# DL0WH_BiTuner_Ctrl_1V0.net
KiCad netlist of a schematic drawn in EAGLE
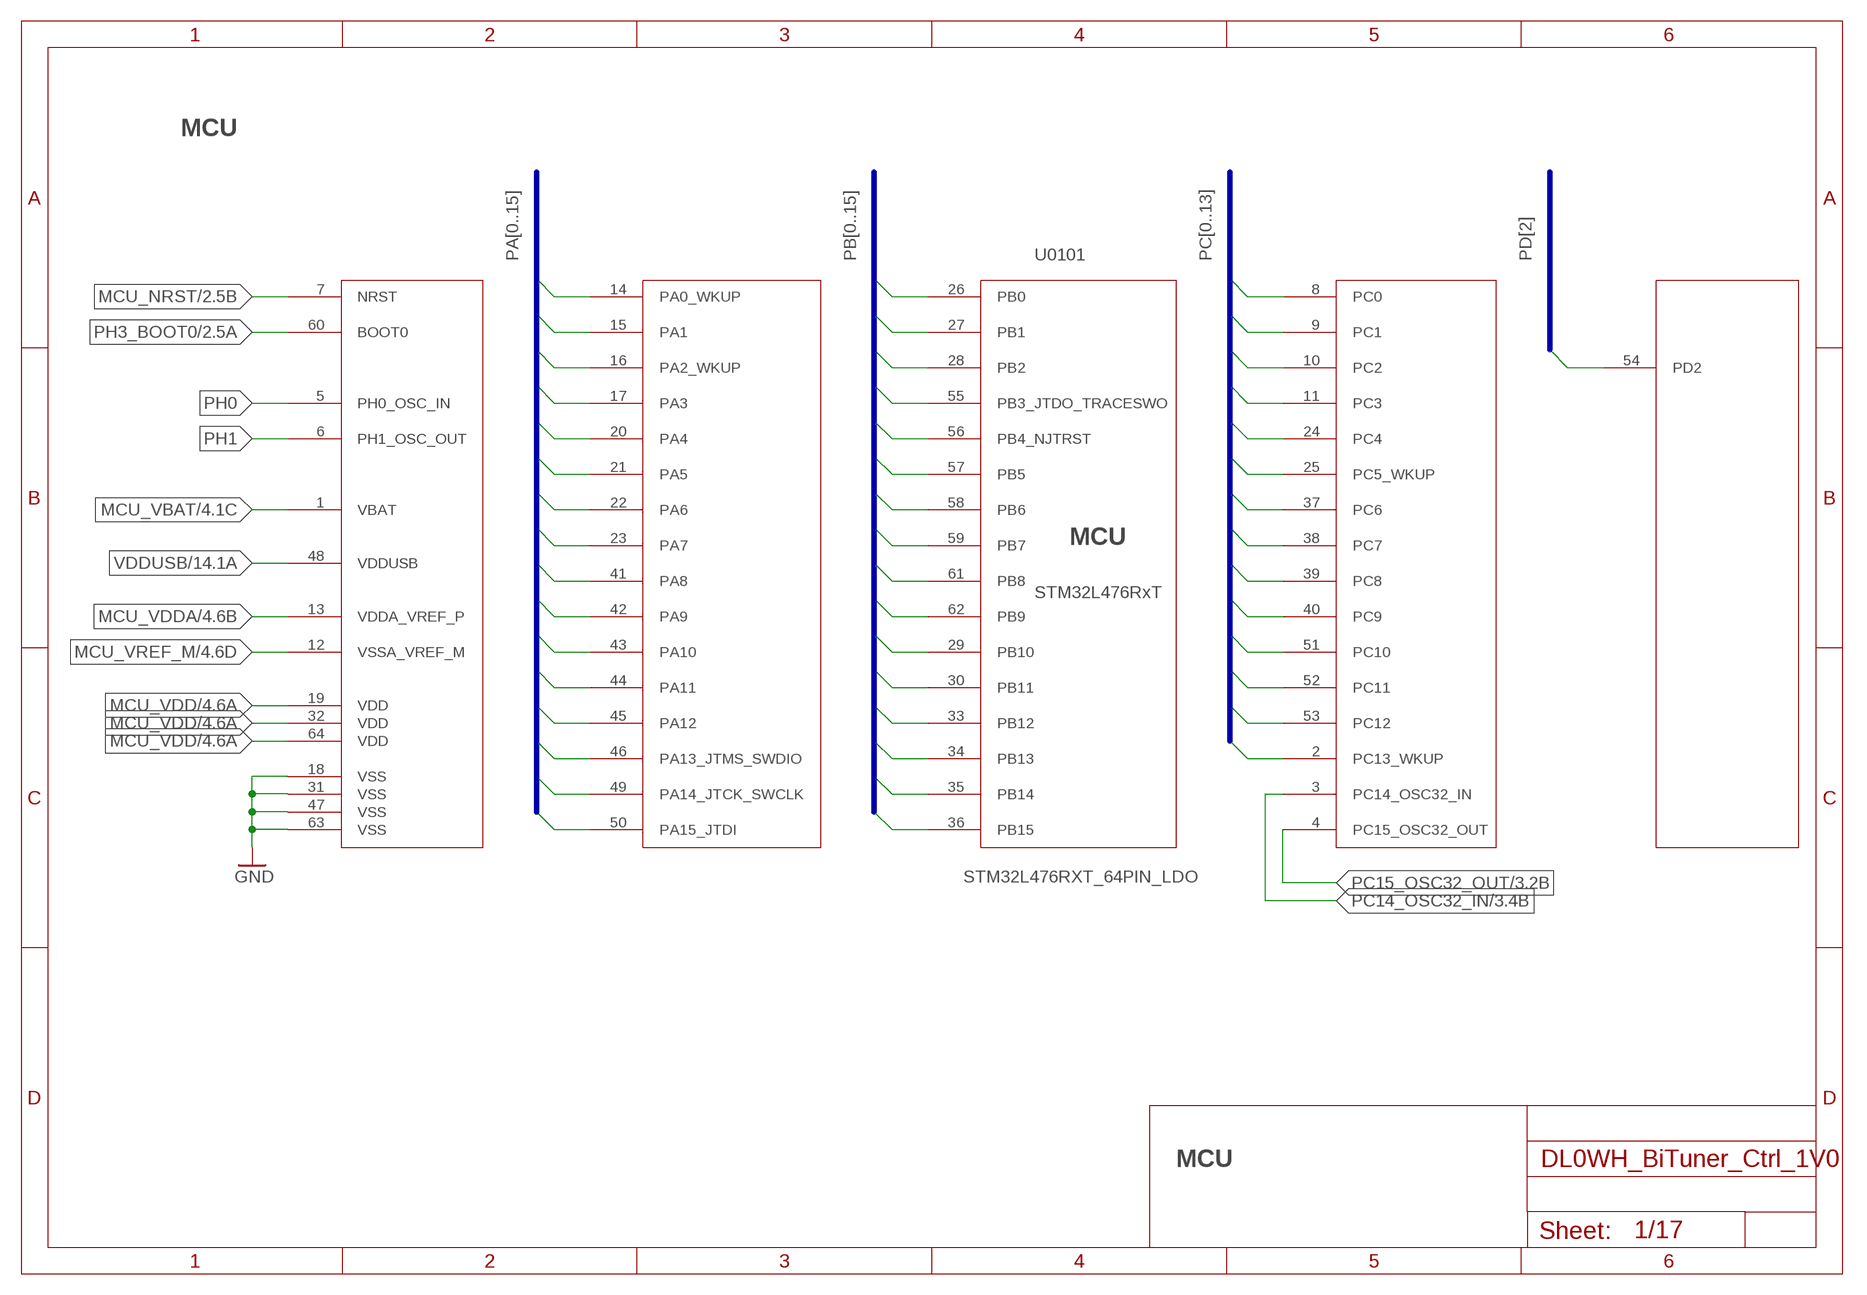
[diagram p0: schematic, sheet 1]
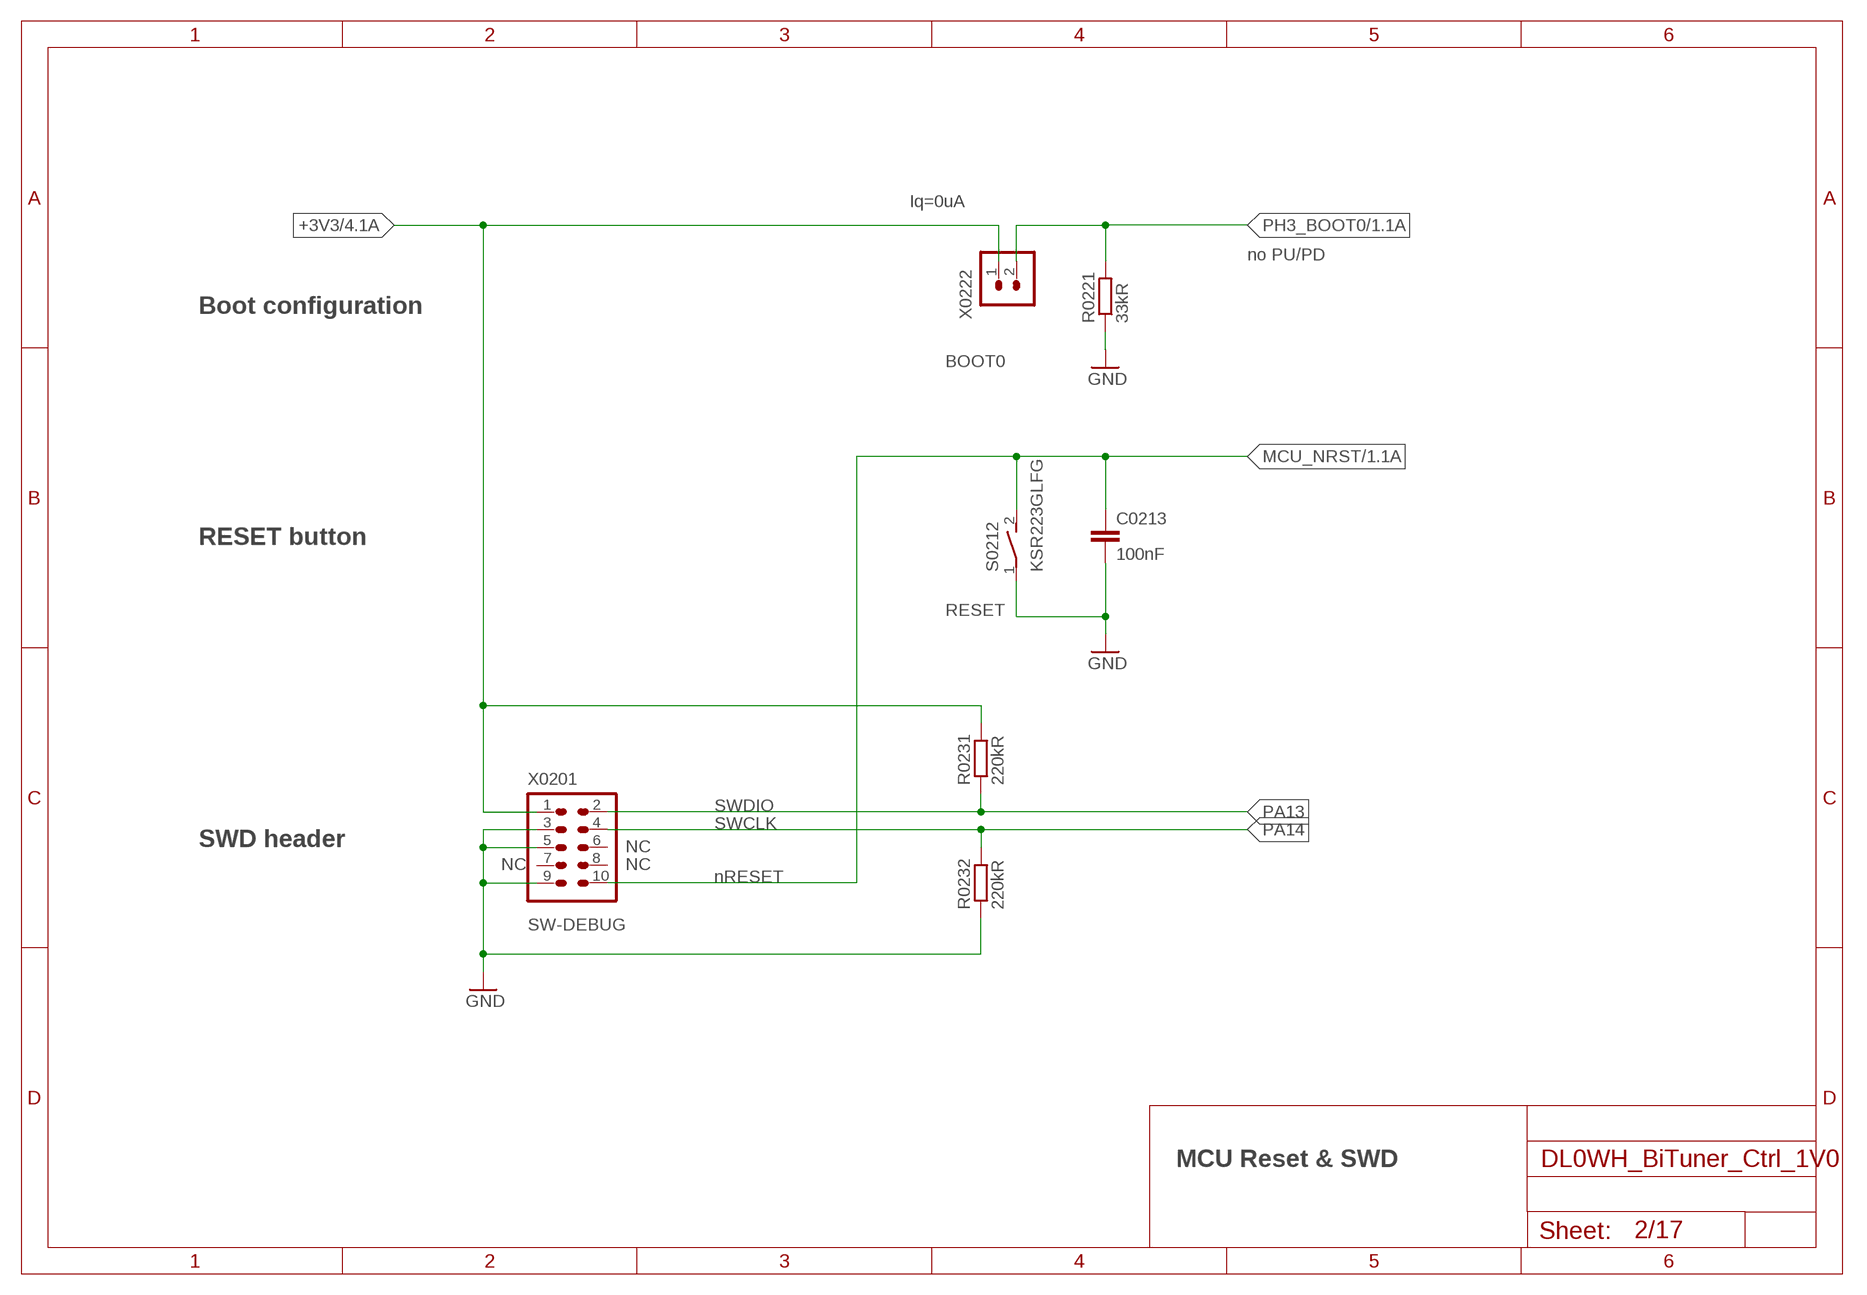
[diagram p1: schematic, sheet 2]
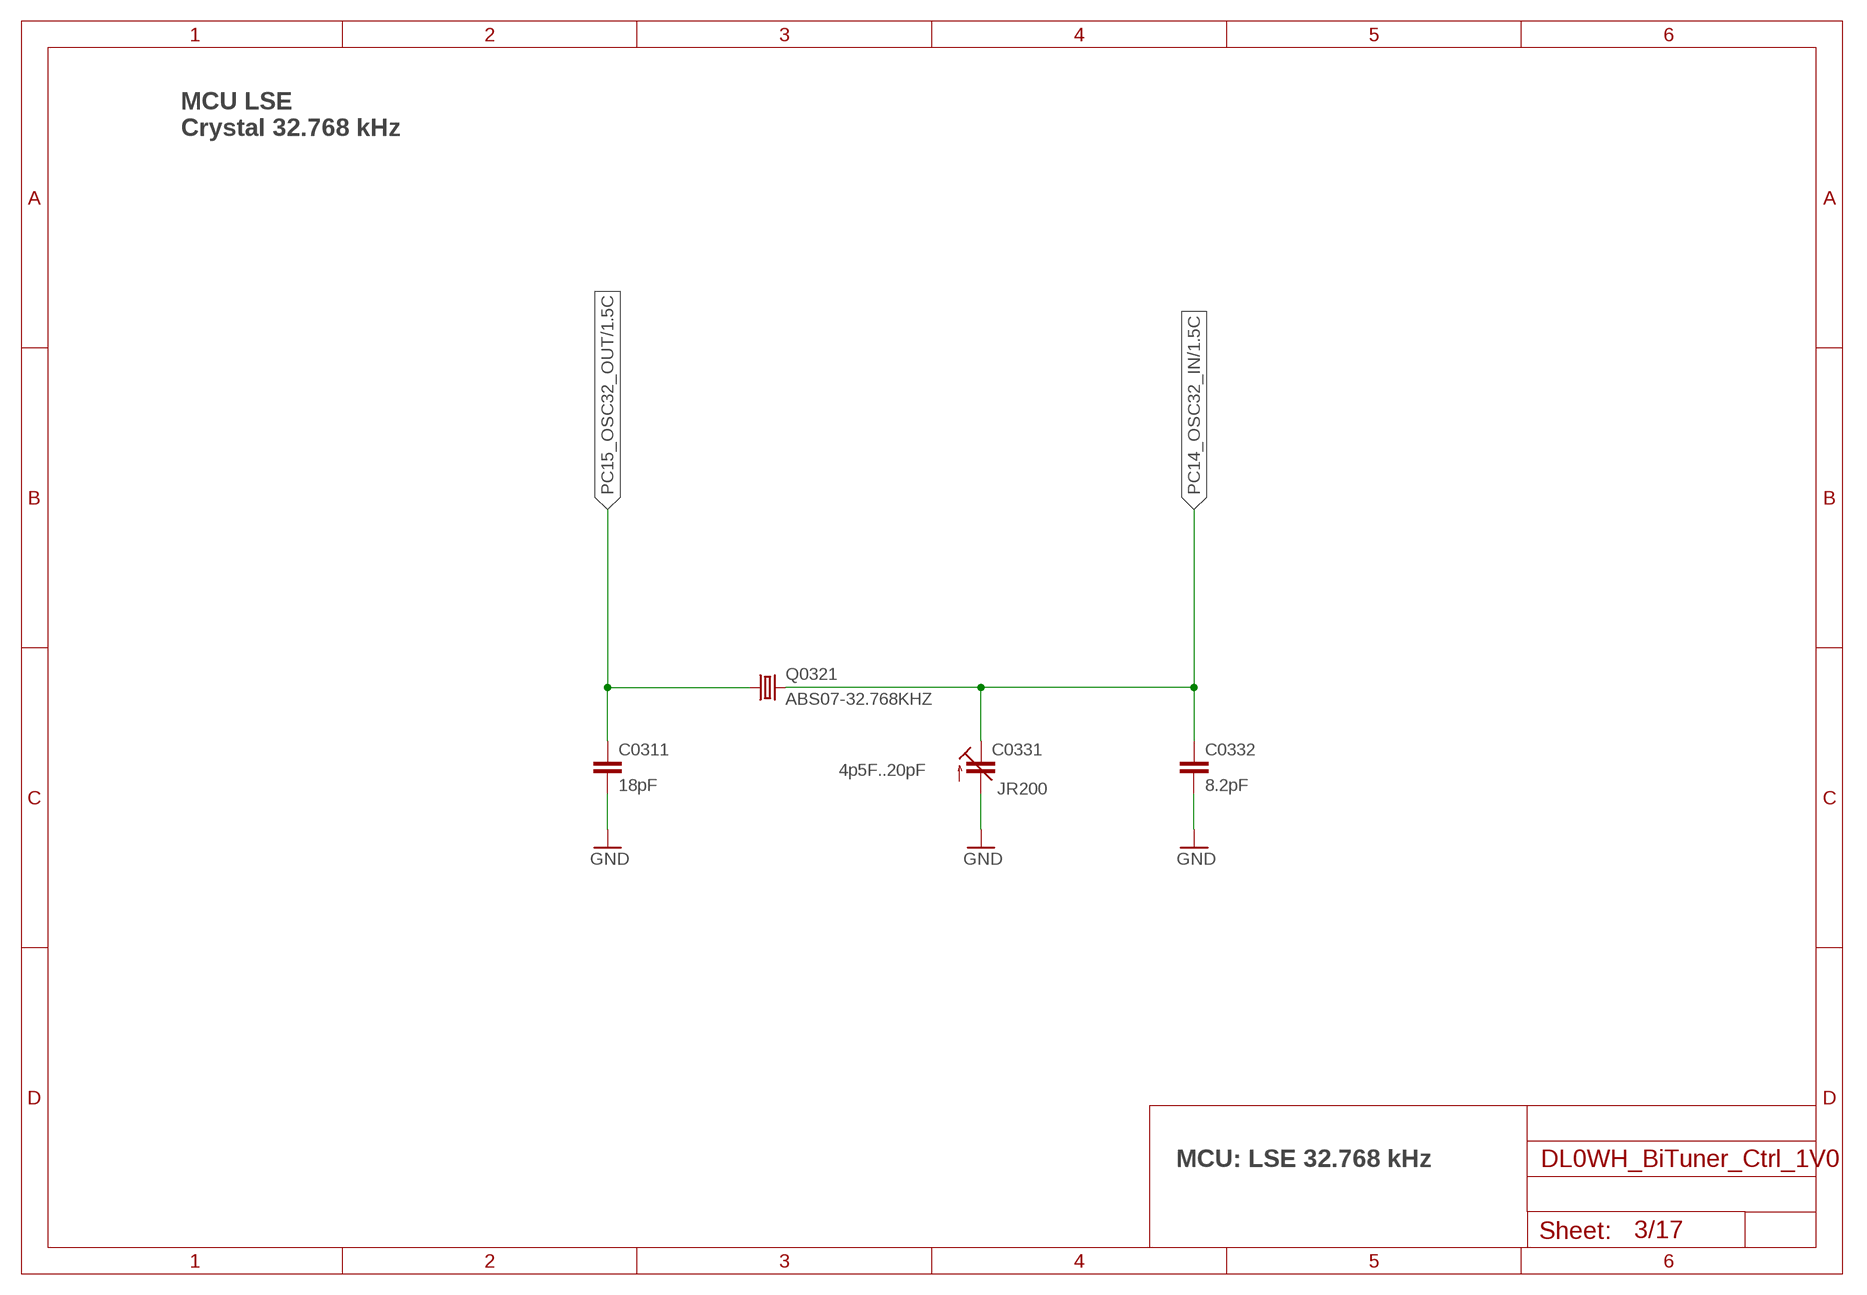
[diagram p2: schematic, sheet 3]
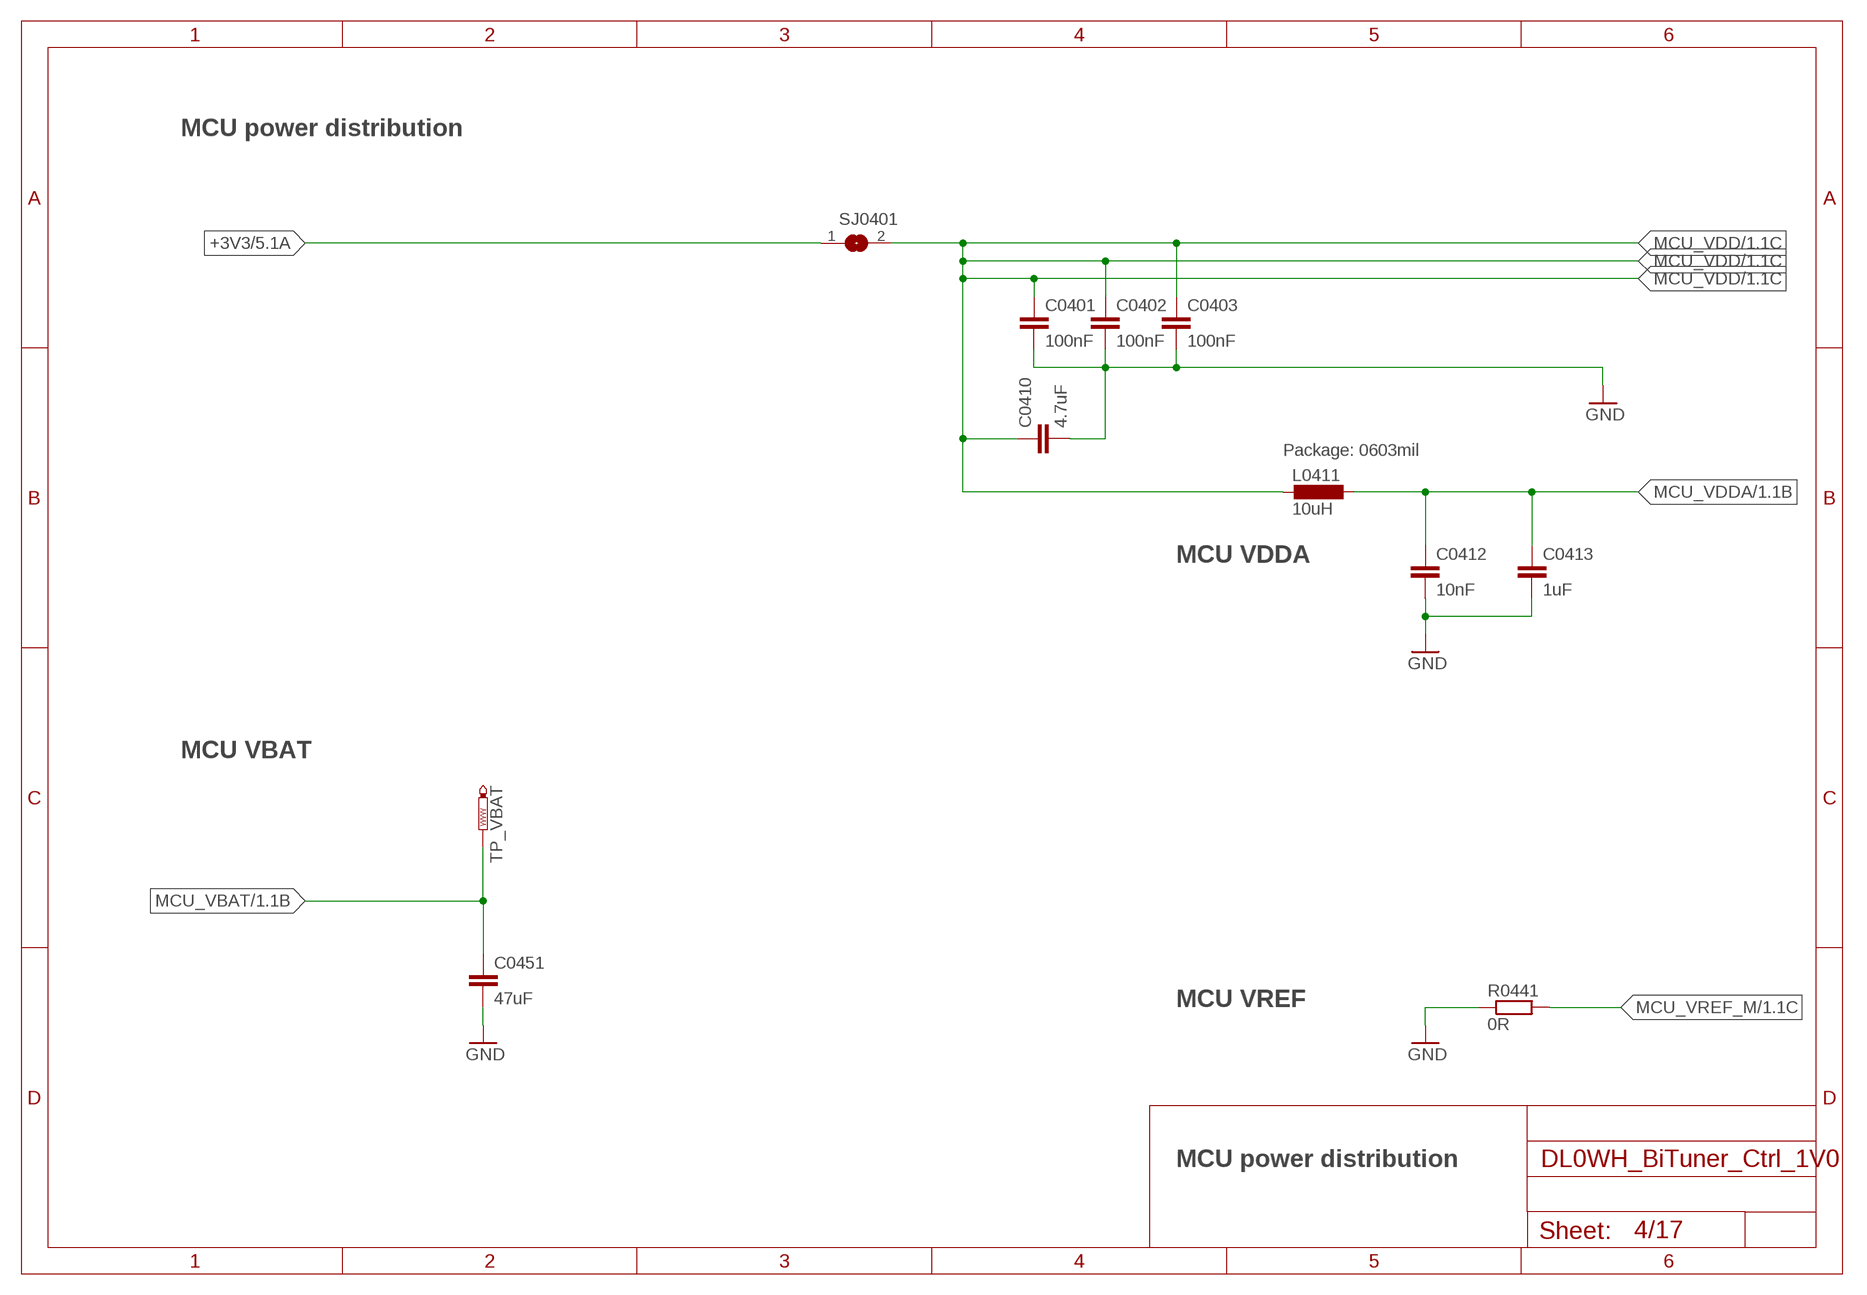
[diagram p3: schematic, sheet 4]
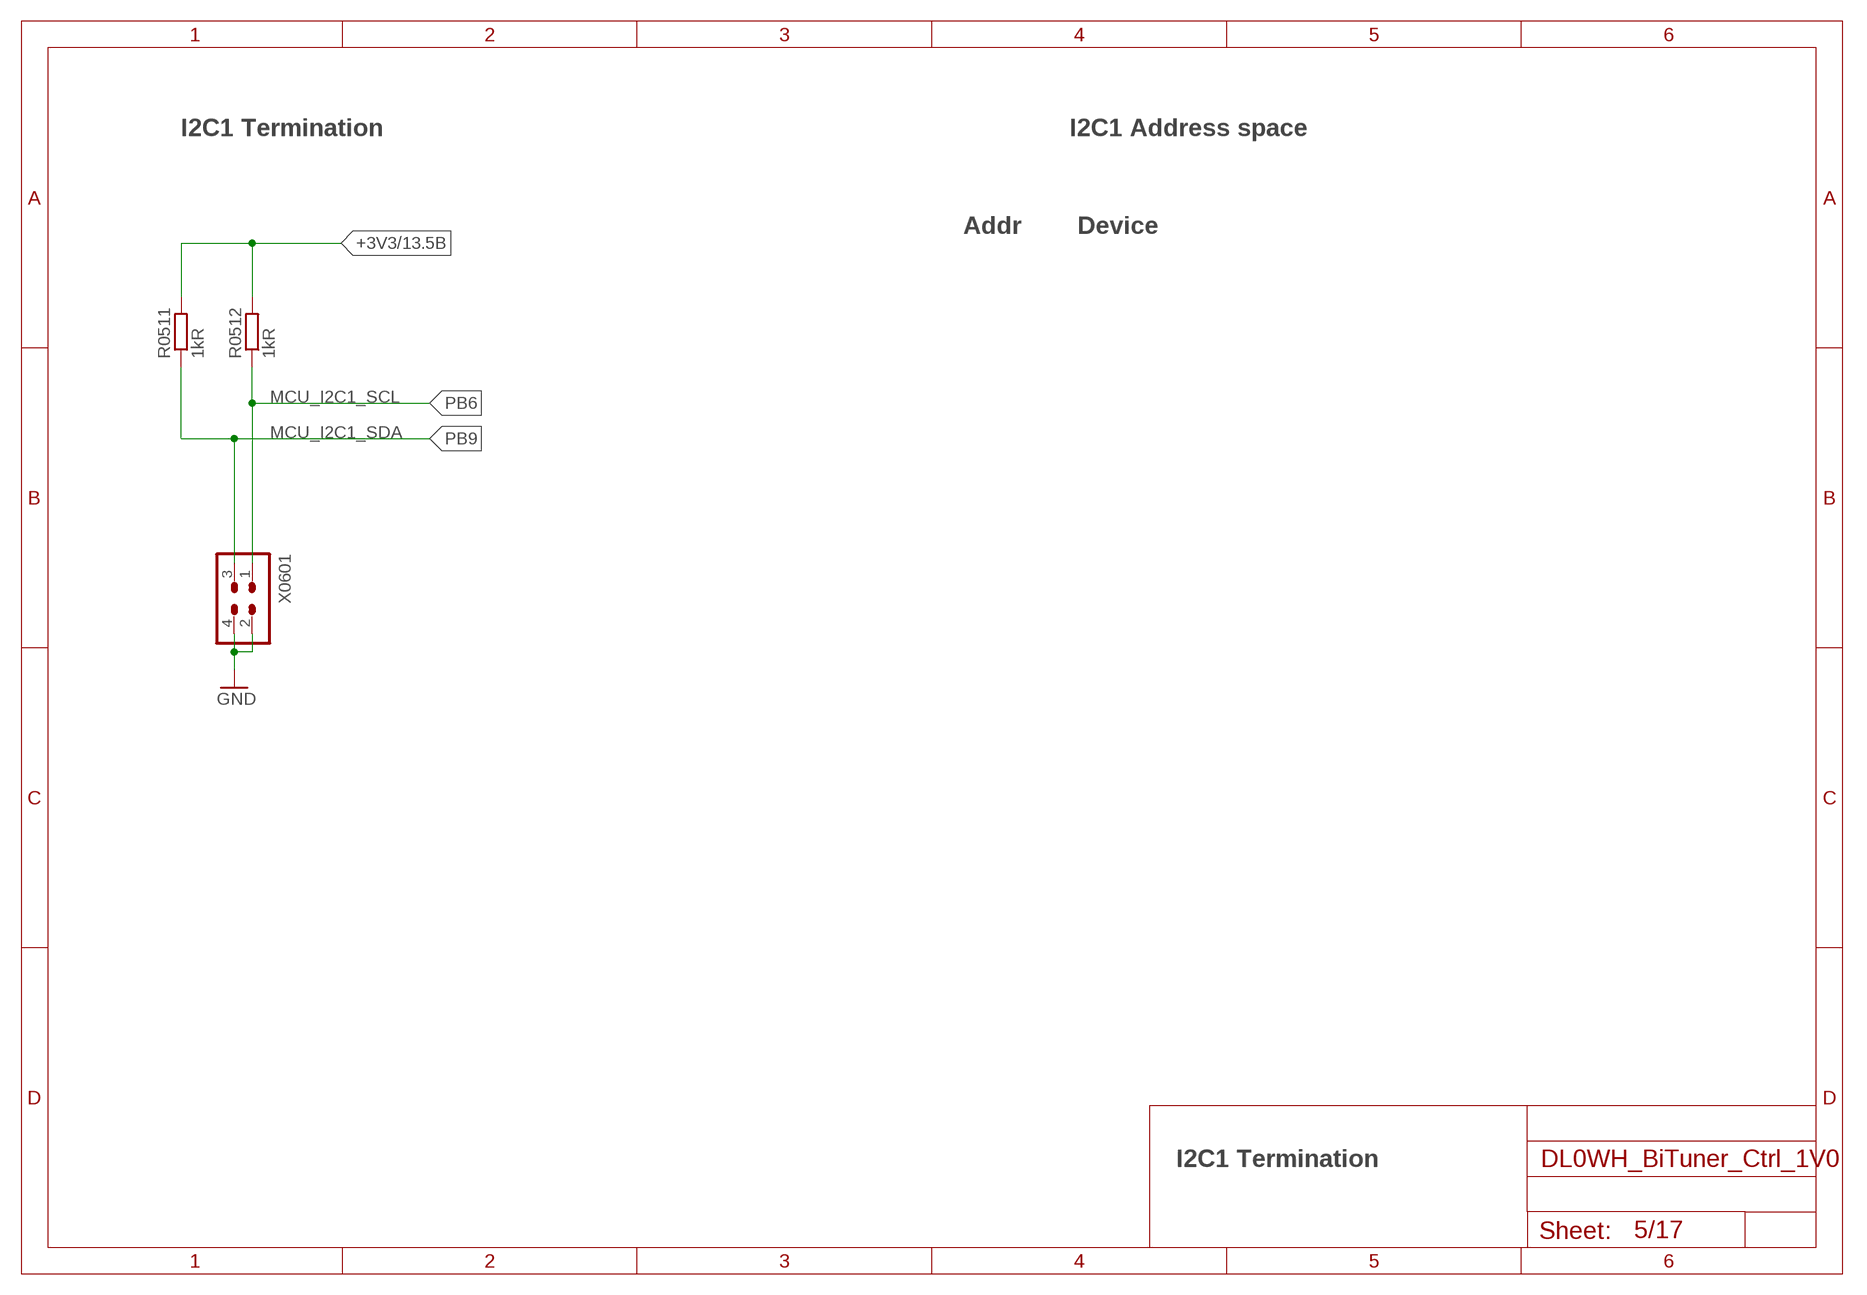
[diagram p4: schematic, sheet 5]
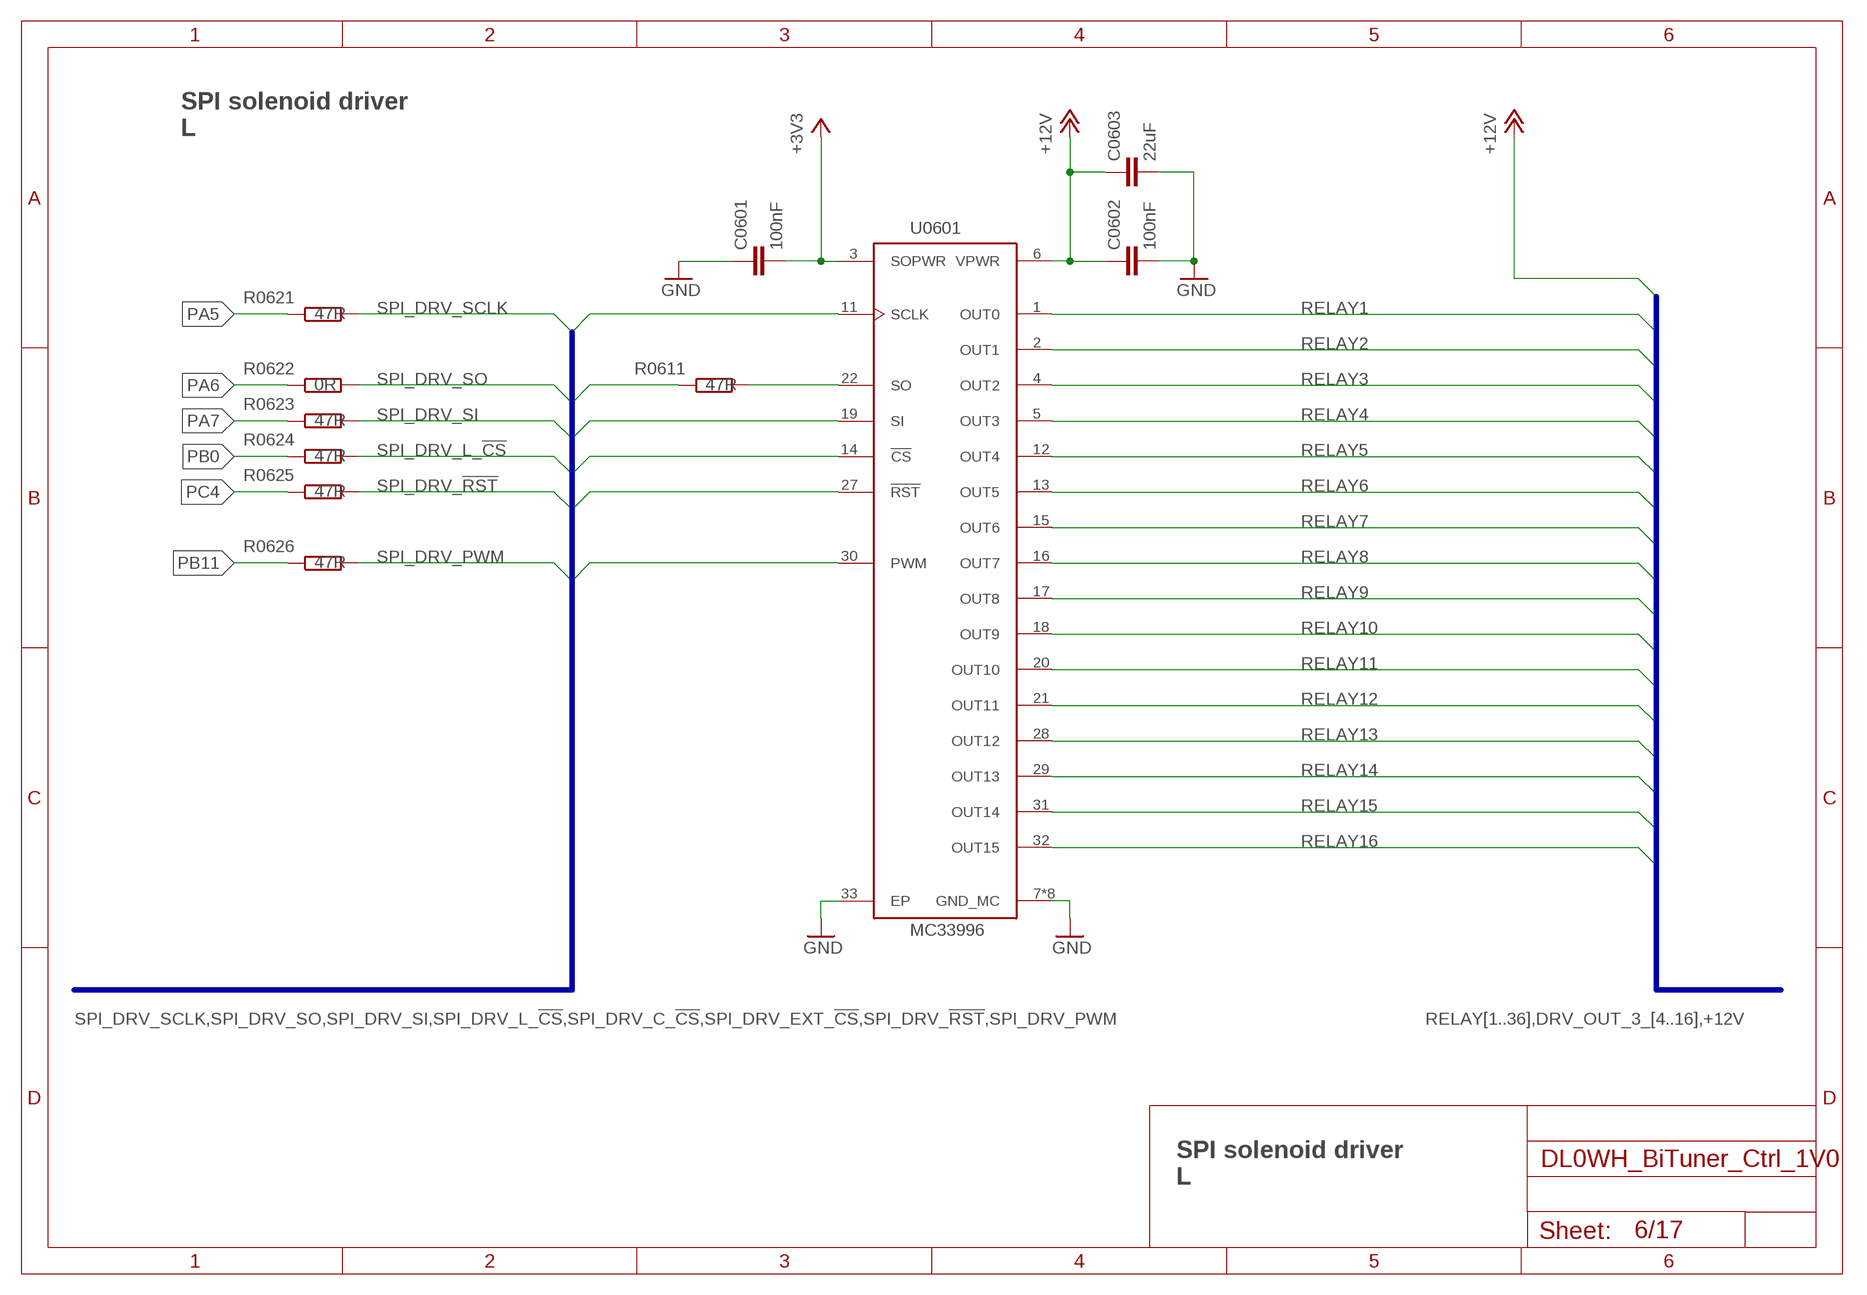
[diagram p5: schematic, sheet 6]
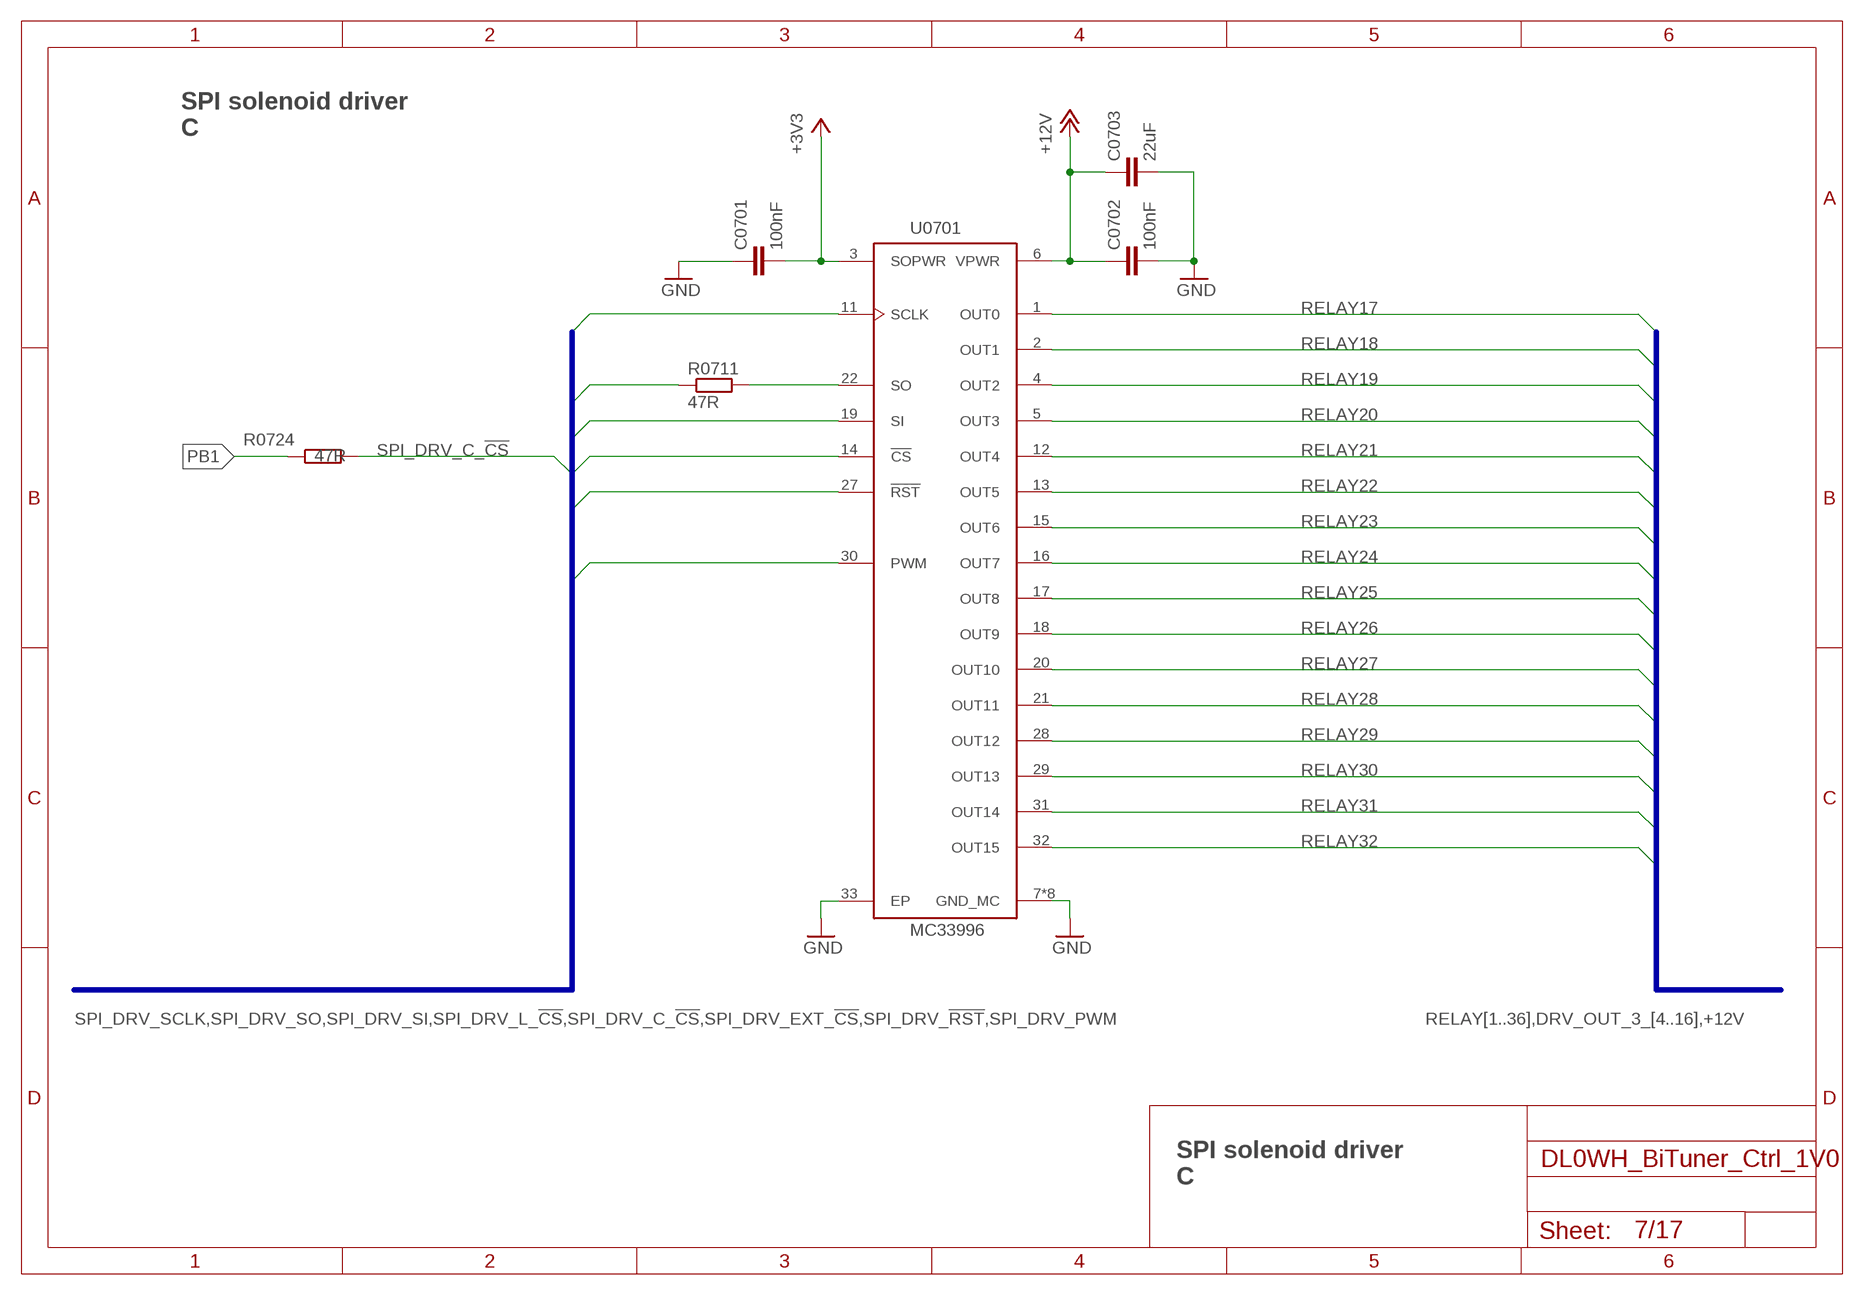
[diagram p6: schematic, sheet 7]
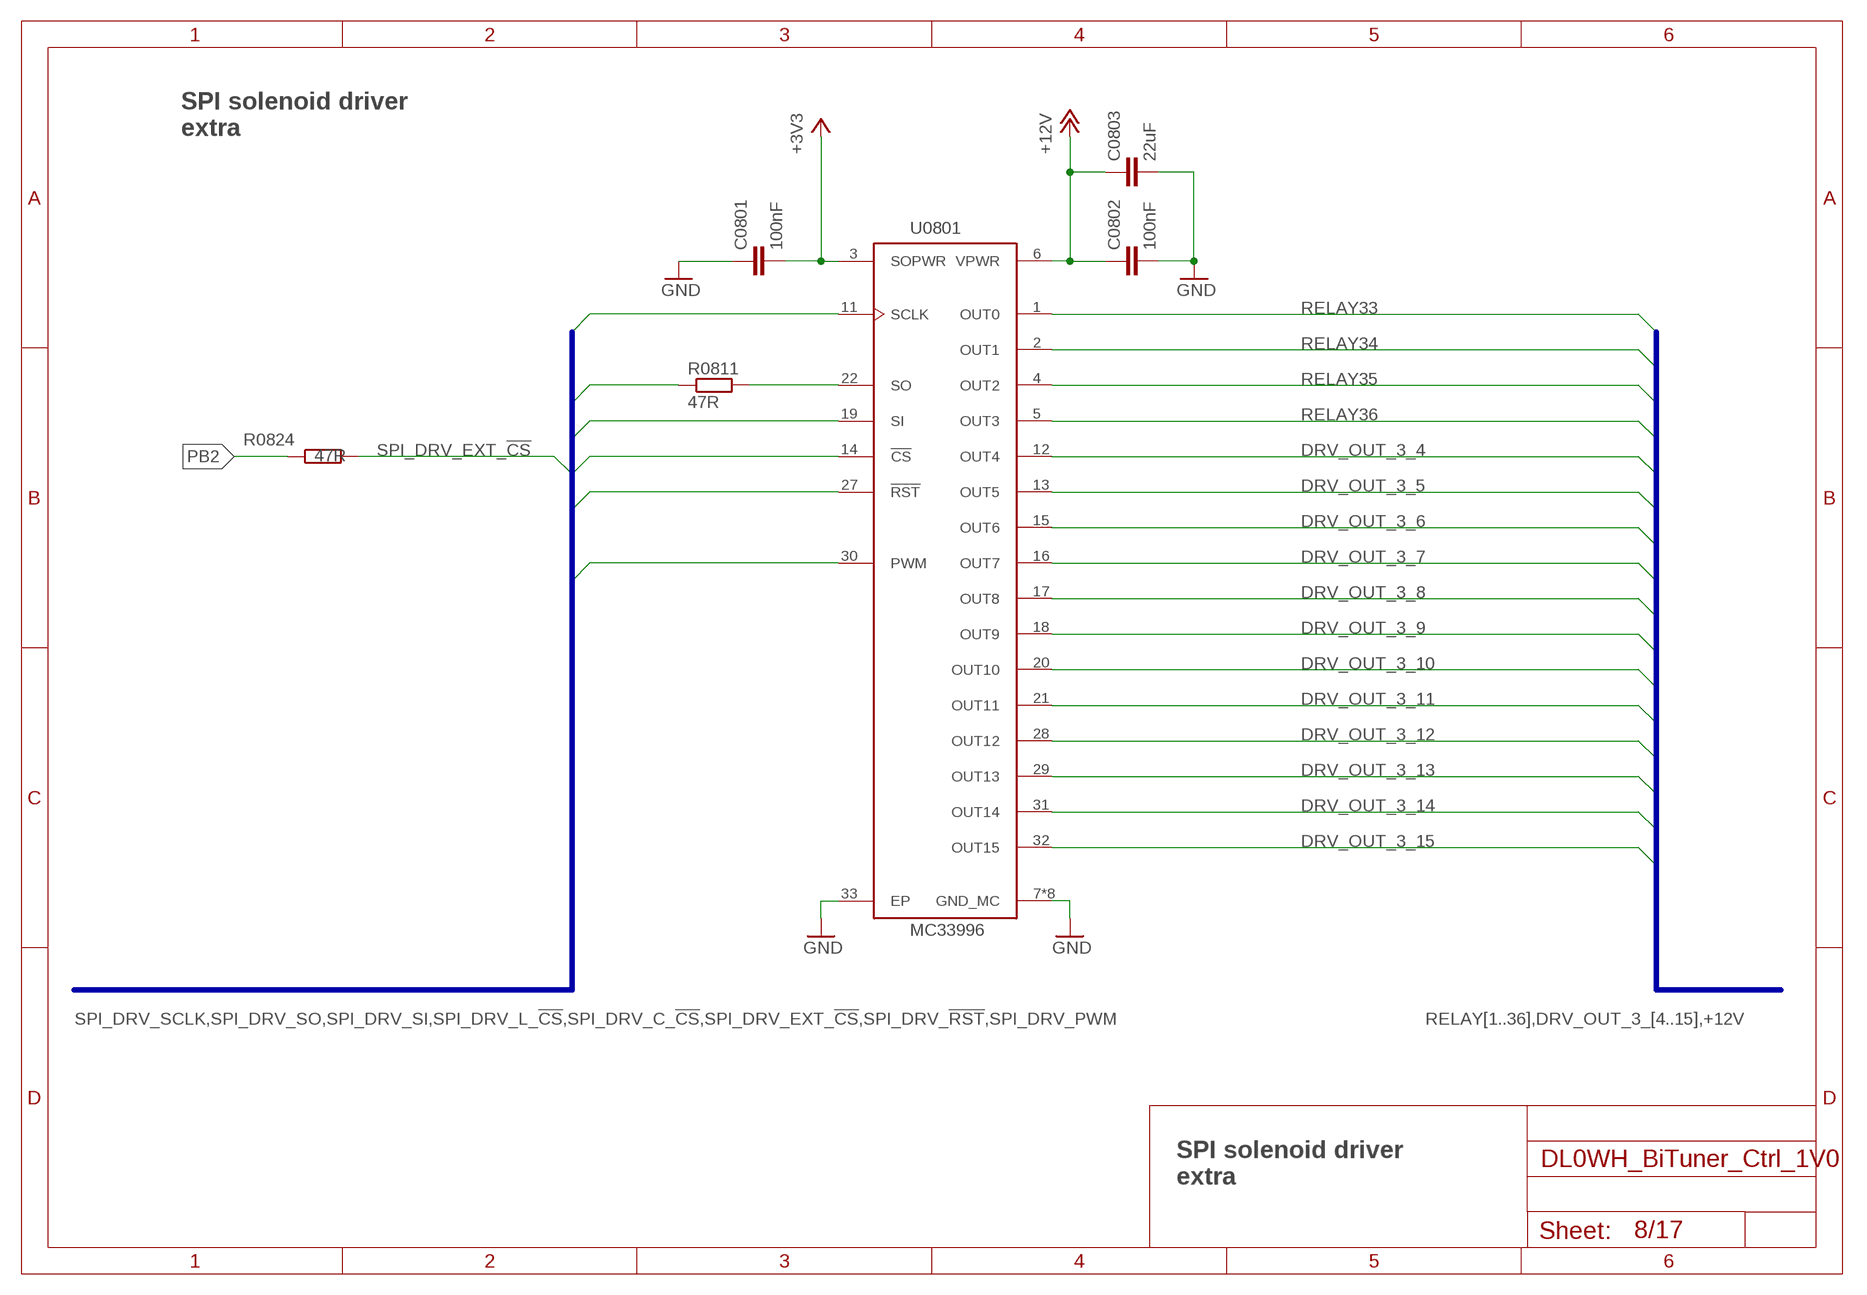
[diagram p7: schematic, sheet 8]
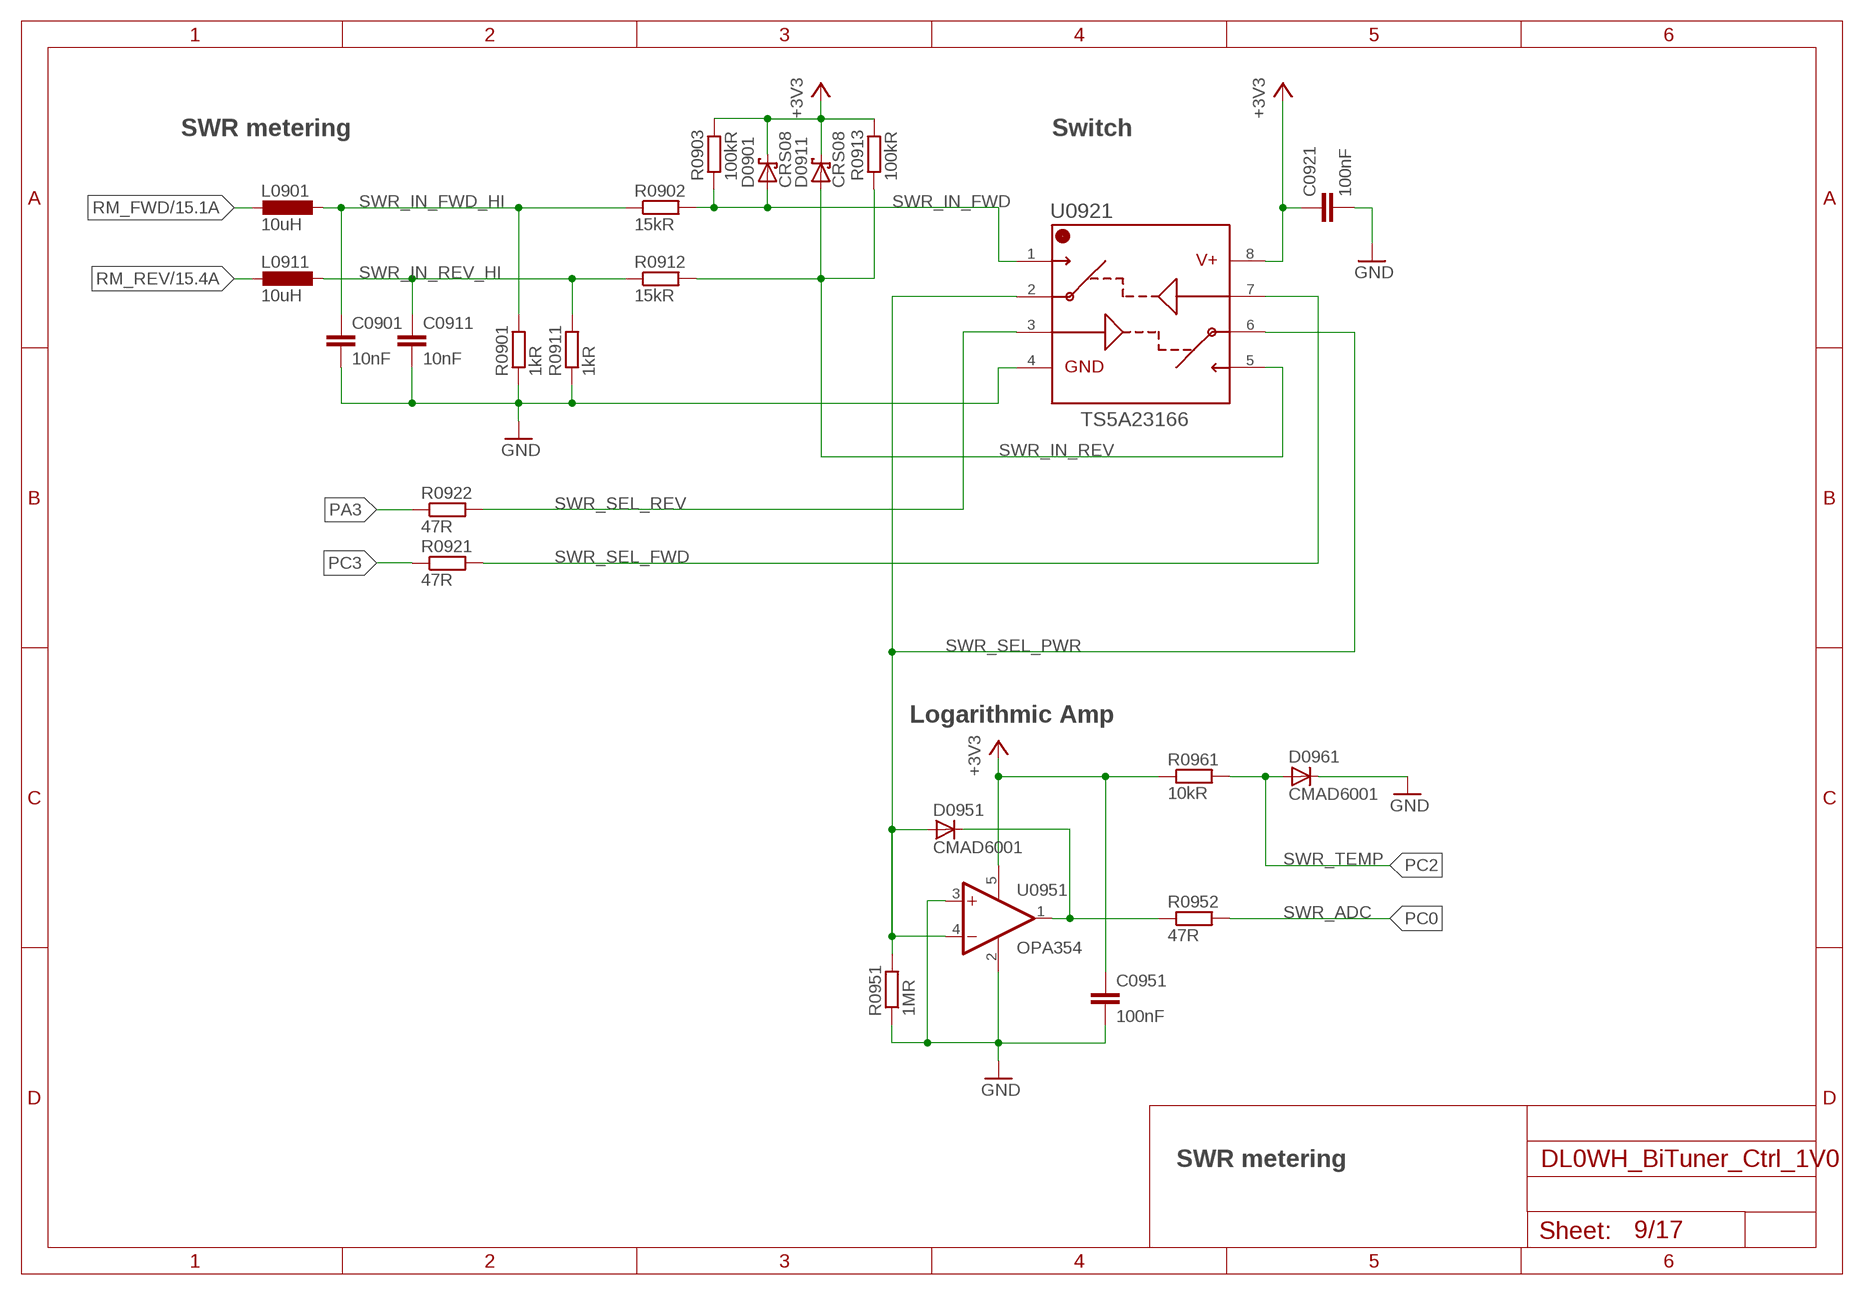
[diagram p8: schematic, sheet 9]
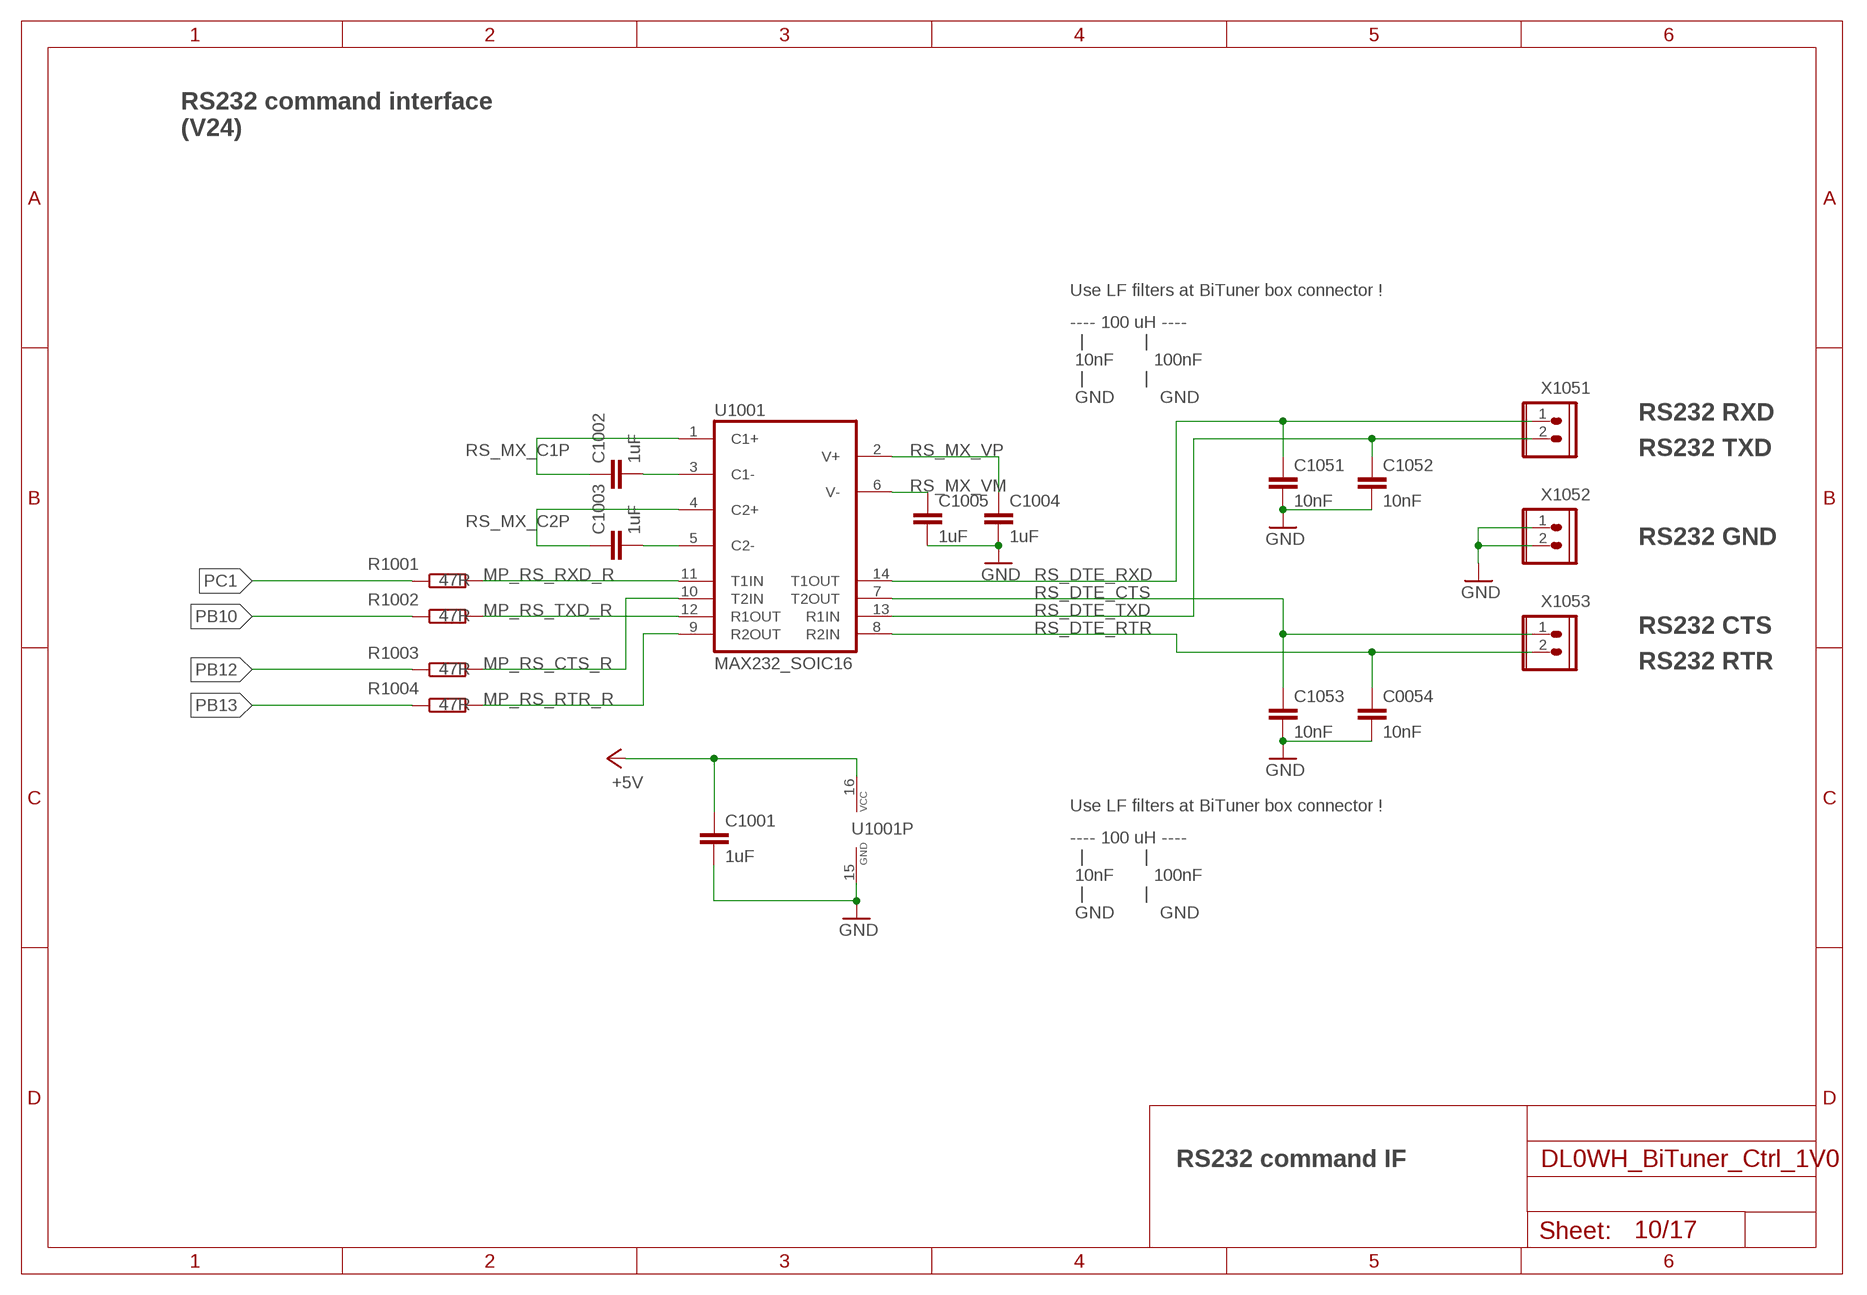
[diagram p9: schematic, sheet 10]
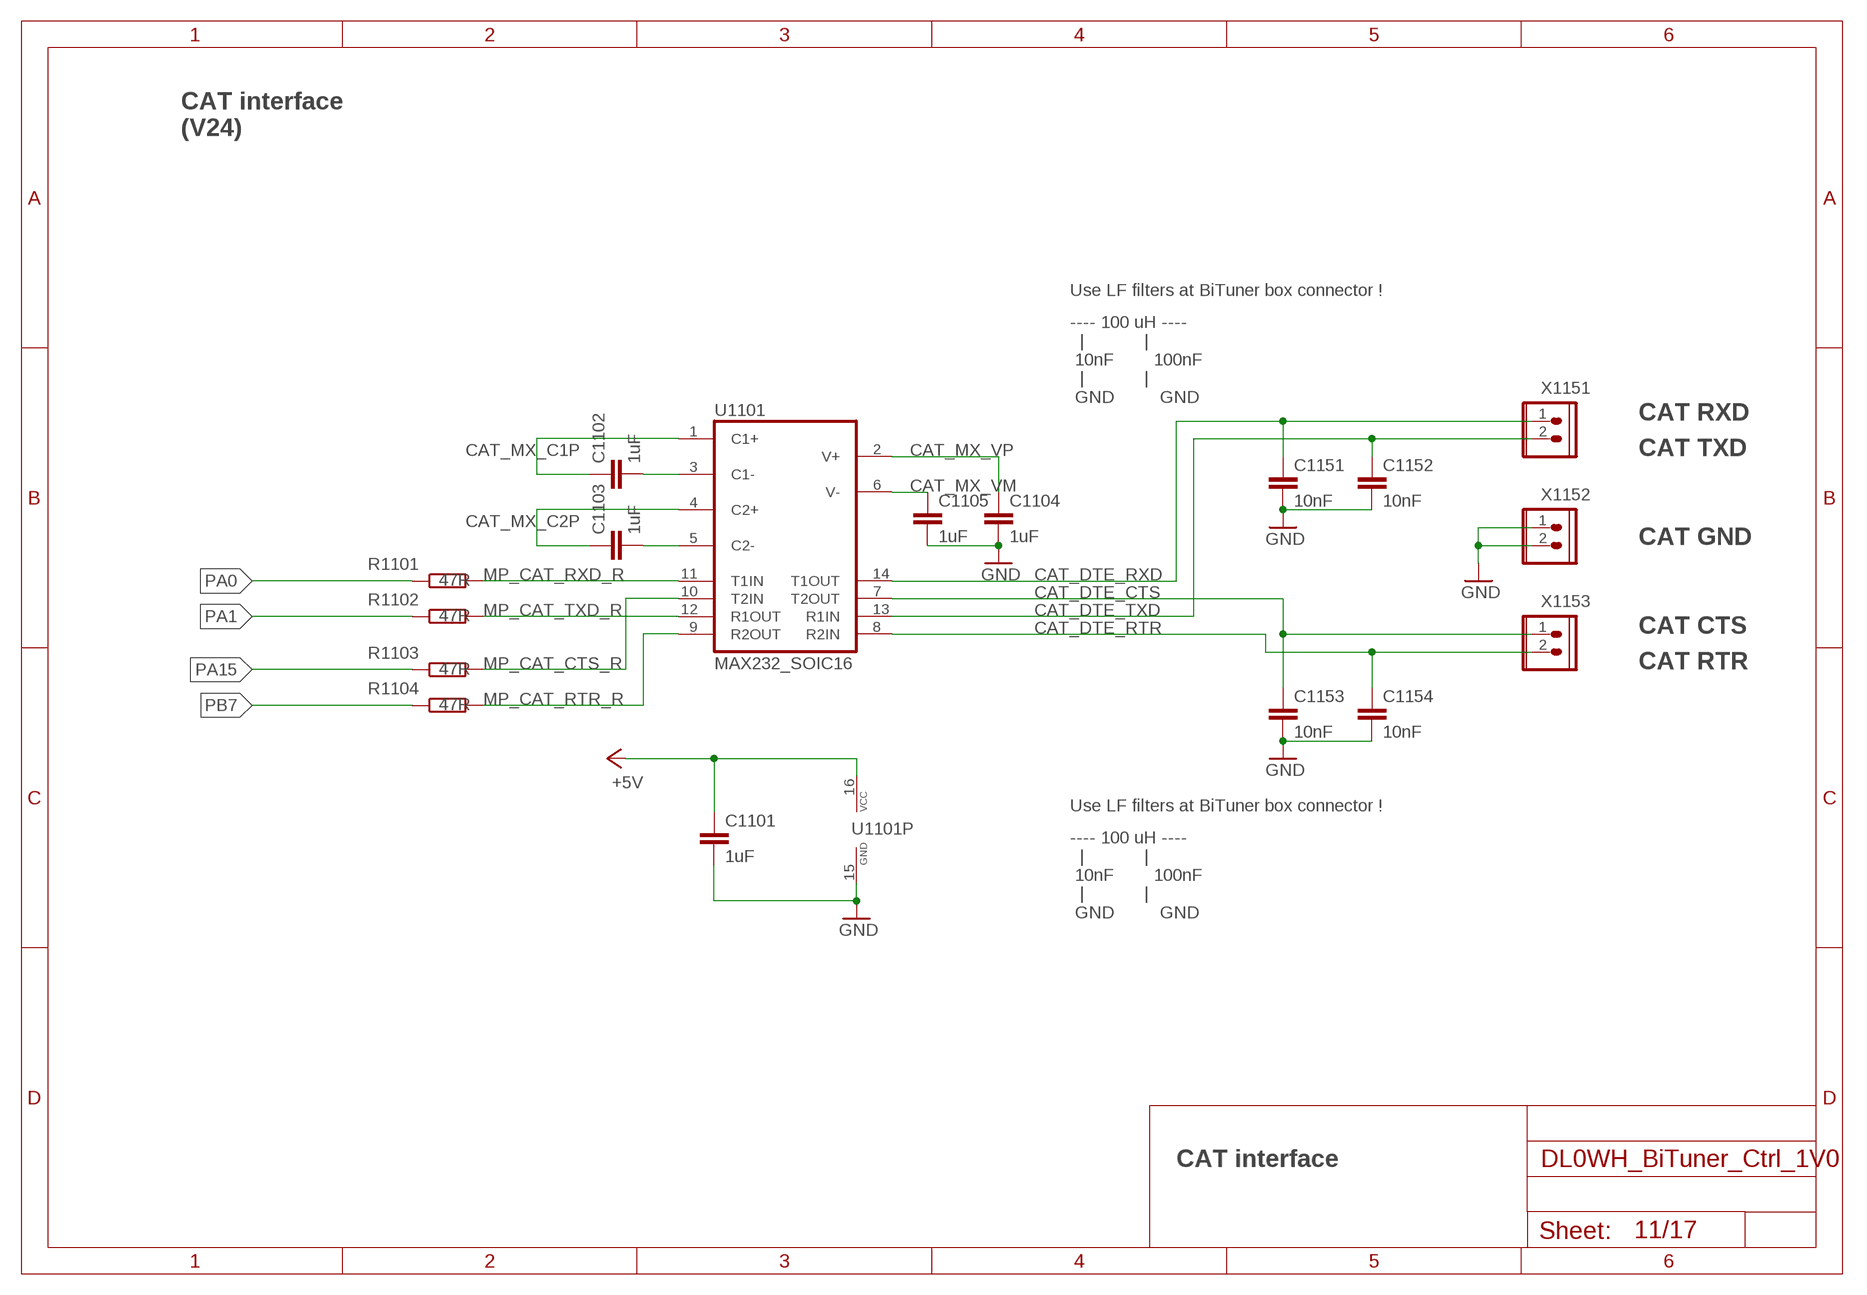
[diagram p10: schematic, sheet 11]
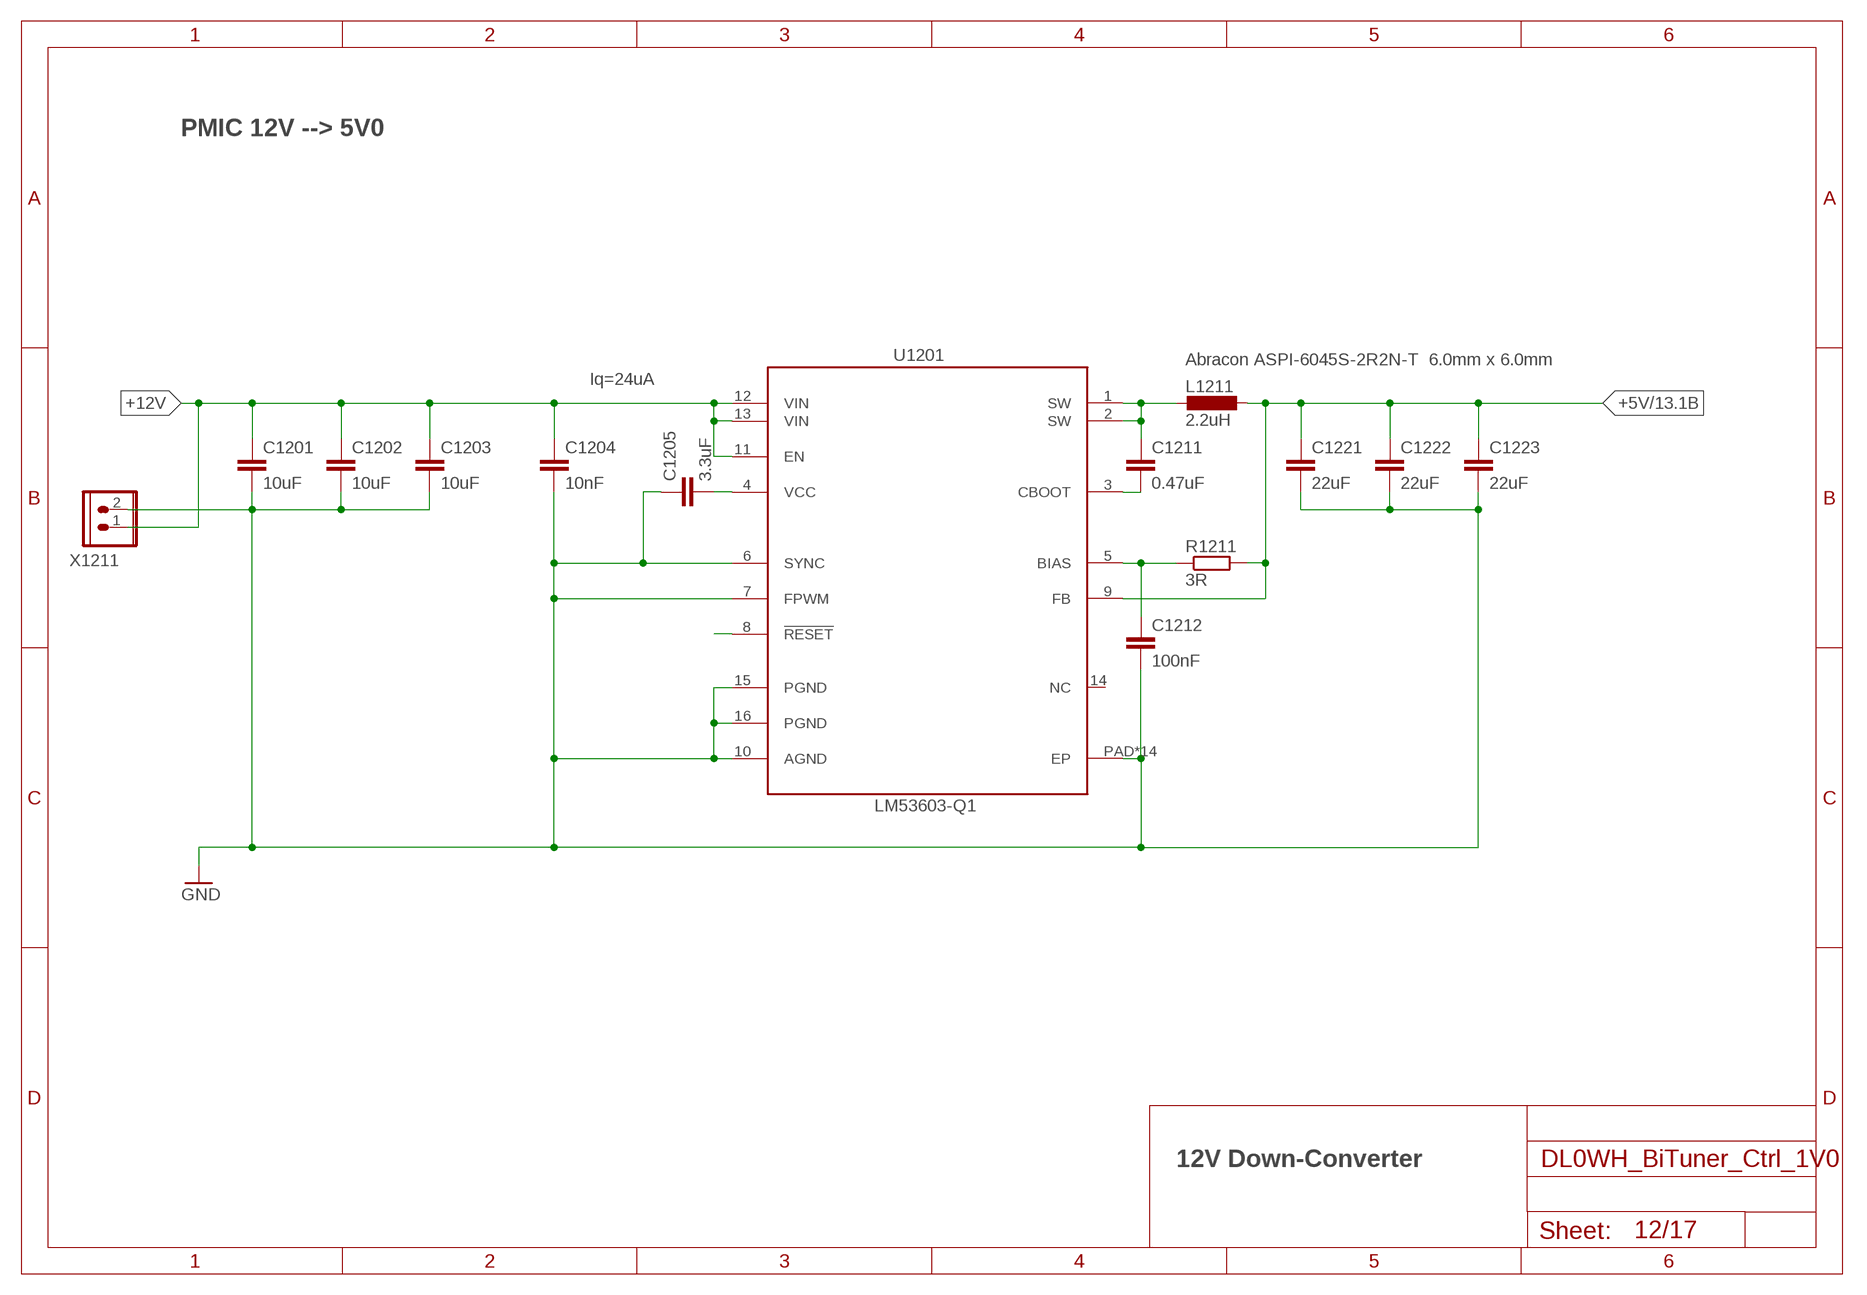
[diagram p11: schematic, sheet 12]
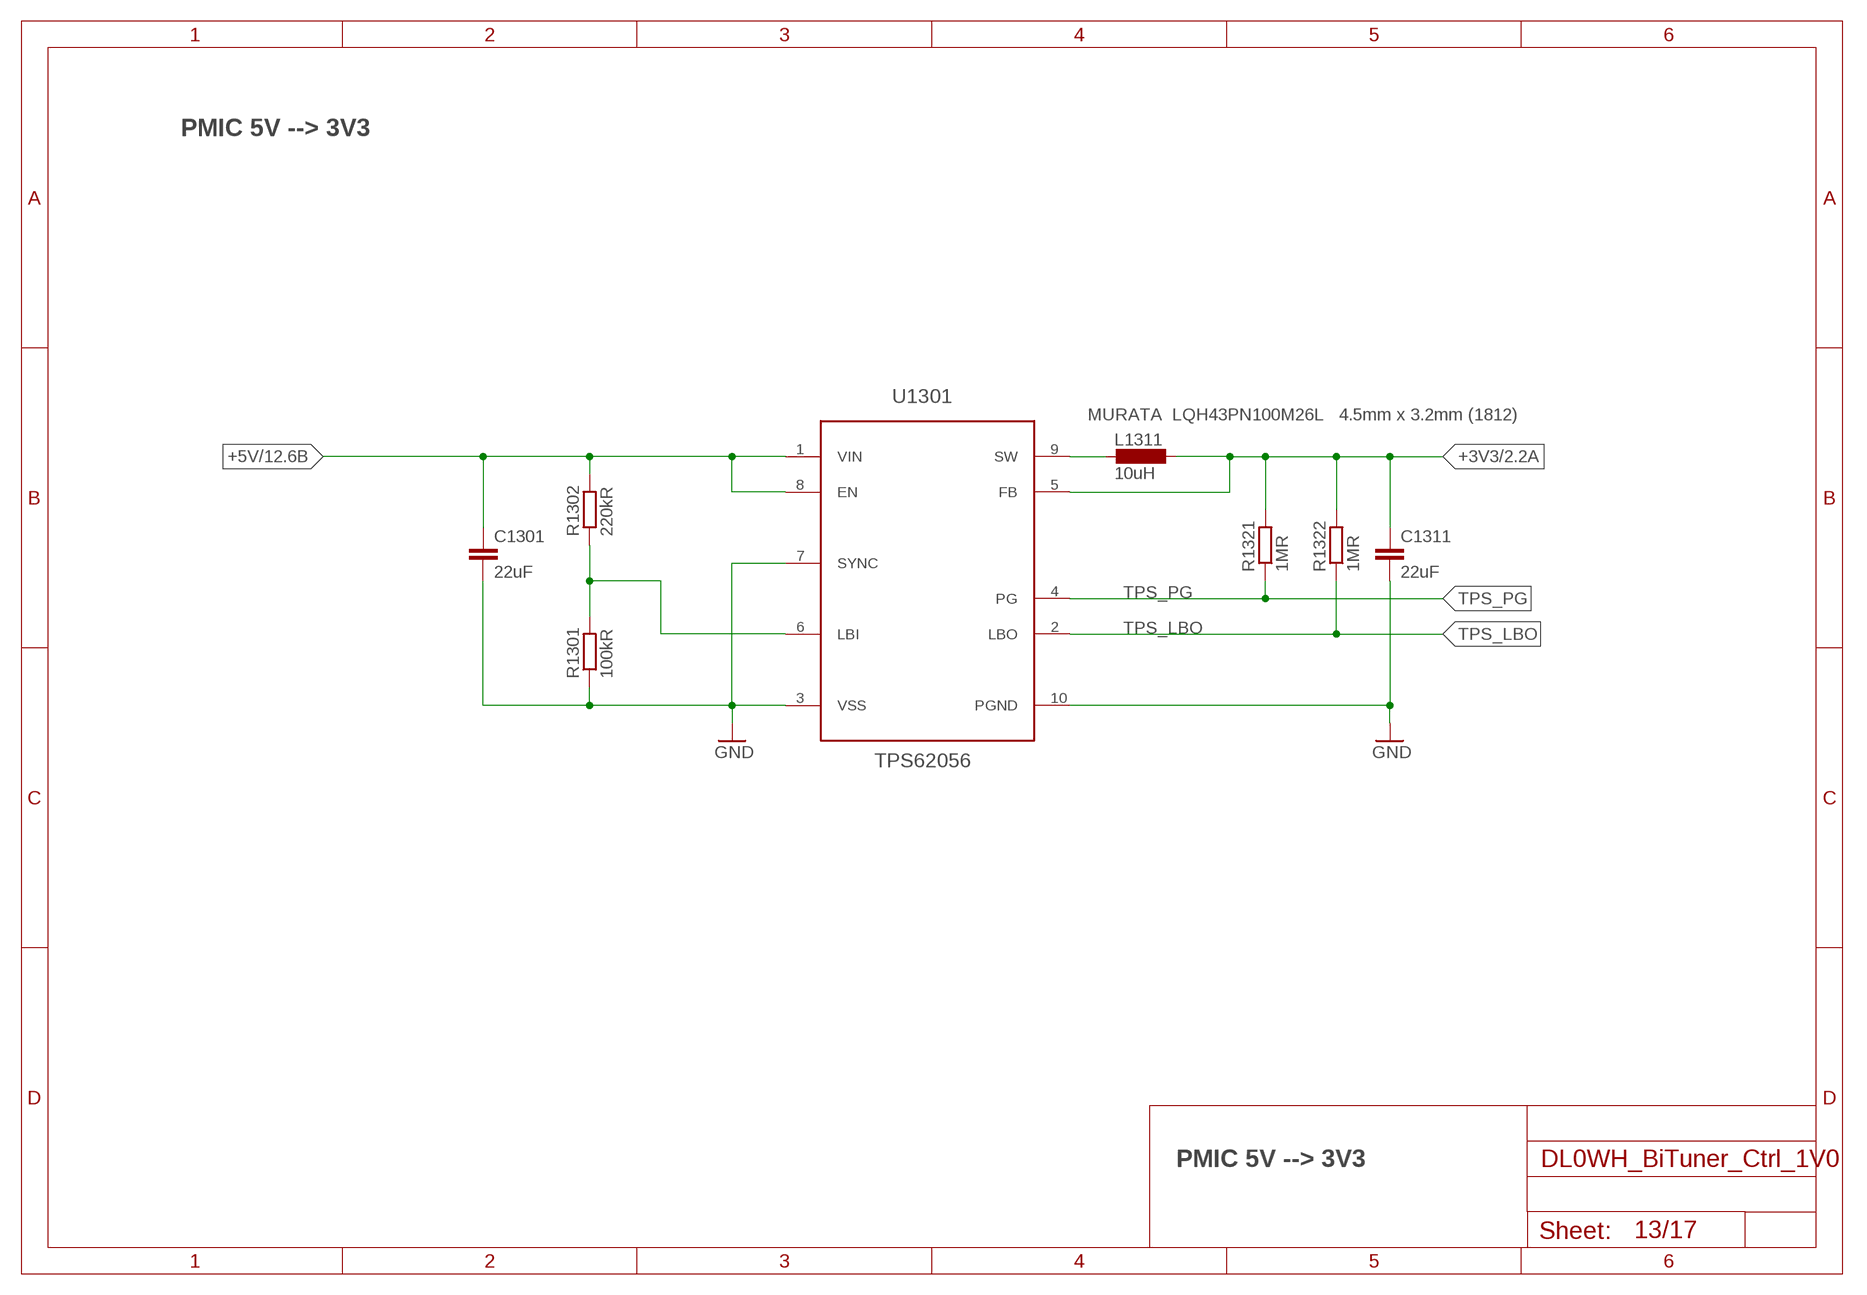
[diagram p12: schematic, sheet 13]
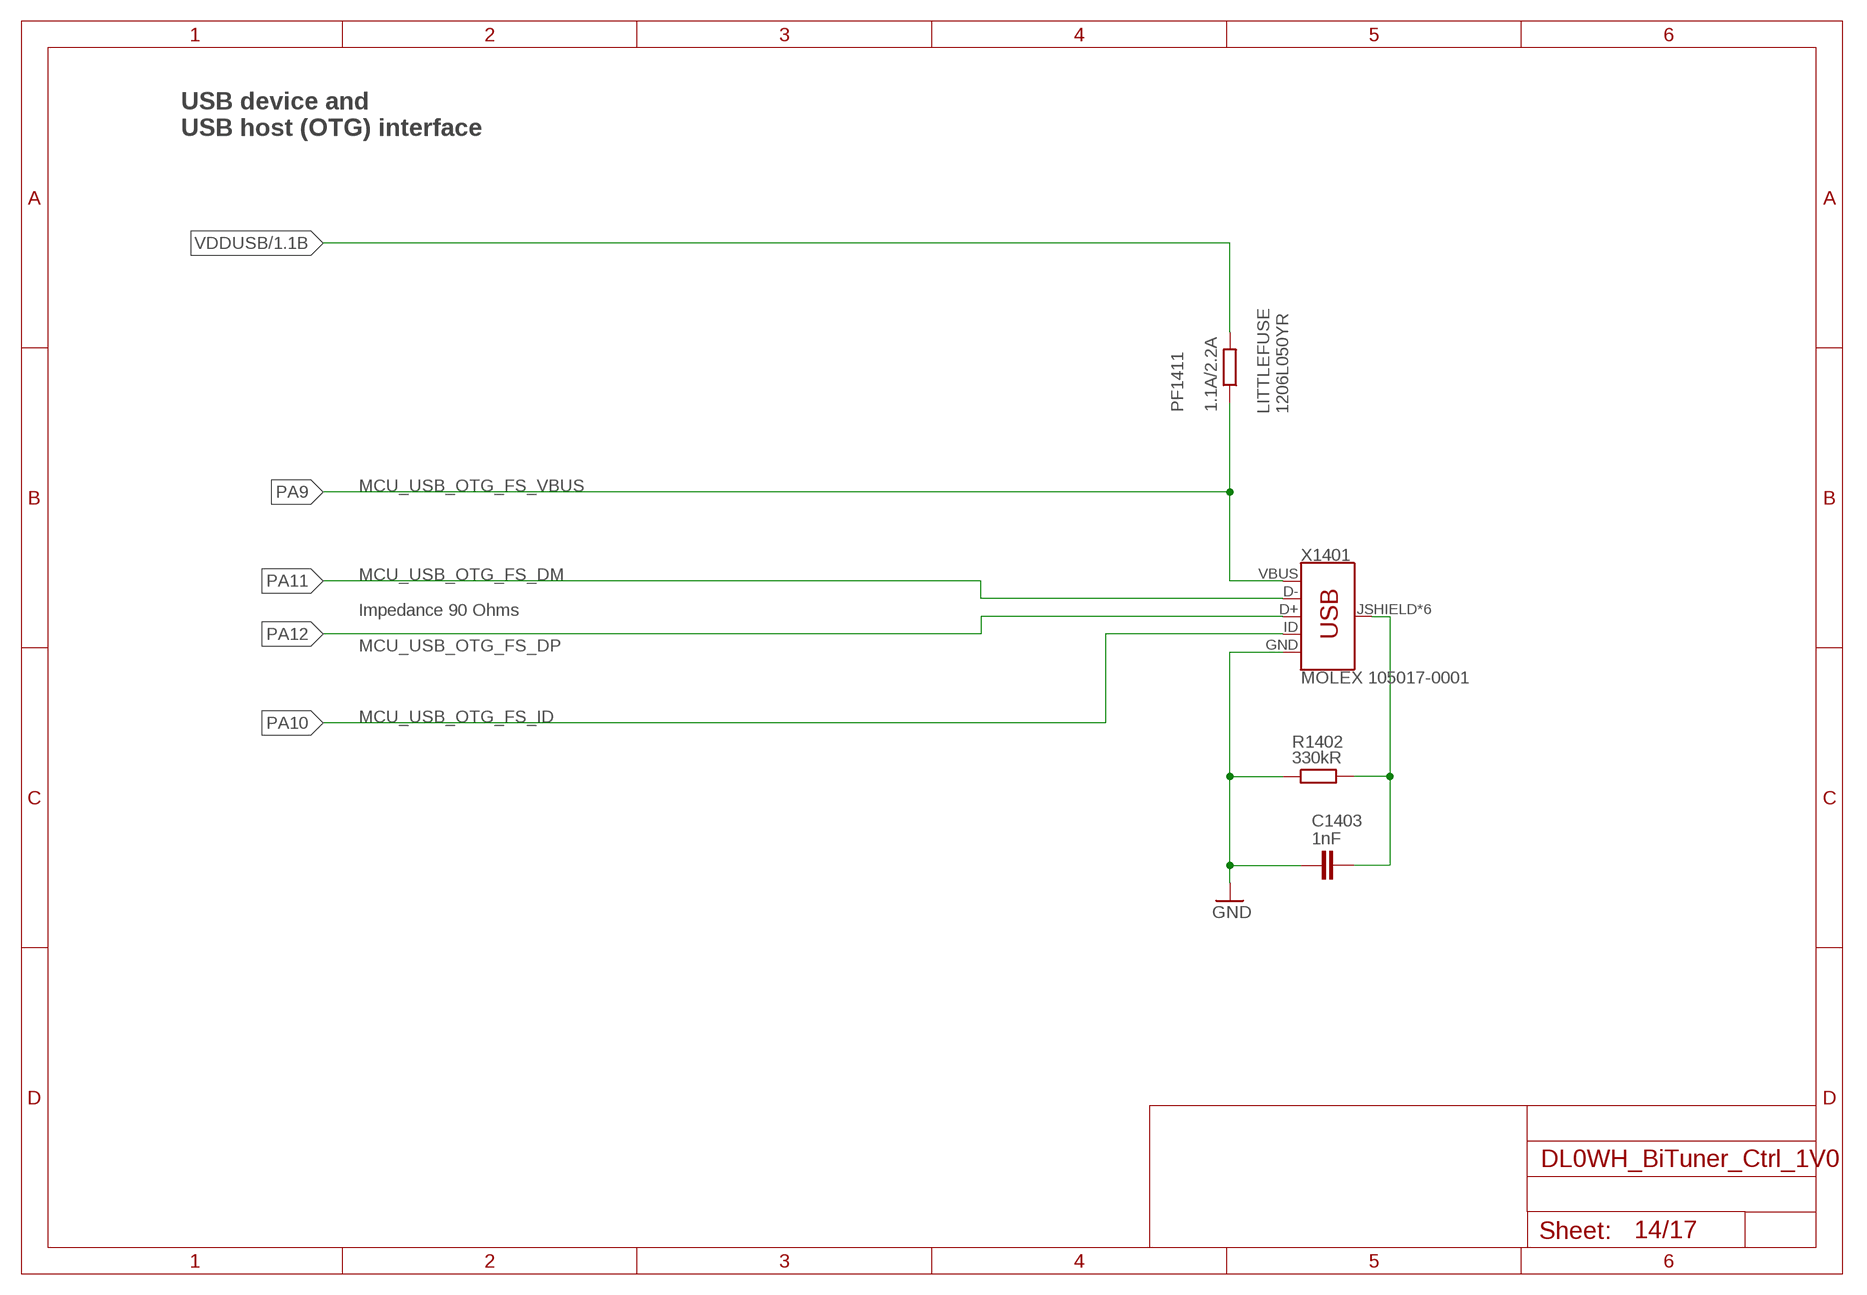
[diagram p13: schematic, sheet 14]
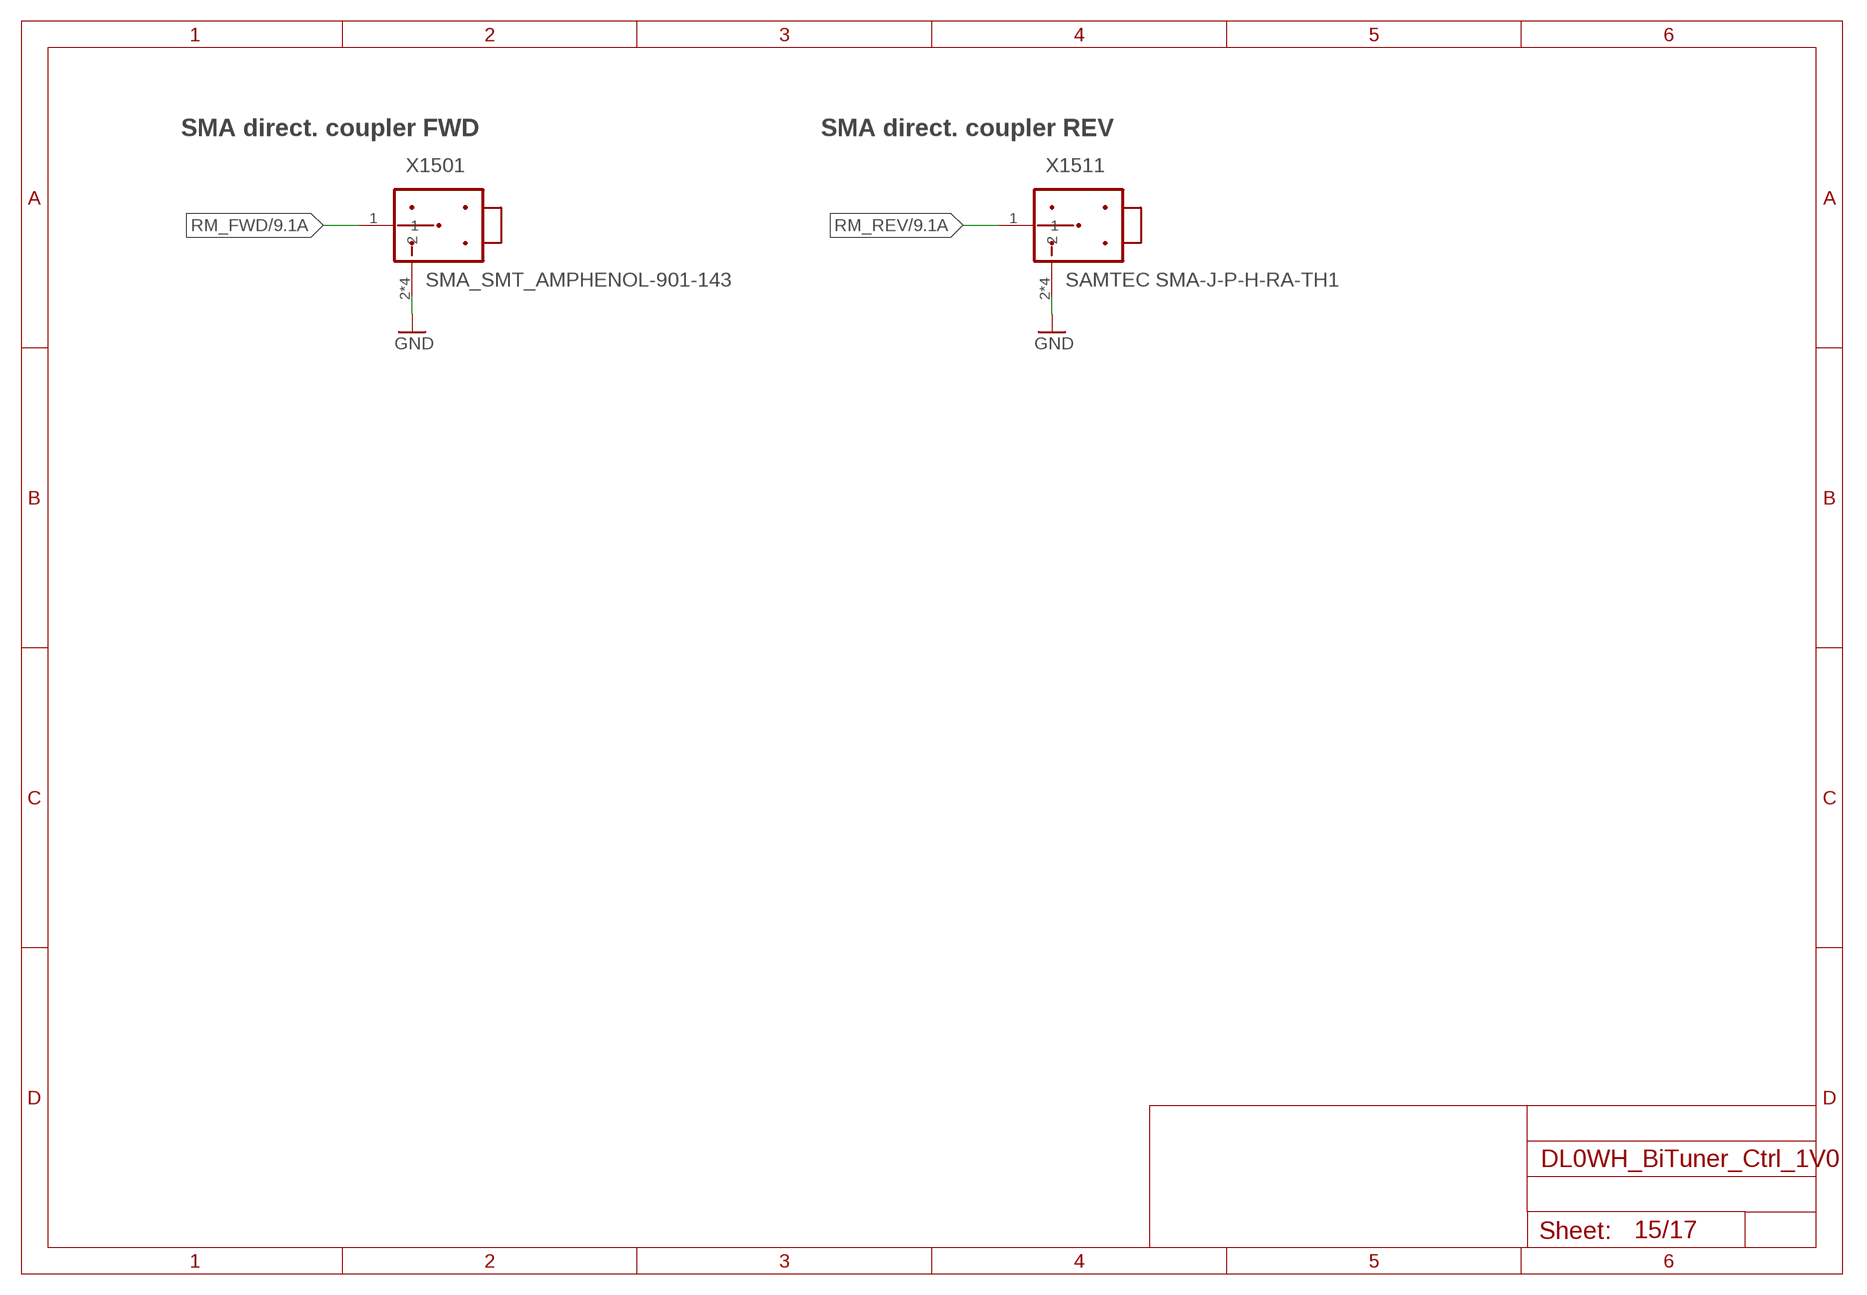
[diagram p14: schematic, sheet 15]
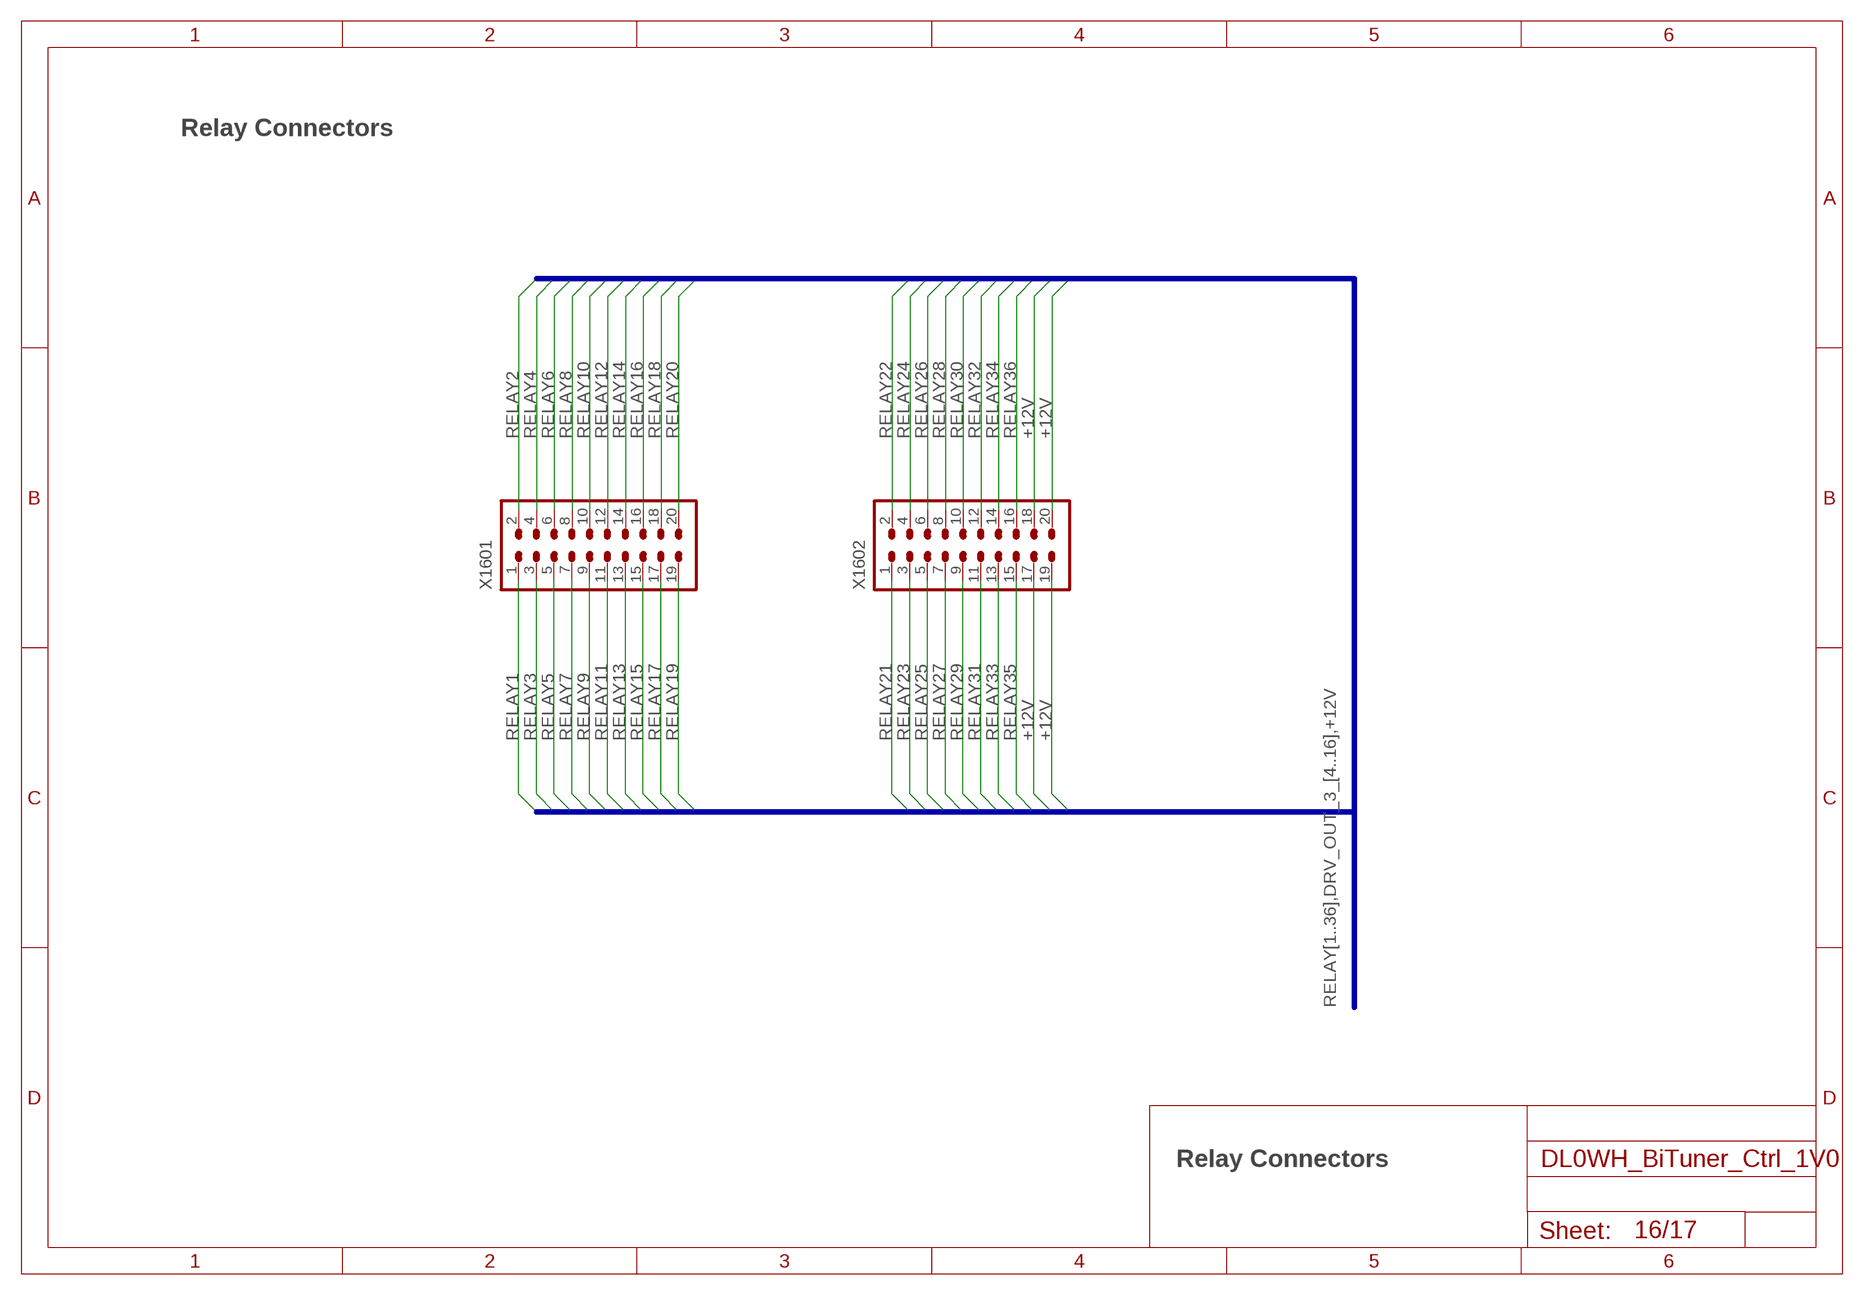
[diagram p15: schematic, sheet 16]
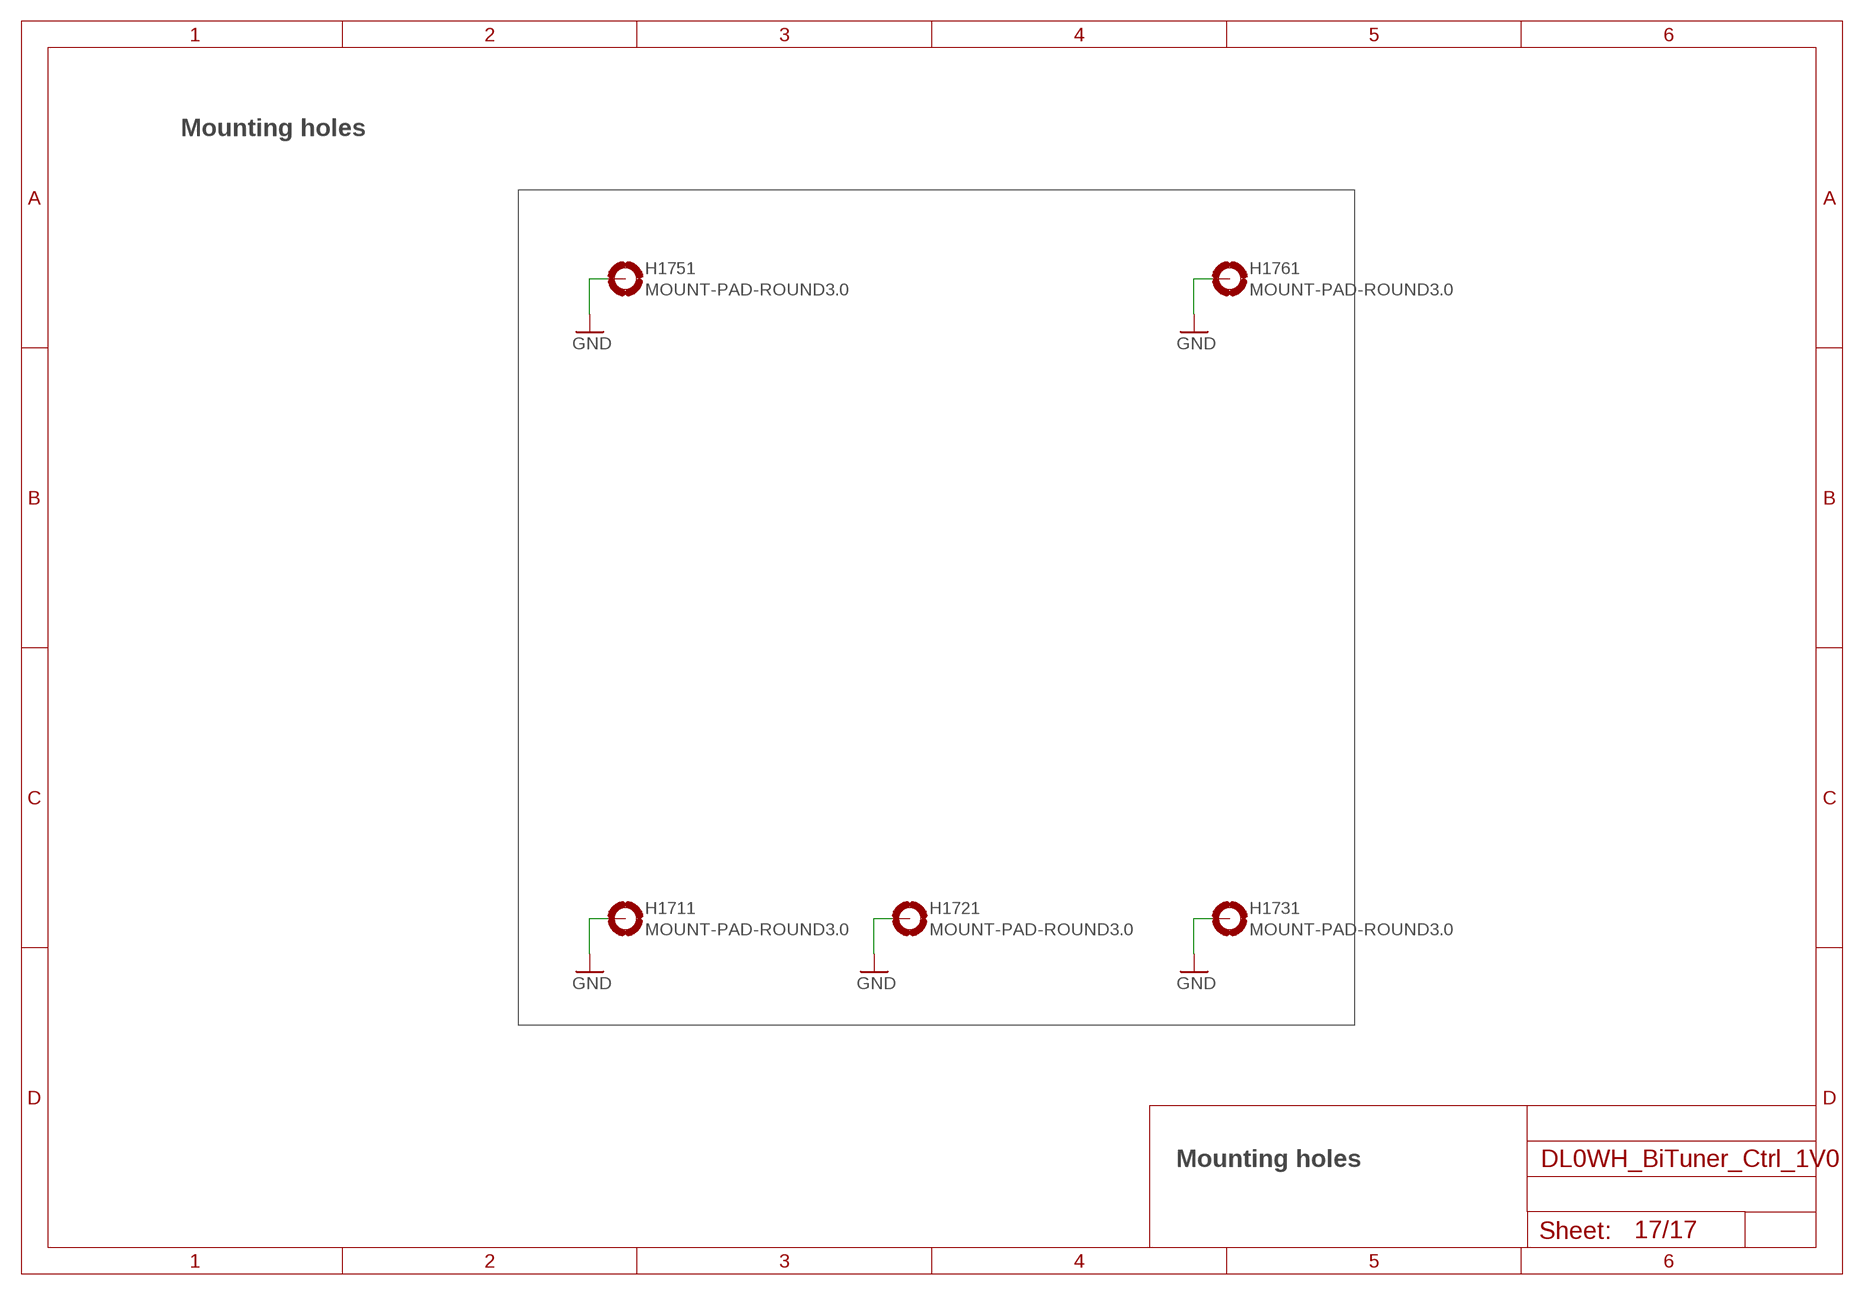
[diagram p16: schematic, sheet 17]

(export (version "E")
  (design (tool "Eeschema 10.0.6"))
  (components
    (comp (ref "C1301")
      (value "22uF")
      (footprint "eagle-import:C0603")
      (libsource (lib "eagle-import") (part "C-EUC0603"))
    )
    (comp (ref "C1311")
      (value "22uF")
      (footprint "eagle-import:C0603")
      (libsource (lib "eagle-import") (part "C-EUC0603"))
    )
    (comp (ref "L1311")
      (value "10uH")
      (footprint "eagle-import:L_4.50MM_X_3.20MM")
      (libsource (lib "eagle-import") (part "L-EU4.50X3.20MM"))
    )
    (comp (ref "R1301")
      (value "100kR")
      (footprint "eagle-import:R0402")
      (libsource (lib "eagle-import") (part "R-EU_R0402"))
    )
    (comp (ref "R1302")
      (value "220kR")
      (footprint "eagle-import:R0402")
      (libsource (lib "eagle-import") (part "R-EU_R0402"))
    )
    (comp (ref "R1321")
      (value "1MR")
      (footprint "eagle-import:R0402")
      (libsource (lib "eagle-import") (part "R-EU_R0402"))
    )
    (comp (ref "R1322")
      (value "1MR")
      (footprint "eagle-import:R0402")
      (libsource (lib "eagle-import") (part "R-EU_R0402"))
    )
    (comp (ref "U1301")
      (value "TPS62056")
      (footprint "eagle-import:S-PDSO-G10")
      (libsource (lib "eagle-import") (part "TPS62051"))
    )
    (comp (ref "C0901")
      (value "10nF")
      (footprint "eagle-import:C0402")
      (libsource (lib "eagle-import") (part "C-EUC0402"))
    )
    (comp (ref "C0911")
      (value "10nF")
      (footprint "eagle-import:C0402")
      (libsource (lib "eagle-import") (part "C-EUC0402"))
    )
    (comp (ref "C0921")
      (value "100nF")
      (footprint "eagle-import:C0402")
      (libsource (lib "eagle-import") (part "C-EUC0402"))
    )
    (comp (ref "C0951")
      (value "100nF")
      (footprint "eagle-import:C0402")
      (libsource (lib "eagle-import") (part "C-EUC0402"))
    )
    (comp (ref "D0901")
      (value "CRS08")
      (footprint "eagle-import:SOD80C")
      (libsource (lib "eagle-import") (part "CRS08"))
    )
    (comp (ref "D0911")
      (value "CRS08")
      (footprint "eagle-import:SOD80C")
      (libsource (lib "eagle-import") (part "CRS08"))
    )
    (comp (ref "D0951")
      (value "CMAD6001")
      (footprint "eagle-import:SOD923")
      (libsource (lib "eagle-import") (part "D_SOD923"))
    )
    (comp (ref "D0961")
      (value "CMAD6001")
      (footprint "eagle-import:SOD923")
      (libsource (lib "eagle-import") (part "D_SOD923"))
    )
    (comp (ref "L0901")
      (value "10uH")
      (footprint "eagle-import:L0603")
      (libsource (lib "eagle-import") (part "L-EUL0603"))
    )
    (comp (ref "L0911")
      (value "10uH")
      (footprint "eagle-import:L0603")
      (libsource (lib "eagle-import") (part "L-EUL0603"))
    )
    (comp (ref "R0901")
      (value "1kR")
      (footprint "eagle-import:R0402")
      (libsource (lib "eagle-import") (part "R-EU_R0402"))
    )
    (comp (ref "R0902")
      (value "15kR")
      (footprint "eagle-import:R0402")
      (libsource (lib "eagle-import") (part "R-EU_R0402"))
    )
    (comp (ref "R0903")
      (value "100kR")
      (footprint "eagle-import:R0402")
      (libsource (lib "eagle-import") (part "R-EU_R0402"))
    )
    (comp (ref "R0911")
      (value "1kR")
      (footprint "eagle-import:R0402")
      (libsource (lib "eagle-import") (part "R-EU_R0402"))
    )
    (comp (ref "R0912")
      (value "15kR")
      (footprint "eagle-import:R0402")
      (libsource (lib "eagle-import") (part "R-EU_R0402"))
    )
    (comp (ref "R0913")
      (value "100kR")
      (footprint "eagle-import:R0402")
      (libsource (lib "eagle-import") (part "R-EU_R0402"))
    )
    (comp (ref "R0921")
      (value "47R")
      (footprint "eagle-import:R0402")
      (libsource (lib "eagle-import") (part "R-EU_R0402"))
    )
    (comp (ref "R0922")
      (value "47R")
      (footprint "eagle-import:R0402")
      (libsource (lib "eagle-import") (part "R-EU_R0402"))
    )
    (comp (ref "R0951")
      (value "1MR")
      (footprint "eagle-import:R0402")
      (libsource (lib "eagle-import") (part "R-EU_R0402"))
    )
    (comp (ref "R0952")
      (value "47R")
      (footprint "eagle-import:R0402")
      (libsource (lib "eagle-import") (part "R-EU_R0402"))
    )
    (comp (ref "R0961")
      (value "10kR")
      (footprint "eagle-import:R0402")
      (libsource (lib "eagle-import") (part "R-EU_R0402"))
    )
    (comp (ref "U0921")
      (value "TS5A23166")
      (footprint "eagle-import:R-PDSO-G8")
      (libsource (lib "eagle-import") (part "TS5A23166"))
    )
    (comp (ref "U0951")
      (value "OPA354")
      (footprint "eagle-import:SOT-23-5")
      (fields (field (name "MPN") "OPA354AIDBVT"))
      (libsource (lib "eagle-import") (part "OPA354"))
    )
    (comp (ref "C0701")
      (value "100nF")
      (footprint "eagle-import:C0402")
      (libsource (lib "eagle-import") (part "C-EUC0402"))
    )
    (comp (ref "C0702")
      (value "100nF")
      (footprint "eagle-import:C0402")
      (libsource (lib "eagle-import") (part "C-EUC0402"))
    )
    (comp (ref "C0703")
      (value "22uF")
      (footprint "eagle-import:C0603")
      (libsource (lib "eagle-import") (part "C-EUC0603"))
    )
    (comp (ref "R0711")
      (value "47R")
      (footprint "eagle-import:R0402")
      (libsource (lib "eagle-import") (part "R-EU_R0402"))
    )
    (comp (ref "R0724")
      (value "47R")
      (footprint "eagle-import:R0402")
      (libsource (lib "eagle-import") (part "R-EU_R0402"))
    )
    (comp (ref "U0701")
      (value "MC33996")
      (footprint "eagle-import:SOICW32")
      (libsource (lib "eagle-import") (part "MC33996"))
    )
    (comp (ref "X1501")
      (value "SMA_SMT_AMPHENOL-901-143")
      (footprint "eagle-import:SMA_SMT_AMPHENOL_901-143")
      (fields (field (name "MPN") "901-143"))
      (libsource (lib "eagle-import") (part "SMA_SMT_AMPHENOL-901-143"))
    )
    (comp (ref "X1511")
      (value "SAMTEC SMA-J-P-H-RA-TH1")
      (footprint "eagle-import:SMA_SMT_AMPHENOL_901-143")
      (fields (field (name "MPN") "901-143"))
      (libsource (lib "eagle-import") (part "SMA_SMT_AMPHENOL-901-143"))
    )
    (comp (ref "R0511")
      (value "1kR")
      (footprint "eagle-import:R0402")
      (libsource (lib "eagle-import") (part "R-EU_R0402"))
    )
    (comp (ref "R0512")
      (value "1kR")
      (footprint "eagle-import:R0402")
      (libsource (lib "eagle-import") (part "R-EU_R0402"))
    )
    (comp (ref "X0601")
      (value "HEADER-2X2")
      (footprint "eagle-import:2X02")
      (libsource (lib "eagle-import") (part "HEADER-2X2"))
    )
    (comp (ref "C0401")
      (value "100nF")
      (footprint "eagle-import:C0402")
      (libsource (lib "eagle-import") (part "C-EUC0402"))
    )
    (comp (ref "C0402")
      (value "100nF")
      (footprint "eagle-import:C0402")
      (libsource (lib "eagle-import") (part "C-EUC0402"))
    )
    (comp (ref "C0403")
      (value "100nF")
      (footprint "eagle-import:C0402")
      (libsource (lib "eagle-import") (part "C-EUC0402"))
    )
    (comp (ref "C0410")
      (value "4.7uF")
      (footprint "eagle-import:C0603")
      (libsource (lib "eagle-import") (part "C-EUC0603"))
    )
    (comp (ref "C0412")
      (value "10nF")
      (footprint "eagle-import:C0402")
      (libsource (lib "eagle-import") (part "C-EUC0402"))
    )
    (comp (ref "C0413")
      (value "1uF")
      (footprint "eagle-import:C0402")
      (libsource (lib "eagle-import") (part "C-EUC0402"))
    )
    (comp (ref "C0451")
      (value "47uF")
      (footprint "eagle-import:C0805")
      (libsource (lib "eagle-import") (part "C-EUC0805"))
    )
    (comp (ref "L0411")
      (value "10uH")
      (footprint "eagle-import:L0603")
      (libsource (lib "eagle-import") (part "L-EUL0603"))
    )
    (comp (ref "R0441")
      (value "0R")
      (footprint "eagle-import:R0402")
      (libsource (lib "eagle-import") (part "R-EU_R0402"))
    )
    (comp (ref "SJ0401")
      (value "SJ")
      (footprint "eagle-import:SJ")
      (libsource (lib "eagle-import") (part "SJ"))
    )
    (comp (ref "TP_VBAT")
      (value "PTR1B1,27")
      (footprint "eagle-import:B1,27")
      (libsource (lib "eagle-import") (part "PTR1B1,27"))
    )
    (comp (ref "X1601")
      (value "2X10_2MM56_SOCKET")
      (footprint "eagle-import:2X10")
      (libsource (lib "eagle-import") (part "2X10_2MM56_SOCKET"))
    )
    (comp (ref "X1602")
      (value "2X10_2MM56_SOCKET")
      (footprint "eagle-import:2X10")
      (libsource (lib "eagle-import") (part "2X10_2MM56_SOCKET"))
    )
    (comp (ref "C0801")
      (value "100nF")
      (footprint "eagle-import:C0402")
      (libsource (lib "eagle-import") (part "C-EUC0402"))
    )
    (comp (ref "C0802")
      (value "100nF")
      (footprint "eagle-import:C0402")
      (libsource (lib "eagle-import") (part "C-EUC0402"))
    )
    (comp (ref "C0803")
      (value "22uF")
      (footprint "eagle-import:C0603")
      (libsource (lib "eagle-import") (part "C-EUC0603"))
    )
    (comp (ref "R0811")
      (value "47R")
      (footprint "eagle-import:R0402")
      (libsource (lib "eagle-import") (part "R-EU_R0402"))
    )
    (comp (ref "R0824")
      (value "47R")
      (footprint "eagle-import:R0402")
      (libsource (lib "eagle-import") (part "R-EU_R0402"))
    )
    (comp (ref "U0801")
      (value "MC33996")
      (footprint "eagle-import:SOICW32")
      (libsource (lib "eagle-import") (part "MC33996"))
    )
    (comp (ref "C1101")
      (value "1uF")
      (footprint "eagle-import:C0402")
      (libsource (lib "eagle-import") (part "C-EUC0402"))
    )
    (comp (ref "C1102")
      (value "1uF")
      (footprint "eagle-import:C0402")
      (libsource (lib "eagle-import") (part "C-EUC0402"))
    )
    (comp (ref "C1103")
      (value "1uF")
      (footprint "eagle-import:C0402")
      (libsource (lib "eagle-import") (part "C-EUC0402"))
    )
    (comp (ref "C1104")
      (value "1uF")
      (footprint "eagle-import:C0402")
      (libsource (lib "eagle-import") (part "C-EUC0402"))
    )
    (comp (ref "C1105")
      (value "1uF")
      (footprint "eagle-import:C0402")
      (libsource (lib "eagle-import") (part "C-EUC0402"))
    )
    (comp (ref "C1151")
      (value "10nF")
      (footprint "eagle-import:C0603")
      (libsource (lib "eagle-import") (part "C-EUC0603"))
    )
    (comp (ref "C1152")
      (value "10nF")
      (footprint "eagle-import:C0603")
      (libsource (lib "eagle-import") (part "C-EUC0603"))
    )
    (comp (ref "C1153")
      (value "10nF")
      (footprint "eagle-import:C0603")
      (libsource (lib "eagle-import") (part "C-EUC0603"))
    )
    (comp (ref "C1154")
      (value "10nF")
      (footprint "eagle-import:C0603")
      (libsource (lib "eagle-import") (part "C-EUC0603"))
    )
    (comp (ref "R1101")
      (value "47R")
      (footprint "eagle-import:R0402")
      (libsource (lib "eagle-import") (part "R-EU_R0402"))
    )
    (comp (ref "R1102")
      (value "47R")
      (footprint "eagle-import:R0402")
      (libsource (lib "eagle-import") (part "R-EU_R0402"))
    )
    (comp (ref "R1103")
      (value "47R")
      (footprint "eagle-import:R0402")
      (libsource (lib "eagle-import") (part "R-EU_R0402"))
    )
    (comp (ref "R1104")
      (value "47R")
      (footprint "eagle-import:R0402")
      (libsource (lib "eagle-import") (part "R-EU_R0402"))
    )
    (comp (ref "U1101")
      (value "MAX232_SOIC16")
      (footprint "eagle-import:SOIC16N")
      (fields (field (name "MF") "MAXIM") (field (name "MPN") "MAX232ECDR"))
      (libsource (lib "eagle-import") (part "MAX232_SOIC16"))
    )
    (comp (ref "X1151")
      (value "WIRE-TO-BOARD_5MM08_1X02")
      (footprint "eagle-import:WIRE-TO-BOARD_5MM08_1X02")
      (libsource (lib "eagle-import") (part "WIRE-TO-BOARD_5MM08_1X02"))
    )
    (comp (ref "X1152")
      (value "WIRE-TO-BOARD_5MM08_1X02")
      (footprint "eagle-import:WIRE-TO-BOARD_5MM08_1X02")
      (libsource (lib "eagle-import") (part "WIRE-TO-BOARD_5MM08_1X02"))
    )
    (comp (ref "X1153")
      (value "WIRE-TO-BOARD_5MM08_1X02")
      (footprint "eagle-import:WIRE-TO-BOARD_5MM08_1X02")
      (libsource (lib "eagle-import") (part "WIRE-TO-BOARD_5MM08_1X02"))
    )
    (comp (ref "C0054")
      (value "10nF")
      (footprint "eagle-import:C0603")
      (libsource (lib "eagle-import") (part "C-EUC0603"))
    )
    (comp (ref "C1001")
      (value "1uF")
      (footprint "eagle-import:C0402")
      (libsource (lib "eagle-import") (part "C-EUC0402"))
    )
    (comp (ref "C1002")
      (value "1uF")
      (footprint "eagle-import:C0402")
      (libsource (lib "eagle-import") (part "C-EUC0402"))
    )
    (comp (ref "C1003")
      (value "1uF")
      (footprint "eagle-import:C0402")
      (libsource (lib "eagle-import") (part "C-EUC0402"))
    )
    (comp (ref "C1004")
      (value "1uF")
      (footprint "eagle-import:C0402")
      (libsource (lib "eagle-import") (part "C-EUC0402"))
    )
    (comp (ref "C1005")
      (value "1uF")
      (footprint "eagle-import:C0402")
      (libsource (lib "eagle-import") (part "C-EUC0402"))
    )
    (comp (ref "C1051")
      (value "10nF")
      (footprint "eagle-import:C0603")
      (libsource (lib "eagle-import") (part "C-EUC0603"))
    )
    (comp (ref "C1052")
      (value "10nF")
      (footprint "eagle-import:C0603")
      (libsource (lib "eagle-import") (part "C-EUC0603"))
    )
    (comp (ref "C1053")
      (value "10nF")
      (footprint "eagle-import:C0603")
      (libsource (lib "eagle-import") (part "C-EUC0603"))
    )
    (comp (ref "R1001")
      (value "47R")
      (footprint "eagle-import:R0402")
      (libsource (lib "eagle-import") (part "R-EU_R0402"))
    )
    (comp (ref "R1002")
      (value "47R")
      (footprint "eagle-import:R0402")
      (libsource (lib "eagle-import") (part "R-EU_R0402"))
    )
    (comp (ref "R1003")
      (value "47R")
      (footprint "eagle-import:R0402")
      (libsource (lib "eagle-import") (part "R-EU_R0402"))
    )
    (comp (ref "R1004")
      (value "47R")
      (footprint "eagle-import:R0402")
      (libsource (lib "eagle-import") (part "R-EU_R0402"))
    )
    (comp (ref "U1001")
      (value "MAX232_SOIC16")
      (footprint "eagle-import:SOIC16N")
      (fields (field (name "MF") "MAXIM") (field (name "MPN") "MAX232ECDR"))
      (libsource (lib "eagle-import") (part "MAX232_SOIC16"))
    )
    (comp (ref "X1051")
      (value "WIRE-TO-BOARD_5MM08_1X02")
      (footprint "eagle-import:WIRE-TO-BOARD_5MM08_1X02")
      (libsource (lib "eagle-import") (part "WIRE-TO-BOARD_5MM08_1X02"))
    )
    (comp (ref "X1052")
      (value "WIRE-TO-BOARD_5MM08_1X02")
      (footprint "eagle-import:WIRE-TO-BOARD_5MM08_1X02")
      (libsource (lib "eagle-import") (part "WIRE-TO-BOARD_5MM08_1X02"))
    )
    (comp (ref "X1053")
      (value "WIRE-TO-BOARD_5MM08_1X02")
      (footprint "eagle-import:WIRE-TO-BOARD_5MM08_1X02")
      (libsource (lib "eagle-import") (part "WIRE-TO-BOARD_5MM08_1X02"))
    )
    (comp (ref "C0213")
      (value "100nF")
      (footprint "eagle-import:C0402")
      (libsource (lib "eagle-import") (part "C-EUC0402"))
    )
    (comp (ref "R0221")
      (value "33kR")
      (footprint "eagle-import:R0402")
      (libsource (lib "eagle-import") (part "R-EU_R0402"))
    )
    (comp (ref "R0231")
      (value "220kR")
      (footprint "eagle-import:R0402")
      (libsource (lib "eagle-import") (part "R-EU_R0402"))
    )
    (comp (ref "R0232")
      (value "220kR")
      (footprint "eagle-import:R0402")
      (libsource (lib "eagle-import") (part "R-EU_R0402"))
    )
    (comp (ref "S0212")
      (value "KSR223GLFG")
      (footprint "eagle-import:KSR223G_SMD_1POL")
      (libsource (lib "eagle-import") (part "KSR223G_SMD_1POL"))
    )
    (comp (ref "X0201")
      (value "HEADER-2X5_1MM27CORTEX_10PIN_JTAG-SWD")
      (footprint "eagle-import:2X05_SHROUDED_1MM27")
      (libsource (lib "eagle-import") (part "HEADER-2X5_1MM27CORTEX_10PIN_JTAG-SWD"))
    )
    (comp (ref "X0222")
      (value "HEADER-1X2")
      (footprint "eagle-import:1X02")
      (libsource (lib "eagle-import") (part "HEADER-1X2"))
    )
    (comp (ref "U0101")
      (value "STM32L476RXT_64PIN_LDO")
      (footprint "eagle-import:LQFP64")
      (libsource (lib "eagle-import") (part "STM32L476RXT_64PIN_LDO"))
    )
    (comp (ref "C0311")
      (value "18pF")
      (footprint "eagle-import:C0402")
      (libsource (lib "eagle-import") (part "C-EUC0402"))
    )
    (comp (ref "C0331")
      (value "JR200")
      (footprint "eagle-import:3MM2_X_2MM5")
      (libsource (lib "eagle-import") (part "C-TRIMM3MM2_2MM5"))
    )
    (comp (ref "C0332")
      (value "8.2pF")
      (footprint "eagle-import:C0402")
      (libsource (lib "eagle-import") (part "C-EUC0402"))
    )
    (comp (ref "Q0321")
      (value "ABS07-32.768KHZ")
      (footprint "eagle-import:ABS07")
      (fields (field (name "MANUFACTURER") "ABS07-32.768KHZ-1-T"))
      (libsource (lib "eagle-import") (part "ABS07-32.768KHZ"))
    )
    (comp (ref "H1711")
      (value "MOUNT-PAD-ROUND3.0")
      (footprint "eagle-import:3,0-PAD")
      (libsource (lib "eagle-import") (part "MOUNT-PAD-ROUND3.0"))
    )
    (comp (ref "H1721")
      (value "MOUNT-PAD-ROUND3.0")
      (footprint "eagle-import:3,0-PAD")
      (libsource (lib "eagle-import") (part "MOUNT-PAD-ROUND3.0"))
    )
    (comp (ref "H1731")
      (value "MOUNT-PAD-ROUND3.0")
      (footprint "eagle-import:3,0-PAD")
      (libsource (lib "eagle-import") (part "MOUNT-PAD-ROUND3.0"))
    )
    (comp (ref "H1751")
      (value "MOUNT-PAD-ROUND3.0")
      (footprint "eagle-import:3,0-PAD")
      (libsource (lib "eagle-import") (part "MOUNT-PAD-ROUND3.0"))
    )
    (comp (ref "H1761")
      (value "MOUNT-PAD-ROUND3.0")
      (footprint "eagle-import:3,0-PAD")
      (libsource (lib "eagle-import") (part "MOUNT-PAD-ROUND3.0"))
    )
    (comp (ref "C1201")
      (value "10uF")
      (footprint "eagle-import:C0603")
      (libsource (lib "eagle-import") (part "C-EUC0603"))
    )
    (comp (ref "C1202")
      (value "10uF")
      (footprint "eagle-import:C0603")
      (libsource (lib "eagle-import") (part "C-EUC0603"))
    )
    (comp (ref "C1203")
      (value "10uF")
      (footprint "eagle-import:C0603")
      (libsource (lib "eagle-import") (part "C-EUC0603"))
    )
    (comp (ref "C1204")
      (value "10nF")
      (footprint "eagle-import:C0402")
      (libsource (lib "eagle-import") (part "C-EUC0402"))
    )
    (comp (ref "C1205")
      (value "3.3uF")
      (footprint "eagle-import:C0603")
      (libsource (lib "eagle-import") (part "C-EUC0603"))
    )
    (comp (ref "C1211")
      (value "0.47uF")
      (footprint "eagle-import:C0402")
      (libsource (lib "eagle-import") (part "C-EUC0402"))
    )
    (comp (ref "C1212")
      (value "100nF")
      (footprint "eagle-import:C0402")
      (libsource (lib "eagle-import") (part "C-EUC0402"))
    )
    (comp (ref "C1221")
      (value "22uF")
      (footprint "eagle-import:C0603")
      (libsource (lib "eagle-import") (part "C-EUC0603"))
    )
    (comp (ref "C1222")
      (value "22uF")
      (footprint "eagle-import:C0603")
      (libsource (lib "eagle-import") (part "C-EUC0603"))
    )
    (comp (ref "C1223")
      (value "22uF")
      (footprint "eagle-import:C0603")
      (libsource (lib "eagle-import") (part "C-EUC0603"))
    )
    (comp (ref "L1211")
      (value "2.2uH")
      (footprint "eagle-import:L_6.00MM_X_6.00MM")
      (libsource (lib "eagle-import") (part "L-EU6.00X6.00MM"))
    )
    (comp (ref "R1211")
      (value "3R")
      (footprint "eagle-import:R0402")
      (libsource (lib "eagle-import") (part "R-EU_R0402"))
    )
    (comp (ref "U1201")
      (value "LM53603-Q1")
      (footprint "eagle-import:HTSSOP16")
      (libsource (lib "eagle-import") (part "LM53603-Q1"))
    )
    (comp (ref "X1211")
      (value "WIRE-TO-BOARD_5MM08_1X02")
      (footprint "eagle-import:WIRE-TO-BOARD_5MM08_1X02")
      (libsource (lib "eagle-import") (part "WIRE-TO-BOARD_5MM08_1X02"))
    )
    (comp (ref "C1403")
      (value "1nF")
      (footprint "eagle-import:C0402")
      (libsource (lib "eagle-import") (part "C-EUC0402"))
    )
    (comp (ref "PF1411")
      (value "1.1A/2.2A")
      (footprint "eagle-import:M1206")
      (libsource (lib "eagle-import") (part "rcl_R-EU_M1206"))
    )
    (comp (ref "R1402")
      (value "330kR")
      (footprint "eagle-import:R0402")
      (libsource (lib "eagle-import") (part "R-EU_R0402"))
    )
    (comp (ref "X1401")
      (value "MOLEX 105017-0001")
      (footprint "eagle-import:USB-B-MICRO-SMD_MOLEX-105017-0001")
      (libsource (lib "eagle-import") (part "USB_MICRO-B_MOLEX"))
    )
    (comp (ref "C0601")
      (value "100nF")
      (footprint "eagle-import:C0402")
      (libsource (lib "eagle-import") (part "C-EUC0402"))
    )
    (comp (ref "C0602")
      (value "100nF")
      (footprint "eagle-import:C0402")
      (libsource (lib "eagle-import") (part "C-EUC0402"))
    )
    (comp (ref "C0603")
      (value "22uF")
      (footprint "eagle-import:C0603")
      (libsource (lib "eagle-import") (part "C-EUC0603"))
    )
    (comp (ref "R0611")
      (value "47R")
      (footprint "eagle-import:R0402")
      (libsource (lib "eagle-import") (part "R-EU_R0402"))
    )
    (comp (ref "R0621")
      (value "47R")
      (footprint "eagle-import:R0402")
      (libsource (lib "eagle-import") (part "R-EU_R0402"))
    )
    (comp (ref "R0622")
      (value "0R")
      (footprint "eagle-import:R0402")
      (libsource (lib "eagle-import") (part "R-EU_R0402"))
    )
    (comp (ref "R0623")
      (value "47R")
      (footprint "eagle-import:R0402")
      (libsource (lib "eagle-import") (part "R-EU_R0402"))
    )
    (comp (ref "R0624")
      (value "47R")
      (footprint "eagle-import:R0402")
      (libsource (lib "eagle-import") (part "R-EU_R0402"))
    )
    (comp (ref "R0625")
      (value "47R")
      (footprint "eagle-import:R0402")
      (libsource (lib "eagle-import") (part "R-EU_R0402"))
    )
    (comp (ref "R0626")
      (value "47R")
      (footprint "eagle-import:R0402")
      (libsource (lib "eagle-import") (part "R-EU_R0402"))
    )
    (comp (ref "U0601")
      (value "MC33996")
      (footprint "eagle-import:SOICW32")
      (libsource (lib "eagle-import") (part "MC33996"))
    )
  )
  (nets
    (net (code "26") (name "+3V3") (class "Default")
      (node (ref "C0601") (pin "2") (pinfunction "2_2") (pintype "passive"))
      (node (ref "C0701") (pin "2") (pinfunction "2_2") (pintype "passive"))
      (node (ref "C0801") (pin "2") (pinfunction "2_2") (pintype "passive"))
      (node (ref "C0921") (pin "1") (pinfunction "1_1") (pintype "passive"))
      (node (ref "C0951") (pin "1") (pinfunction "1_1") (pintype "passive"))
      (node (ref "C1311") (pin "1") (pinfunction "1_1") (pintype "passive"))
      (node (ref "D0901") (pin "C") (pinfunction "C_C") (pintype "passive"))
      (node (ref "D0911") (pin "C") (pinfunction "C_C") (pintype "passive"))
      (node (ref "L1311") (pin "1") (pinfunction "1_1") (pintype "passive"))
      (node (ref "L1311") (pin "3") (pinfunction "1_3") (pintype "passive"))
      (node (ref "R0231") (pin "2") (pinfunction "2_2") (pintype "passive"))
      (node (ref "R0511") (pin "2") (pinfunction "2_2") (pintype "passive"))
      (node (ref "R0512") (pin "2") (pinfunction "2_2") (pintype "passive"))
      (node (ref "R0903") (pin "2") (pinfunction "2_2") (pintype "passive"))
      (node (ref "R0913") (pin "2") (pinfunction "2_2") (pintype "passive"))
      (node (ref "R0961") (pin "1") (pinfunction "1_1") (pintype "passive"))
      (node (ref "R1321") (pin "2") (pinfunction "2_2") (pintype "passive"))
      (node (ref "R1322") (pin "2") (pinfunction "2_2") (pintype "passive"))
      (node (ref "SJ0401") (pin "1") (pinfunction "1_1") (pintype "passive"))
      (node (ref "U0601") (pin "3") (pinfunction "SOPWR_3") (pintype "power_in"))
      (node (ref "U0701") (pin "3") (pinfunction "SOPWR_3") (pintype "power_in"))
      (node (ref "U0801") (pin "3") (pinfunction "SOPWR_3") (pintype "power_in"))
      (node (ref "U0921") (pin "8") (pinfunction "8_8") (pintype "power_in"))
      (node (ref "U0951") (pin "5") (pinfunction "V+_5") (pintype "power_in"))
      (node (ref "U1301") (pin "5") (pinfunction "FB_5") (pintype "passive"))
      (node (ref "X0201") (pin "1") (pinfunction "1_1") (pintype "passive"))
      (node (ref "X0222") (pin "1") (pinfunction "1_1") (pintype "passive"))
    )
    (net (code "27") (name "+5V") (class "Default")
      (node (ref "C1001") (pin "1") (pinfunction "1_1") (pintype "passive"))
      (node (ref "C1101") (pin "1") (pinfunction "1_1") (pintype "passive"))
      (node (ref "C1221") (pin "1") (pinfunction "1_1") (pintype "passive"))
      (node (ref "C1222") (pin "1") (pinfunction "1_1") (pintype "passive"))
      (node (ref "C1223") (pin "1") (pinfunction "1_1") (pintype "passive"))
      (node (ref "C1301") (pin "1") (pinfunction "1_1") (pintype "passive"))
      (node (ref "L1211") (pin "1") (pinfunction "1_1") (pintype "passive"))
      (node (ref "R1211") (pin "2") (pinfunction "2_2") (pintype "passive"))
      (node (ref "R1302") (pin "2") (pinfunction "2_2") (pintype "passive"))
      (node (ref "U1001") (pin "16") (pinfunction "VCC_16") (pintype "power_in"))
      (node (ref "U1101") (pin "16") (pinfunction "VCC_16") (pintype "power_in"))
      (node (ref "U1201") (pin "9") (pinfunction "FB_9") (pintype "passive"))
      (node (ref "U1301") (pin "1") (pinfunction "VIN_1") (pintype "power_in"))
      (node (ref "U1301") (pin "8") (pinfunction "EN_8") (pintype "input"))
    )
    (net (code "28") (name "+12V") (class "Default")
      (node (ref "C0602") (pin "1") (pinfunction "1_1") (pintype "passive"))
      (node (ref "C0603") (pin "1") (pinfunction "1_1") (pintype "passive"))
      (node (ref "C0702") (pin "1") (pinfunction "1_1") (pintype "passive"))
      (node (ref "C0703") (pin "1") (pinfunction "1_1") (pintype "passive"))
      (node (ref "C0802") (pin "1") (pinfunction "1_1") (pintype "passive"))
      (node (ref "C0803") (pin "1") (pinfunction "1_1") (pintype "passive"))
      (node (ref "C1201") (pin "1") (pinfunction "1_1") (pintype "passive"))
      (node (ref "C1202") (pin "1") (pinfunction "1_1") (pintype "passive"))
      (node (ref "C1203") (pin "1") (pinfunction "1_1") (pintype "passive"))
      (node (ref "C1204") (pin "1") (pinfunction "1_1") (pintype "passive"))
      (node (ref "U0601") (pin "6") (pinfunction "VPWR_6") (pintype "power_in"))
      (node (ref "U0701") (pin "6") (pinfunction "VPWR_6") (pintype "power_in"))
      (node (ref "U0801") (pin "6") (pinfunction "VPWR_6") (pintype "power_in"))
      (node (ref "U1201") (pin "11") (pinfunction "EN_11") (pintype "input"))
      (node (ref "U1201") (pin "12") (pinfunction "VIN_12") (pintype "power_in"))
      (node (ref "U1201") (pin "13") (pinfunction "VIN_13") (pintype "power_in"))
      (node (ref "X1211") (pin "1") (pinfunction "1_1") (pintype "passive"))
      (node (ref "X1602") (pin "17") (pinfunction "17_17") (pintype "passive"))
      (node (ref "X1602") (pin "18") (pinfunction "18_18") (pintype "passive"))
      (node (ref "X1602") (pin "19") (pinfunction "19_19") (pintype "passive"))
      (node (ref "X1602") (pin "20") (pinfunction "20_20") (pintype "passive"))
    )
    (net (code "40") (name "CAT_DTE_CTS") (class "Default")
      (node (ref "C1153") (pin "1") (pinfunction "1_1") (pintype "passive"))
      (node (ref "U1101") (pin "7") (pinfunction "T2OUT_7") (pintype "output"))
      (node (ref "X1153") (pin "1") (pinfunction "1_1") (pintype "passive"))
    )
    (net (code "41") (name "CAT_DTE_RTR") (class "Default")
      (node (ref "C1154") (pin "1") (pinfunction "1_1") (pintype "passive"))
      (node (ref "U1101") (pin "8") (pinfunction "R2IN_8") (pintype "input"))
      (node (ref "X1153") (pin "2") (pinfunction "2_2") (pintype "passive"))
    )
    (net (code "42") (name "CAT_DTE_RXD") (class "Default")
      (node (ref "C1151") (pin "1") (pinfunction "1_1") (pintype "passive"))
      (node (ref "U1101") (pin "14") (pinfunction "T1OUT_14") (pintype "output"))
      (node (ref "X1151") (pin "1") (pinfunction "1_1") (pintype "passive"))
    )
    (net (code "43") (name "CAT_DTE_TXD") (class "Default")
      (node (ref "C1152") (pin "1") (pinfunction "1_1") (pintype "passive"))
      (node (ref "U1101") (pin "13") (pinfunction "R1IN_13") (pintype "input"))
      (node (ref "X1151") (pin "2") (pinfunction "2_2") (pintype "passive"))
    )
    (net (code "44") (name "CAT_MX_C1P") (class "Default")
      (node (ref "C1102") (pin "1") (pinfunction "1_1") (pintype "passive"))
      (node (ref "U1101") (pin "1") (pinfunction "C1+_1") (pintype "bidirectional"))
    )
    (net (code "45") (name "CAT_MX_C2P") (class "Default")
      (node (ref "C1103") (pin "1") (pinfunction "1_1") (pintype "passive"))
      (node (ref "U1101") (pin "4") (pinfunction "C2+_4") (pintype "bidirectional"))
    )
    (net (code "46") (name "CAT_MX_VM") (class "Default")
      (node (ref "C1105") (pin "1") (pinfunction "1_1") (pintype "passive"))
      (node (ref "U1101") (pin "6") (pinfunction "V-_6") (pintype "bidirectional"))
    )
    (net (code "47") (name "CAT_MX_VP") (class "Default")
      (node (ref "C1104") (pin "1") (pinfunction "1_1") (pintype "passive"))
      (node (ref "U1101") (pin "2") (pinfunction "V+_2") (pintype "bidirectional"))
    )
    (net (code "48") (name "DRV_OUT_3_4") (class "Default")
      (node (ref "U0801") (pin "12") (pinfunction "OUT4_12") (pintype "passive"))
    )
    (net (code "49") (name "DRV_OUT_3_5") (class "Default")
      (node (ref "U0801") (pin "13") (pinfunction "OUT5_13") (pintype "passive"))
    )
    (net (code "50") (name "DRV_OUT_3_6") (class "Default")
      (node (ref "U0801") (pin "15") (pinfunction "OUT6_15") (pintype "passive"))
    )
    (net (code "51") (name "DRV_OUT_3_7") (class "Default")
      (node (ref "U0801") (pin "16") (pinfunction "OUT7_16") (pintype "passive"))
    )
    (net (code "52") (name "DRV_OUT_3_8") (class "Default")
      (node (ref "U0801") (pin "17") (pinfunction "OUT8_17") (pintype "passive"))
    )
    (net (code "53") (name "DRV_OUT_3_9") (class "Default")
      (node (ref "U0801") (pin "18") (pinfunction "OUT9_18") (pintype "passive"))
    )
    (net (code "54") (name "DRV_OUT_3_10") (class "Default")
      (node (ref "U0801") (pin "20") (pinfunction "OUT10_20") (pintype "passive"))
    )
    (net (code "55") (name "DRV_OUT_3_11") (class "Default")
      (node (ref "U0801") (pin "21") (pinfunction "OUT11_21") (pintype "passive"))
    )
    (net (code "56") (name "DRV_OUT_3_12") (class "Default")
      (node (ref "U0801") (pin "28") (pinfunction "OUT12_28") (pintype "passive"))
    )
    (net (code "57") (name "DRV_OUT_3_13") (class "Default")
      (node (ref "U0801") (pin "29") (pinfunction "OUT13_29") (pintype "passive"))
    )
    (net (code "58") (name "DRV_OUT_3_14") (class "Default")
      (node (ref "U0801") (pin "31") (pinfunction "OUT14_31") (pintype "passive"))
    )
    (net (code "59") (name "DRV_OUT_3_15") (class "Default")
      (node (ref "U0801") (pin "32") (pinfunction "OUT15_32") (pintype "passive"))
    )
    (net (code "60") (name "GND") (class "Default")
      (node (ref "C0054") (pin "2") (pinfunction "2_2") (pintype "passive"))
      (node (ref "C0213") (pin "2") (pinfunction "2_2") (pintype "passive"))
      (node (ref "C0311") (pin "2") (pinfunction "2_2") (pintype "passive"))
      (node (ref "C0331") (pin "+") (pinfunction "A_+") (pintype "passive"))
      (node (ref "C0332") (pin "2") (pinfunction "2_2") (pintype "passive"))
      (node (ref "C0401") (pin "2") (pinfunction "2_2") (pintype "passive"))
      (node (ref "C0402") (pin "2") (pinfunction "2_2") (pintype "passive"))
      (node (ref "C0403") (pin "2") (pinfunction "2_2") (pintype "passive"))
      (node (ref "C0410") (pin "2") (pinfunction "2_2") (pintype "passive"))
      (node (ref "C0412") (pin "2") (pinfunction "2_2") (pintype "passive"))
      (node (ref "C0413") (pin "2") (pinfunction "2_2") (pintype "passive"))
      (node (ref "C0451") (pin "2") (pinfunction "2_2") (pintype "passive"))
      (node (ref "C0601") (pin "1") (pinfunction "1_1") (pintype "passive"))
      (node (ref "C0602") (pin "2") (pinfunction "2_2") (pintype "passive"))
      (node (ref "C0603") (pin "2") (pinfunction "2_2") (pintype "passive"))
      (node (ref "C0701") (pin "1") (pinfunction "1_1") (pintype "passive"))
      (node (ref "C0702") (pin "2") (pinfunction "2_2") (pintype "passive"))
      (node (ref "C0703") (pin "2") (pinfunction "2_2") (pintype "passive"))
      (node (ref "C0801") (pin "1") (pinfunction "1_1") (pintype "passive"))
      (node (ref "C0802") (pin "2") (pinfunction "2_2") (pintype "passive"))
      (node (ref "C0803") (pin "2") (pinfunction "2_2") (pintype "passive"))
      (node (ref "C0901") (pin "2") (pinfunction "2_2") (pintype "passive"))
      (node (ref "C0911") (pin "2") (pinfunction "2_2") (pintype "passive"))
      (node (ref "C0921") (pin "2") (pinfunction "2_2") (pintype "passive"))
      (node (ref "C0951") (pin "2") (pinfunction "2_2") (pintype "passive"))
      (node (ref "C1001") (pin "2") (pinfunction "2_2") (pintype "passive"))
      (node (ref "C1004") (pin "2") (pinfunction "2_2") (pintype "passive"))
      (node (ref "C1005") (pin "2") (pinfunction "2_2") (pintype "passive"))
      (node (ref "C1051") (pin "2") (pinfunction "2_2") (pintype "passive"))
      (node (ref "C1052") (pin "2") (pinfunction "2_2") (pintype "passive"))
      (node (ref "C1053") (pin "2") (pinfunction "2_2") (pintype "passive"))
      (node (ref "C1101") (pin "2") (pinfunction "2_2") (pintype "passive"))
      (node (ref "C1104") (pin "2") (pinfunction "2_2") (pintype "passive"))
      (node (ref "C1105") (pin "2") (pinfunction "2_2") (pintype "passive"))
      (node (ref "C1151") (pin "2") (pinfunction "2_2") (pintype "passive"))
      (node (ref "C1152") (pin "2") (pinfunction "2_2") (pintype "passive"))
      (node (ref "C1153") (pin "2") (pinfunction "2_2") (pintype "passive"))
      (node (ref "C1154") (pin "2") (pinfunction "2_2") (pintype "passive"))
      (node (ref "C1201") (pin "2") (pinfunction "2_2") (pintype "passive"))
      (node (ref "C1202") (pin "2") (pinfunction "2_2") (pintype "passive"))
      (node (ref "C1203") (pin "2") (pinfunction "2_2") (pintype "passive"))
      (node (ref "C1204") (pin "2") (pinfunction "2_2") (pintype "passive"))
      (node (ref "C1205") (pin "1") (pinfunction "1_1") (pintype "passive"))
      (node (ref "C1212") (pin "2") (pinfunction "2_2") (pintype "passive"))
      (node (ref "C1221") (pin "2") (pinfunction "2_2") (pintype "passive"))
      (node (ref "C1222") (pin "2") (pinfunction "2_2") (pintype "passive"))
      (node (ref "C1223") (pin "2") (pinfunction "2_2") (pintype "passive"))
      (node (ref "C1301") (pin "2") (pinfunction "2_2") (pintype "passive"))
      (node (ref "C1311") (pin "2") (pinfunction "2_2") (pintype "passive"))
      (node (ref "C1403") (pin "1") (pinfunction "1_1") (pintype "passive"))
      (node (ref "D0961") (pin "C") (pinfunction "C_C") (pintype "passive"))
      (node (ref "H1711") (pin "B3,0") (pinfunction "MOUNT_B3,0") (pintype "passive"))
      (node (ref "H1721") (pin "B3,0") (pinfunction "MOUNT_B3,0") (pintype "passive"))
      (node (ref "H1731") (pin "B3,0") (pinfunction "MOUNT_B3,0") (pintype "passive"))
      (node (ref "H1751") (pin "B3,0") (pinfunction "MOUNT_B3,0") (pintype "passive"))
      (node (ref "H1761") (pin "B3,0") (pinfunction "MOUNT_B3,0") (pintype "passive"))
      (node (ref "R0221") (pin "1") (pinfunction "1_1") (pintype "passive"))
      (node (ref "R0232") (pin "1") (pinfunction "1_1") (pintype "passive"))
      (node (ref "R0441") (pin "1") (pinfunction "1_1") (pintype "passive"))
      (node (ref "R0901") (pin "1") (pinfunction "1_1") (pintype "passive"))
      (node (ref "R0911") (pin "1") (pinfunction "1_1") (pintype "passive"))
      (node (ref "R0951") (pin "1") (pinfunction "1_1") (pintype "passive"))
      (node (ref "R1301") (pin "1") (pinfunction "1_1") (pintype "passive"))
      (node (ref "R1402") (pin "1") (pinfunction "1_1") (pintype "passive"))
      (node (ref "S0212") (pin "1") (pinfunction "P_1") (pintype "passive"))
      (node (ref "U0101") (pin "18") (pinfunction "VSS_18") (pintype "passive"))
      (node (ref "U0101") (pin "31") (pinfunction "VSS_31") (pintype "passive"))
      (node (ref "U0101") (pin "47") (pinfunction "VSS_47") (pintype "passive"))
      (node (ref "U0101") (pin "63") (pinfunction "VSS_63") (pintype "passive"))
      (node (ref "U0601") (pin "10") (pinfunction "GND_MC_10") (pintype "passive"))
      (node (ref "U0601") (pin "23") (pinfunction "GND_MC_23") (pintype "passive"))
      (node (ref "U0601") (pin "24") (pinfunction "GND_MC_24") (pintype "passive"))
      (node (ref "U0601") (pin "25") (pinfunction "GND_MC_25") (pintype "passive"))
      (node (ref "U0601") (pin "26") (pinfunction "GND_MC_26") (pintype "passive"))
      (node (ref "U0601") (pin "33") (pinfunction "EP_33") (pintype "passive"))
      (node (ref "U0601") (pin "7") (pinfunction "GND_MC_7") (pintype "passive"))
      (node (ref "U0601") (pin "8") (pinfunction "GND_MC_8") (pintype "passive"))
      (node (ref "U0601") (pin "9") (pinfunction "GND_MC_9") (pintype "passive"))
      (node (ref "U0701") (pin "10") (pinfunction "GND_MC_10") (pintype "passive"))
      (node (ref "U0701") (pin "23") (pinfunction "GND_MC_23") (pintype "passive"))
      (node (ref "U0701") (pin "24") (pinfunction "GND_MC_24") (pintype "passive"))
      (node (ref "U0701") (pin "25") (pinfunction "GND_MC_25") (pintype "passive"))
      (node (ref "U0701") (pin "26") (pinfunction "GND_MC_26") (pintype "passive"))
      (node (ref "U0701") (pin "33") (pinfunction "EP_33") (pintype "passive"))
      (node (ref "U0701") (pin "7") (pinfunction "GND_MC_7") (pintype "passive"))
      (node (ref "U0701") (pin "8") (pinfunction "GND_MC_8") (pintype "passive"))
      (node (ref "U0701") (pin "9") (pinfunction "GND_MC_9") (pintype "passive"))
      (node (ref "U0801") (pin "10") (pinfunction "GND_MC_10") (pintype "passive"))
      (node (ref "U0801") (pin "23") (pinfunction "GND_MC_23") (pintype "passive"))
      (node (ref "U0801") (pin "24") (pinfunction "GND_MC_24") (pintype "passive"))
      (node (ref "U0801") (pin "25") (pinfunction "GND_MC_25") (pintype "passive"))
      (node (ref "U0801") (pin "26") (pinfunction "GND_MC_26") (pintype "passive"))
      (node (ref "U0801") (pin "33") (pinfunction "EP_33") (pintype "passive"))
      (node (ref "U0801") (pin "7") (pinfunction "GND_MC_7") (pintype "passive"))
      (node (ref "U0801") (pin "8") (pinfunction "GND_MC_8") (pintype "passive"))
      (node (ref "U0801") (pin "9") (pinfunction "GND_MC_9") (pintype "passive"))
      (node (ref "U0921") (pin "4") (pinfunction "4_4") (pintype "passive"))
      (node (ref "U0951") (pin "2") (pinfunction "V-_2") (pintype "power_in"))
      (node (ref "U0951") (pin "3") (pinfunction "+IN_3") (pintype "input"))
      (node (ref "U1001") (pin "15") (pinfunction "GND_15") (pintype "power_in"))
      (node (ref "U1101") (pin "15") (pinfunction "GND_15") (pintype "power_in"))
      (node (ref "U1201") (pin "10") (pinfunction "AGND_10") (pintype "passive"))
      (node (ref "U1201") (pin "15") (pinfunction "PGND_15") (pintype "passive"))
      (node (ref "U1201") (pin "16") (pinfunction "PGND_16") (pintype "passive"))
      (node (ref "U1201") (pin "6") (pinfunction "SYNC_6") (pintype "input"))
      (node (ref "U1201") (pin "7") (pinfunction "FPWM_7") (pintype "input"))
      (node (ref "U1201") (pin "PAD") (pinfunction "EP_PAD") (pintype "passive"))
      (node (ref "U1201") (pin "PAD1") (pinfunction "EP_PAD1") (pintype "passive"))
      (node (ref "U1201") (pin "PAD10") (pinfunction "EP_PAD10") (pintype "passive"))
      (node (ref "U1201") (pin "PAD11") (pinfunction "EP_PAD11") (pintype "passive"))
      (node (ref "U1201") (pin "PAD12") (pinfunction "EP_PAD12") (pintype "passive"))
      (node (ref "U1201") (pin "PAD13") (pinfunction "EP_PAD13") (pintype "passive"))
      (node (ref "U1201") (pin "PAD2") (pinfunction "EP_PAD2") (pintype "passive"))
      (node (ref "U1201") (pin "PAD3") (pinfunction "EP_PAD3") (pintype "passive"))
      (node (ref "U1201") (pin "PAD4") (pinfunction "EP_PAD4") (pintype "passive"))
      (node (ref "U1201") (pin "PAD5") (pinfunction "EP_PAD5") (pintype "passive"))
      (node (ref "U1201") (pin "PAD6") (pinfunction "EP_PAD6") (pintype "passive"))
      (node (ref "U1201") (pin "PAD7") (pinfunction "EP_PAD7") (pintype "passive"))
      (node (ref "U1201") (pin "PAD8") (pinfunction "EP_PAD8") (pintype "passive"))
      (node (ref "U1201") (pin "PAD9") (pinfunction "EP_PAD9") (pintype "passive"))
      (node (ref "U1301") (pin "10") (pinfunction "PGND_10") (pintype "passive"))
      (node (ref "U1301") (pin "3") (pinfunction "VSS_3") (pintype "passive"))
      (node (ref "U1301") (pin "7") (pinfunction "SYNC_7") (pintype "input"))
      (node (ref "X0201") (pin "3") (pinfunction "3_3") (pintype "passive"))
      (node (ref "X0201") (pin "5") (pinfunction "5_5") (pintype "passive"))
      (node (ref "X0201") (pin "9") (pinfunction "9_9") (pintype "passive"))
      (node (ref "X0601") (pin "2") (pinfunction "2_2") (pintype "passive"))
      (node (ref "X0601") (pin "4") (pinfunction "4_4") (pintype "passive"))
      (node (ref "X1052") (pin "1") (pinfunction "1_1") (pintype "passive"))
      (node (ref "X1052") (pin "2") (pinfunction "2_2") (pintype "passive"))
      (node (ref "X1152") (pin "1") (pinfunction "1_1") (pintype "passive"))
      (node (ref "X1152") (pin "2") (pinfunction "2_2") (pintype "passive"))
      (node (ref "X1211") (pin "2") (pinfunction "2_2") (pintype "passive"))
      (node (ref "X1401") (pin "GND") (pinfunction "GND_GND") (pintype "passive"))
      (node (ref "X1501") (pin "2") (pinfunction "2_2") (pintype "passive"))
      (node (ref "X1501") (pin "3") (pinfunction "2_3") (pintype "passive"))
      (node (ref "X1501") (pin "4") (pinfunction "2_4") (pintype "passive"))
      (node (ref "X1501") (pin "5") (pinfunction "2_5") (pintype "passive"))
      (node (ref "X1511") (pin "2") (pinfunction "2_2") (pintype "passive"))
      (node (ref "X1511") (pin "3") (pinfunction "2_3") (pintype "passive"))
      (node (ref "X1511") (pin "4") (pinfunction "2_4") (pintype "passive"))
      (node (ref "X1511") (pin "5") (pinfunction "2_5") (pintype "passive"))
    )
    (net (code "61") (name "MCU_NRST") (class "Default")
      (node (ref "C0213") (pin "1") (pinfunction "1_1") (pintype "passive"))
      (node (ref "S0212") (pin "2") (pinfunction "S_2") (pintype "passive"))
      (node (ref "U0101") (pin "7") (pinfunction "NRST_7") (pintype "bidirectional"))
      (node (ref "X0201") (pin "10") (pinfunction "10_10") (pintype "passive"))
    )
    (net (code "62") (name "MCU_VBAT") (class "Default")
      (node (ref "C0451") (pin "1") (pinfunction "1_1") (pintype "passive"))
      (node (ref "TP_VBAT") (pin "TP") (pinfunction "TP_TP") (pintype "input"))
      (node (ref "U0101") (pin "1") (pinfunction "VBAT_1") (pintype "power_in"))
    )
    (net (code "63") (name "MCU_VDD") (class "Default")
      (node (ref "C0401") (pin "1") (pinfunction "1_1") (pintype "passive"))
      (node (ref "C0402") (pin "1") (pinfunction "1_1") (pintype "passive"))
      (node (ref "C0403") (pin "1") (pinfunction "1_1") (pintype "passive"))
      (node (ref "C0410") (pin "1") (pinfunction "1_1") (pintype "passive"))
      (node (ref "L0411") (pin "1") (pinfunction "1_1") (pintype "passive"))
      (node (ref "SJ0401") (pin "2") (pinfunction "2_2") (pintype "passive"))
      (node (ref "U0101") (pin "19") (pinfunction "VDD_19") (pintype "power_in"))
      (node (ref "U0101") (pin "32") (pinfunction "VDD_32") (pintype "power_in"))
      (node (ref "U0101") (pin "64") (pinfunction "VDD_64") (pintype "power_in"))
    )
    (net (code "64") (name "MCU_VDDA") (class "Default")
      (node (ref "C0412") (pin "1") (pinfunction "1_1") (pintype "passive"))
      (node (ref "C0413") (pin "1") (pinfunction "1_1") (pintype "passive"))
      (node (ref "L0411") (pin "2") (pinfunction "2_2") (pintype "passive"))
      (node (ref "U0101") (pin "13") (pinfunction "VDDA_VREF_P_13") (pintype "power_in"))
    )
    (net (code "65") (name "MCU_VREF_M") (class "Default")
      (node (ref "R0441") (pin "2") (pinfunction "2_2") (pintype "passive"))
      (node (ref "U0101") (pin "12") (pinfunction "VSSA_VREF_M_12") (pintype "passive"))
    )
    (net (code "66") (name "MP_CAT_CTS_R") (class "Default")
      (node (ref "R1103") (pin "2") (pinfunction "2_2") (pintype "passive"))
      (node (ref "U1101") (pin "10") (pinfunction "T2IN_10") (pintype "input"))
    )
    (net (code "67") (name "MP_CAT_RTR_R") (class "Default")
      (node (ref "R1104") (pin "2") (pinfunction "2_2") (pintype "passive"))
      (node (ref "U1101") (pin "9") (pinfunction "R2OUT_9") (pintype "output"))
    )
    (net (code "68") (name "MP_CAT_RXD_R") (class "Default")
      (node (ref "R1101") (pin "2") (pinfunction "2_2") (pintype "passive"))
      (node (ref "U1101") (pin "11") (pinfunction "T1IN_11") (pintype "input"))
    )
    (net (code "69") (name "MP_CAT_TXD_R") (class "Default")
      (node (ref "R1102") (pin "2") (pinfunction "2_2") (pintype "passive"))
      (node (ref "U1101") (pin "12") (pinfunction "R1OUT_12") (pintype "output"))
    )
    (net (code "70") (name "MP_RS_CTS_R") (class "Default")
      (node (ref "R1003") (pin "2") (pinfunction "2_2") (pintype "passive"))
      (node (ref "U1001") (pin "10") (pinfunction "T2IN_10") (pintype "input"))
    )
    (net (code "71") (name "MP_RS_RTR_R") (class "Default")
      (node (ref "R1004") (pin "2") (pinfunction "2_2") (pintype "passive"))
      (node (ref "U1001") (pin "9") (pinfunction "R2OUT_9") (pintype "output"))
    )
    (net (code "72") (name "MP_RS_RXD_R") (class "Default")
      (node (ref "R1001") (pin "2") (pinfunction "2_2") (pintype "passive"))
      (node (ref "U1001") (pin "11") (pinfunction "T1IN_11") (pintype "input"))
    )
    (net (code "73") (name "MP_RS_TXD_R") (class "Default")
      (node (ref "R1002") (pin "2") (pinfunction "2_2") (pintype "passive"))
      (node (ref "U1001") (pin "12") (pinfunction "R1OUT_12") (pintype "output"))
    )
    (net (code "74") (name "Net-(C1211-Pad1)") (class "Default")
      (node (ref "C1211") (pin "1") (pinfunction "1_1") (pintype "passive"))
      (node (ref "L1211") (pin "2") (pinfunction "2_2") (pintype "passive"))
      (node (ref "U1201") (pin "1") (pinfunction "SW_1") (pintype "passive"))
      (node (ref "U1201") (pin "2") (pinfunction "SW_2") (pintype "passive"))
    )
    (net (code "75") (name "Net-(C1403-Pad2)") (class "Default")
      (node (ref "C1403") (pin "2") (pinfunction "2_2") (pintype "passive"))
      (node (ref "R1402") (pin "2") (pinfunction "2_2") (pintype "passive"))
      (node (ref "X1401") (pin "JSHIELD") (pinfunction "SHIELD_JSHIELD") (pintype "passive"))
      (node (ref "X1401") (pin "JSHIELD@2") (pinfunction "SHIELD_JSHIELD@2") (pintype "passive"))
      (node (ref "X1401") (pin "JSHIELD@3") (pinfunction "SHIELD_JSHIELD@3") (pintype "passive"))
      (node (ref "X1401") (pin "JSHIELD@4") (pinfunction "SHIELD_JSHIELD@4") (pintype "passive"))
      (node (ref "X1401") (pin "JSHIELD@5") (pinfunction "SHIELD_JSHIELD@5") (pintype "passive"))
      (node (ref "X1401") (pin "JSHIELD@6") (pinfunction "SHIELD_JSHIELD@6") (pintype "passive"))
    )
    (net (code "76") (name "Net-(U0601-SO)") (class "Default")
      (node (ref "R0611") (pin "2") (pinfunction "2_2") (pintype "passive"))
      (node (ref "U0601") (pin "22") (pinfunction "SO_22") (pintype "output"))
    )
    (net (code "77") (name "Net-(U0701-SO)") (class "Default")
      (node (ref "R0711") (pin "2") (pinfunction "2_2") (pintype "passive"))
      (node (ref "U0701") (pin "22") (pinfunction "SO_22") (pintype "output"))
    )
    (net (code "78") (name "Net-(U0801-SO)") (class "Default")
      (node (ref "R0811") (pin "2") (pinfunction "2_2") (pintype "passive"))
      (node (ref "U0801") (pin "22") (pinfunction "SO_22") (pintype "output"))
    )
    (net (code "79") (name "Net-(U0951-OUT)") (class "Default")
      (node (ref "D0951") (pin "C") (pinfunction "C_C") (pintype "passive"))
      (node (ref "R0952") (pin "1") (pinfunction "1_1") (pintype "passive"))
      (node (ref "U0951") (pin "1") (pinfunction "OUT_1") (pintype "output"))
    )
    (net (code "80") (name "Net-(U1001A-C1-)") (class "Default")
      (node (ref "C1002") (pin "2") (pinfunction "2_2") (pintype "passive"))
      (node (ref "U1001") (pin "3") (pinfunction "C1-_3") (pintype "bidirectional"))
    )
    (net (code "81") (name "Net-(U1001A-C2-)") (class "Default")
      (node (ref "C1003") (pin "2") (pinfunction "2_2") (pintype "passive"))
      (node (ref "U1001") (pin "5") (pinfunction "C2-_5") (pintype "bidirectional"))
    )
    (net (code "82") (name "Net-(U1101A-C1-)") (class "Default")
      (node (ref "C1102") (pin "2") (pinfunction "2_2") (pintype "passive"))
      (node (ref "U1101") (pin "3") (pinfunction "C1-_3") (pintype "bidirectional"))
    )
    (net (code "83") (name "Net-(U1101A-C2-)") (class "Default")
      (node (ref "C1103") (pin "2") (pinfunction "2_2") (pintype "passive"))
      (node (ref "U1101") (pin "5") (pinfunction "C2-_5") (pintype "bidirectional"))
    )
    (net (code "84") (name "Net-(U1201-BIAS)") (class "Default")
      (node (ref "C1212") (pin "1") (pinfunction "1_1") (pintype "passive"))
      (node (ref "R1211") (pin "1") (pinfunction "1_1") (pintype "passive"))
      (node (ref "U1201") (pin "5") (pinfunction "BIAS_5") (pintype "power_in"))
    )
    (net (code "85") (name "Net-(U1201-CBOOT)") (class "Default")
      (node (ref "C1211") (pin "2") (pinfunction "2_2") (pintype "passive"))
      (node (ref "U1201") (pin "3") (pinfunction "CBOOT_3") (pintype "passive"))
    )
    (net (code "86") (name "Net-(U1201-VCC)") (class "Default")
      (node (ref "C1205") (pin "2") (pinfunction "2_2") (pintype "passive"))
      (node (ref "U1201") (pin "4") (pinfunction "VCC_4") (pintype "passive"))
    )
    (net (code "87") (name "Net-(U1301-LBI)") (class "Default")
      (node (ref "R1301") (pin "2") (pinfunction "2_2") (pintype "passive"))
      (node (ref "R1302") (pin "1") (pinfunction "1_1") (pintype "passive"))
      (node (ref "U1301") (pin "6") (pinfunction "LBI_6") (pintype "input"))
    )
    (net (code "88") (name "Net-(U1301-SW)") (class "Default")
      (node (ref "L1311") (pin "2") (pinfunction "2_2") (pintype "passive"))
      (node (ref "L1311") (pin "4") (pinfunction "2_4") (pintype "passive"))
      (node (ref "U1301") (pin "9") (pinfunction "SW_9") (pintype "passive"))
    )
    (net (code "89") (name "PA0") (class "Default")
      (node (ref "R1101") (pin "1") (pinfunction "1_1") (pintype "passive"))
      (node (ref "U0101") (pin "14") (pinfunction "PA0_WKUP_14") (pintype "bidirectional"))
    )
    (net (code "90") (name "PA1") (class "Default")
      (node (ref "R1102") (pin "1") (pinfunction "1_1") (pintype "passive"))
      (node (ref "U0101") (pin "15") (pinfunction "PA1_15") (pintype "bidirectional"))
    )
    (net (code "91") (name "PA3") (class "Default")
      (node (ref "R0922") (pin "1") (pinfunction "1_1") (pintype "passive"))
      (node (ref "U0101") (pin "17") (pinfunction "PA3_17") (pintype "bidirectional"))
    )
    (net (code "92") (name "PA5") (class "Default")
      (node (ref "R0621") (pin "1") (pinfunction "1_1") (pintype "passive"))
      (node (ref "U0101") (pin "21") (pinfunction "PA5_21") (pintype "bidirectional"))
    )
    (net (code "93") (name "PA6") (class "Default")
      (node (ref "R0622") (pin "1") (pinfunction "1_1") (pintype "passive"))
      (node (ref "U0101") (pin "22") (pinfunction "PA6_22") (pintype "bidirectional"))
    )
    (net (code "94") (name "PA7") (class "Default")
      (node (ref "R0623") (pin "1") (pinfunction "1_1") (pintype "passive"))
      (node (ref "U0101") (pin "23") (pinfunction "PA7_23") (pintype "bidirectional"))
    )
    (net (code "95") (name "PA9") (class "Default")
      (node (ref "PF1411") (pin "1") (pinfunction "1_1") (pintype "passive"))
      (node (ref "U0101") (pin "42") (pinfunction "PA9_42") (pintype "bidirectional"))
      (node (ref "X1401") (pin "VBUS") (pinfunction "J_VUSB_VBUS") (pintype "power_in"))
    )
    (net (code "96") (name "PA10") (class "Default")
      (node (ref "U0101") (pin "43") (pinfunction "PA10_43") (pintype "bidirectional"))
      (node (ref "X1401") (pin "ID") (pinfunction "J_ID_ID") (pintype "bidirectional"))
    )
    (net (code "97") (name "PA11") (class "Default")
      (node (ref "U0101") (pin "44") (pinfunction "PA11_44") (pintype "bidirectional"))
      (node (ref "X1401") (pin "D-") (pinfunction "J_D-_D-") (pintype "bidirectional"))
    )
    (net (code "98") (name "PA12") (class "Default")
      (node (ref "U0101") (pin "45") (pinfunction "PA12_45") (pintype "bidirectional"))
      (node (ref "X1401") (pin "D+") (pinfunction "J_D+_D+") (pintype "bidirectional"))
    )
    (net (code "99") (name "PA13") (class "Default")
      (node (ref "R0231") (pin "1") (pinfunction "1_1") (pintype "passive"))
      (node (ref "U0101") (pin "46") (pinfunction "PA13_JTMS_SWDIO_46") (pintype "bidirectional"))
      (node (ref "X0201") (pin "2") (pinfunction "2_2") (pintype "passive"))
    )
    (net (code "100") (name "PA14") (class "Default")
      (node (ref "R0232") (pin "2") (pinfunction "2_2") (pintype "passive"))
      (node (ref "U0101") (pin "49") (pinfunction "PA14_JTCK_SWCLK_49") (pintype "bidirectional"))
      (node (ref "X0201") (pin "4") (pinfunction "4_4") (pintype "passive"))
    )
    (net (code "101") (name "PA15") (class "Default")
      (node (ref "R1103") (pin "1") (pinfunction "1_1") (pintype "passive"))
      (node (ref "U0101") (pin "50") (pinfunction "PA15_JTDI_50") (pintype "bidirectional"))
    )
    (net (code "102") (name "PB0") (class "Default")
      (node (ref "R0624") (pin "1") (pinfunction "1_1") (pintype "passive"))
      (node (ref "U0101") (pin "26") (pinfunction "PB0_26") (pintype "bidirectional"))
    )
    (net (code "103") (name "PB1") (class "Default")
      (node (ref "R0724") (pin "1") (pinfunction "1_1") (pintype "passive"))
      (node (ref "U0101") (pin "27") (pinfunction "PB1_27") (pintype "bidirectional"))
    )
    (net (code "104") (name "PB2") (class "Default")
      (node (ref "R0824") (pin "1") (pinfunction "1_1") (pintype "passive"))
      (node (ref "U0101") (pin "28") (pinfunction "PB2_28") (pintype "bidirectional"))
    )
    (net (code "105") (name "PB6") (class "Default")
      (node (ref "R0512") (pin "1") (pinfunction "1_1") (pintype "passive"))
      (node (ref "U0101") (pin "58") (pinfunction "PB6_58") (pintype "bidirectional"))
      (node (ref "X0601") (pin "1") (pinfunction "1_1") (pintype "passive"))
    )
    (net (code "106") (name "PB7") (class "Default")
      (node (ref "R1104") (pin "1") (pinfunction "1_1") (pintype "passive"))
      (node (ref "U0101") (pin "59") (pinfunction "PB7_59") (pintype "bidirectional"))
    )
    (net (code "107") (name "PB9") (class "Default")
      (node (ref "R0511") (pin "1") (pinfunction "1_1") (pintype "passive"))
      (node (ref "U0101") (pin "62") (pinfunction "PB9_62") (pintype "bidirectional"))
      (node (ref "X0601") (pin "3") (pinfunction "3_3") (pintype "passive"))
    )
    (net (code "108") (name "PB10") (class "Default")
      (node (ref "R1002") (pin "1") (pinfunction "1_1") (pintype "passive"))
      (node (ref "U0101") (pin "29") (pinfunction "PB10_29") (pintype "bidirectional"))
    )
    (net (code "109") (name "PB11") (class "Default")
      (node (ref "R0626") (pin "1") (pinfunction "1_1") (pintype "passive"))
      (node (ref "U0101") (pin "30") (pinfunction "PB11_30") (pintype "bidirectional"))
    )
    (net (code "110") (name "PB12") (class "Default")
      (node (ref "R1003") (pin "1") (pinfunction "1_1") (pintype "passive"))
      (node (ref "U0101") (pin "33") (pinfunction "PB12_33") (pintype "bidirectional"))
    )
    (net (code "111") (name "PB13") (class "Default")
      (node (ref "R1004") (pin "1") (pinfunction "1_1") (pintype "passive"))
      (node (ref "U0101") (pin "34") (pinfunction "PB13_34") (pintype "bidirectional"))
    )
    (net (code "112") (name "PC0") (class "Default")
      (node (ref "R0952") (pin "2") (pinfunction "2_2") (pintype "passive"))
      (node (ref "U0101") (pin "8") (pinfunction "PC0_8") (pintype "bidirectional"))
    )
    (net (code "113") (name "PC1") (class "Default")
      (node (ref "R1001") (pin "1") (pinfunction "1_1") (pintype "passive"))
      (node (ref "U0101") (pin "9") (pinfunction "PC1_9") (pintype "bidirectional"))
    )
    (net (code "114") (name "PC2") (class "Default")
      (node (ref "D0961") (pin "A") (pinfunction "A_A") (pintype "passive"))
      (node (ref "R0961") (pin "2") (pinfunction "2_2") (pintype "passive"))
      (node (ref "U0101") (pin "10") (pinfunction "PC2_10") (pintype "bidirectional"))
    )
    (net (code "115") (name "PC3") (class "Default")
      (node (ref "R0921") (pin "1") (pinfunction "1_1") (pintype "passive"))
      (node (ref "U0101") (pin "11") (pinfunction "PC3_11") (pintype "bidirectional"))
    )
    (net (code "116") (name "PC4") (class "Default")
      (node (ref "R0625") (pin "1") (pinfunction "1_1") (pintype "passive"))
      (node (ref "U0101") (pin "24") (pinfunction "PC4_24") (pintype "bidirectional"))
    )
    (net (code "117") (name "PC14_OSC32_IN") (class "Default")
      (node (ref "C0331") (pin "-") (pinfunction "E_-") (pintype "passive"))
      (node (ref "C0332") (pin "1") (pinfunction "1_1") (pintype "passive"))
      (node (ref "Q0321") (pin "2") (pinfunction "2_2") (pintype "passive"))
      (node (ref "U0101") (pin "3") (pinfunction "PC14_OSC32_IN_3") (pintype "bidirectional"))
    )
    (net (code "118") (name "PC15_OSC32_OUT") (class "Default")
      (node (ref "C0311") (pin "1") (pinfunction "1_1") (pintype "passive"))
      (node (ref "Q0321") (pin "1") (pinfunction "1_1") (pintype "passive"))
      (node (ref "U0101") (pin "4") (pinfunction "PC15_OSC32_OUT_4") (pintype "bidirectional"))
    )
    (net (code "119") (name "PH0") (class "Default")
      (node (ref "U0101") (pin "5") (pinfunction "PH0_OSC_IN_5") (pintype "bidirectional"))
    )
    (net (code "120") (name "PH1") (class "Default")
      (node (ref "U0101") (pin "6") (pinfunction "PH1_OSC_OUT_6") (pintype "bidirectional"))
    )
    (net (code "121") (name "PH3_BOOT0") (class "Default")
      (node (ref "R0221") (pin "2") (pinfunction "2_2") (pintype "passive"))
      (node (ref "U0101") (pin "60") (pinfunction "BOOT0_60") (pintype "output"))
      (node (ref "X0222") (pin "2") (pinfunction "2_2") (pintype "passive"))
    )
    (net (code "122") (name "RELAY1") (class "Default")
      (node (ref "U0601") (pin "1") (pinfunction "OUT0_1") (pintype "passive"))
      (node (ref "X1601") (pin "1") (pinfunction "1_1") (pintype "passive"))
    )
    (net (code "123") (name "RELAY2") (class "Default")
      (node (ref "U0601") (pin "2") (pinfunction "OUT1_2") (pintype "passive"))
      (node (ref "X1601") (pin "2") (pinfunction "2_2") (pintype "passive"))
    )
    (net (code "124") (name "RELAY3") (class "Default")
      (node (ref "U0601") (pin "4") (pinfunction "OUT2_4") (pintype "passive"))
      (node (ref "X1601") (pin "3") (pinfunction "3_3") (pintype "passive"))
    )
    (net (code "125") (name "RELAY4") (class "Default")
      (node (ref "U0601") (pin "5") (pinfunction "OUT3_5") (pintype "passive"))
      (node (ref "X1601") (pin "4") (pinfunction "4_4") (pintype "passive"))
    )
    (net (code "126") (name "RELAY5") (class "Default")
      (node (ref "U0601") (pin "12") (pinfunction "OUT4_12") (pintype "passive"))
      (node (ref "X1601") (pin "5") (pinfunction "5_5") (pintype "passive"))
    )
    (net (code "127") (name "RELAY6") (class "Default")
      (node (ref "U0601") (pin "13") (pinfunction "OUT5_13") (pintype "passive"))
      (node (ref "X1601") (pin "6") (pinfunction "6_6") (pintype "passive"))
    )
    (net (code "128") (name "RELAY7") (class "Default")
      (node (ref "U0601") (pin "15") (pinfunction "OUT6_15") (pintype "passive"))
      (node (ref "X1601") (pin "7") (pinfunction "7_7") (pintype "passive"))
    )
    (net (code "129") (name "RELAY8") (class "Default")
      (node (ref "U0601") (pin "16") (pinfunction "OUT7_16") (pintype "passive"))
      (node (ref "X1601") (pin "8") (pinfunction "8_8") (pintype "passive"))
    )
    (net (code "130") (name "RELAY9") (class "Default")
      (node (ref "U0601") (pin "17") (pinfunction "OUT8_17") (pintype "passive"))
      (node (ref "X1601") (pin "9") (pinfunction "9_9") (pintype "passive"))
    )
    (net (code "131") (name "RELAY10") (class "Default")
      (node (ref "U0601") (pin "18") (pinfunction "OUT9_18") (pintype "passive"))
      (node (ref "X1601") (pin "10") (pinfunction "10_10") (pintype "passive"))
    )
    (net (code "132") (name "RELAY11") (class "Default")
      (node (ref "U0601") (pin "20") (pinfunction "OUT10_20") (pintype "passive"))
      (node (ref "X1601") (pin "11") (pinfunction "11_11") (pintype "passive"))
    )
    (net (code "133") (name "RELAY12") (class "Default")
      (node (ref "U0601") (pin "21") (pinfunction "OUT11_21") (pintype "passive"))
      (node (ref "X1601") (pin "12") (pinfunction "12_12") (pintype "passive"))
    )
    (net (code "134") (name "RELAY13") (class "Default")
      (node (ref "U0601") (pin "28") (pinfunction "OUT12_28") (pintype "passive"))
      (node (ref "X1601") (pin "13") (pinfunction "13_13") (pintype "passive"))
    )
    (net (code "135") (name "RELAY14") (class "Default")
      (node (ref "U0601") (pin "29") (pinfunction "OUT13_29") (pintype "passive"))
      (node (ref "X1601") (pin "14") (pinfunction "14_14") (pintype "passive"))
    )
    (net (code "136") (name "RELAY15") (class "Default")
      (node (ref "U0601") (pin "31") (pinfunction "OUT14_31") (pintype "passive"))
      (node (ref "X1601") (pin "15") (pinfunction "15_15") (pintype "passive"))
    )
    (net (code "137") (name "RELAY16") (class "Default")
      (node (ref "U0601") (pin "32") (pinfunction "OUT15_32") (pintype "passive"))
      (node (ref "X1601") (pin "16") (pinfunction "16_16") (pintype "passive"))
    )
    (net (code "138") (name "RELAY17") (class "Default")
      (node (ref "U0701") (pin "1") (pinfunction "OUT0_1") (pintype "passive"))
      (node (ref "X1601") (pin "17") (pinfunction "17_17") (pintype "passive"))
    )
    (net (code "139") (name "RELAY18") (class "Default")
      (node (ref "U0701") (pin "2") (pinfunction "OUT1_2") (pintype "passive"))
      (node (ref "X1601") (pin "18") (pinfunction "18_18") (pintype "passive"))
    )
    (net (code "140") (name "RELAY19") (class "Default")
      (node (ref "U0701") (pin "4") (pinfunction "OUT2_4") (pintype "passive"))
      (node (ref "X1601") (pin "19") (pinfunction "19_19") (pintype "passive"))
    )
    (net (code "141") (name "RELAY20") (class "Default")
      (node (ref "U0701") (pin "5") (pinfunction "OUT3_5") (pintype "passive"))
      (node (ref "X1601") (pin "20") (pinfunction "20_20") (pintype "passive"))
    )
    (net (code "142") (name "RELAY21") (class "Default")
      (node (ref "U0701") (pin "12") (pinfunction "OUT4_12") (pintype "passive"))
      (node (ref "X1602") (pin "1") (pinfunction "1_1") (pintype "passive"))
    )
    (net (code "143") (name "RELAY22") (class "Default")
      (node (ref "U0701") (pin "13") (pinfunction "OUT5_13") (pintype "passive"))
      (node (ref "X1602") (pin "2") (pinfunction "2_2") (pintype "passive"))
    )
    (net (code "144") (name "RELAY23") (class "Default")
      (node (ref "U0701") (pin "15") (pinfunction "OUT6_15") (pintype "passive"))
      (node (ref "X1602") (pin "3") (pinfunction "3_3") (pintype "passive"))
    )
    (net (code "145") (name "RELAY24") (class "Default")
      (node (ref "U0701") (pin "16") (pinfunction "OUT7_16") (pintype "passive"))
      (node (ref "X1602") (pin "4") (pinfunction "4_4") (pintype "passive"))
    )
    (net (code "146") (name "RELAY25") (class "Default")
      (node (ref "U0701") (pin "17") (pinfunction "OUT8_17") (pintype "passive"))
      (node (ref "X1602") (pin "5") (pinfunction "5_5") (pintype "passive"))
    )
    (net (code "147") (name "RELAY26") (class "Default")
      (node (ref "U0701") (pin "18") (pinfunction "OUT9_18") (pintype "passive"))
      (node (ref "X1602") (pin "6") (pinfunction "6_6") (pintype "passive"))
    )
    (net (code "148") (name "RELAY27") (class "Default")
      (node (ref "U0701") (pin "20") (pinfunction "OUT10_20") (pintype "passive"))
      (node (ref "X1602") (pin "7") (pinfunction "7_7") (pintype "passive"))
    )
    (net (code "149") (name "RELAY28") (class "Default")
      (node (ref "U0701") (pin "21") (pinfunction "OUT11_21") (pintype "passive"))
      (node (ref "X1602") (pin "8") (pinfunction "8_8") (pintype "passive"))
    )
    (net (code "150") (name "RELAY29") (class "Default")
      (node (ref "U0701") (pin "28") (pinfunction "OUT12_28") (pintype "passive"))
      (node (ref "X1602") (pin "9") (pinfunction "9_9") (pintype "passive"))
    )
    (net (code "151") (name "RELAY30") (class "Default")
      (node (ref "U0701") (pin "29") (pinfunction "OUT13_29") (pintype "passive"))
      (node (ref "X1602") (pin "10") (pinfunction "10_10") (pintype "passive"))
    )
    (net (code "152") (name "RELAY31") (class "Default")
      (node (ref "U0701") (pin "31") (pinfunction "OUT14_31") (pintype "passive"))
      (node (ref "X1602") (pin "11") (pinfunction "11_11") (pintype "passive"))
    )
    (net (code "153") (name "RELAY32") (class "Default")
      (node (ref "U0701") (pin "32") (pinfunction "OUT15_32") (pintype "passive"))
      (node (ref "X1602") (pin "12") (pinfunction "12_12") (pintype "passive"))
    )
    (net (code "154") (name "RELAY33") (class "Default")
      (node (ref "U0801") (pin "1") (pinfunction "OUT0_1") (pintype "passive"))
      (node (ref "X1602") (pin "13") (pinfunction "13_13") (pintype "passive"))
    )
    (net (code "155") (name "RELAY34") (class "Default")
      (node (ref "U0801") (pin "2") (pinfunction "OUT1_2") (pintype "passive"))
      (node (ref "X1602") (pin "14") (pinfunction "14_14") (pintype "passive"))
    )
    (net (code "156") (name "RELAY35") (class "Default")
      (node (ref "U0801") (pin "4") (pinfunction "OUT2_4") (pintype "passive"))
      (node (ref "X1602") (pin "15") (pinfunction "15_15") (pintype "passive"))
    )
    (net (code "157") (name "RELAY36") (class "Default")
      (node (ref "U0801") (pin "5") (pinfunction "OUT3_5") (pintype "passive"))
      (node (ref "X1602") (pin "16") (pinfunction "16_16") (pintype "passive"))
    )
    (net (code "158") (name "RM_FWD") (class "Default")
      (node (ref "L0901") (pin "2") (pinfunction "2_2") (pintype "passive"))
      (node (ref "X1501") (pin "1") (pinfunction "1_1") (pintype "passive"))
    )
    (net (code "159") (name "RM_REV") (class "Default")
      (node (ref "L0911") (pin "2") (pinfunction "2_2") (pintype "passive"))
      (node (ref "X1511") (pin "1") (pinfunction "1_1") (pintype "passive"))
    )
    (net (code "160") (name "RS_DTE_CTS") (class "Default")
      (node (ref "C1053") (pin "1") (pinfunction "1_1") (pintype "passive"))
      (node (ref "U1001") (pin "7") (pinfunction "T2OUT_7") (pintype "output"))
      (node (ref "X1053") (pin "1") (pinfunction "1_1") (pintype "passive"))
    )
    (net (code "161") (name "RS_DTE_RTR") (class "Default")
      (node (ref "C0054") (pin "1") (pinfunction "1_1") (pintype "passive"))
      (node (ref "U1001") (pin "8") (pinfunction "R2IN_8") (pintype "input"))
      (node (ref "X1053") (pin "2") (pinfunction "2_2") (pintype "passive"))
    )
    (net (code "162") (name "RS_DTE_RXD") (class "Default")
      (node (ref "C1051") (pin "1") (pinfunction "1_1") (pintype "passive"))
      (node (ref "U1001") (pin "14") (pinfunction "T1OUT_14") (pintype "output"))
      (node (ref "X1051") (pin "1") (pinfunction "1_1") (pintype "passive"))
    )
    (net (code "163") (name "RS_DTE_TXD") (class "Default")
      (node (ref "C1052") (pin "1") (pinfunction "1_1") (pintype "passive"))
      (node (ref "U1001") (pin "13") (pinfunction "R1IN_13") (pintype "input"))
      (node (ref "X1051") (pin "2") (pinfunction "2_2") (pintype "passive"))
    )
    (net (code "164") (name "RS_MX_C1P") (class "Default")
      (node (ref "C1002") (pin "1") (pinfunction "1_1") (pintype "passive"))
      (node (ref "U1001") (pin "1") (pinfunction "C1+_1") (pintype "bidirectional"))
    )
    (net (code "165") (name "RS_MX_C2P") (class "Default")
      (node (ref "C1003") (pin "1") (pinfunction "1_1") (pintype "passive"))
      (node (ref "U1001") (pin "4") (pinfunction "C2+_4") (pintype "bidirectional"))
    )
    (net (code "166") (name "RS_MX_VM") (class "Default")
      (node (ref "C1005") (pin "1") (pinfunction "1_1") (pintype "passive"))
      (node (ref "U1001") (pin "6") (pinfunction "V-_6") (pintype "bidirectional"))
    )
    (net (code "167") (name "RS_MX_VP") (class "Default")
      (node (ref "C1004") (pin "1") (pinfunction "1_1") (pintype "passive"))
      (node (ref "U1001") (pin "2") (pinfunction "V+_2") (pintype "bidirectional"))
    )
    (net (code "168") (name "SPI_DRV_C_~{CS}") (class "Default")
      (node (ref "R0724") (pin "2") (pinfunction "2_2") (pintype "passive"))
      (node (ref "U0701") (pin "14") (pinfunction "~{CS}_14") (pintype "input"))
    )
    (net (code "169") (name "SPI_DRV_EXT_~{CS}") (class "Default")
      (node (ref "R0824") (pin "2") (pinfunction "2_2") (pintype "passive"))
      (node (ref "U0801") (pin "14") (pinfunction "~{CS}_14") (pintype "input"))
    )
    (net (code "170") (name "SPI_DRV_L_~{CS}") (class "Default")
      (node (ref "R0624") (pin "2") (pinfunction "2_2") (pintype "passive"))
      (node (ref "U0601") (pin "14") (pinfunction "~{CS}_14") (pintype "input"))
    )
    (net (code "171") (name "SPI_DRV_PWM") (class "Default")
      (node (ref "R0626") (pin "2") (pinfunction "2_2") (pintype "passive"))
      (node (ref "U0601") (pin "30") (pinfunction "PWM_30") (pintype "input"))
      (node (ref "U0701") (pin "30") (pinfunction "PWM_30") (pintype "input"))
      (node (ref "U0801") (pin "30") (pinfunction "PWM_30") (pintype "input"))
    )
    (net (code "172") (name "SPI_DRV_SCLK") (class "Default")
      (node (ref "R0621") (pin "2") (pinfunction "2_2") (pintype "passive"))
      (node (ref "U0601") (pin "11") (pinfunction "SCLK_11") (pintype "input"))
      (node (ref "U0701") (pin "11") (pinfunction "SCLK_11") (pintype "input"))
      (node (ref "U0801") (pin "11") (pinfunction "SCLK_11") (pintype "input"))
    )
    (net (code "173") (name "SPI_DRV_SI") (class "Default")
      (node (ref "R0623") (pin "2") (pinfunction "2_2") (pintype "passive"))
      (node (ref "U0601") (pin "19") (pinfunction "SI_19") (pintype "input"))
      (node (ref "U0701") (pin "19") (pinfunction "SI_19") (pintype "input"))
      (node (ref "U0801") (pin "19") (pinfunction "SI_19") (pintype "input"))
    )
    (net (code "174") (name "SPI_DRV_SO") (class "Default")
      (node (ref "R0611") (pin "1") (pinfunction "1_1") (pintype "passive"))
      (node (ref "R0622") (pin "2") (pinfunction "2_2") (pintype "passive"))
      (node (ref "R0711") (pin "1") (pinfunction "1_1") (pintype "passive"))
      (node (ref "R0811") (pin "1") (pinfunction "1_1") (pintype "passive"))
    )
    (net (code "175") (name "SPI_DRV_~{RST}") (class "Default")
      (node (ref "R0625") (pin "2") (pinfunction "2_2") (pintype "passive"))
      (node (ref "U0601") (pin "27") (pinfunction "~{RST}_27") (pintype "input"))
      (node (ref "U0701") (pin "27") (pinfunction "~{RST}_27") (pintype "input"))
      (node (ref "U0801") (pin "27") (pinfunction "~{RST}_27") (pintype "input"))
    )
    (net (code "176") (name "SWR_IN_FWD") (class "Default")
      (node (ref "D0901") (pin "A") (pinfunction "A_A") (pintype "passive"))
      (node (ref "R0902") (pin "2") (pinfunction "2_2") (pintype "passive"))
      (node (ref "R0903") (pin "1") (pinfunction "1_1") (pintype "passive"))
      (node (ref "U0921") (pin "1") (pinfunction "1_1") (pintype "passive"))
    )
    (net (code "177") (name "SWR_IN_FWD_HI") (class "Default")
      (node (ref "C0901") (pin "1") (pinfunction "1_1") (pintype "passive"))
      (node (ref "L0901") (pin "1") (pinfunction "1_1") (pintype "passive"))
      (node (ref "R0901") (pin "2") (pinfunction "2_2") (pintype "passive"))
      (node (ref "R0902") (pin "1") (pinfunction "1_1") (pintype "passive"))
    )
    (net (code "178") (name "SWR_IN_REV") (class "Default")
      (node (ref "D0911") (pin "A") (pinfunction "A_A") (pintype "passive"))
      (node (ref "R0912") (pin "2") (pinfunction "2_2") (pintype "passive"))
      (node (ref "R0913") (pin "1") (pinfunction "1_1") (pintype "passive"))
      (node (ref "U0921") (pin "5") (pinfunction "5_5") (pintype "passive"))
    )
    (net (code "179") (name "SWR_IN_REV_HI") (class "Default")
      (node (ref "C0911") (pin "1") (pinfunction "1_1") (pintype "passive"))
      (node (ref "L0911") (pin "1") (pinfunction "1_1") (pintype "passive"))
      (node (ref "R0911") (pin "2") (pinfunction "2_2") (pintype "passive"))
      (node (ref "R0912") (pin "1") (pinfunction "1_1") (pintype "passive"))
    )
    (net (code "180") (name "SWR_SEL_FWD") (class "Default")
      (node (ref "R0921") (pin "2") (pinfunction "2_2") (pintype "passive"))
      (node (ref "U0921") (pin "7") (pinfunction "7_7") (pintype "input"))
    )
    (net (code "181") (name "SWR_SEL_PWR") (class "Default")
      (node (ref "D0951") (pin "A") (pinfunction "A_A") (pintype "passive"))
      (node (ref "R0951") (pin "2") (pinfunction "2_2") (pintype "passive"))
      (node (ref "U0921") (pin "2") (pinfunction "2_2") (pintype "passive"))
      (node (ref "U0921") (pin "6") (pinfunction "6_6") (pintype "passive"))
      (node (ref "U0951") (pin "4") (pinfunction "-IN_4") (pintype "input"))
    )
    (net (code "182") (name "SWR_SEL_REV") (class "Default")
      (node (ref "R0922") (pin "2") (pinfunction "2_2") (pintype "passive"))
      (node (ref "U0921") (pin "3") (pinfunction "3_3") (pintype "input"))
    )
    (net (code "183") (name "TPS_LBO") (class "Default")
      (node (ref "R1322") (pin "1") (pinfunction "1_1") (pintype "passive"))
      (node (ref "U1301") (pin "2") (pinfunction "LBO_2") (pintype "output"))
    )
    (net (code "184") (name "TPS_PG") (class "Default")
      (node (ref "R1321") (pin "1") (pinfunction "1_1") (pintype "passive"))
      (node (ref "U1301") (pin "4") (pinfunction "PG_4") (pintype "output"))
    )
    (net (code "185") (name "VDDUSB") (class "Default")
      (node (ref "PF1411") (pin "2") (pinfunction "2_2") (pintype "passive"))
      (node (ref "U0101") (pin "48") (pinfunction "VDDUSB_48") (pintype "power_in"))
    )
    (net (code "186") (name "unconnected-(U0101-PA2_WKUP-Pad16)") (class "Default")
      (node (ref "U0101") (pin "16") (pinfunction "PA2_WKUP_16") (pintype "bidirectional"))
    )
    (net (code "187") (name "unconnected-(U0101-PA4-Pad20)") (class "Default")
      (node (ref "U0101") (pin "20") (pinfunction "PA4_20") (pintype "bidirectional"))
    )
    (net (code "188") (name "unconnected-(U0101-PA8-Pad41)") (class "Default")
      (node (ref "U0101") (pin "41") (pinfunction "PA8_41") (pintype "bidirectional"))
    )
    (net (code "189") (name "unconnected-(U0101-PB3_JTDO_TRACESWO-Pad55)") (class "Default")
      (node (ref "U0101") (pin "55") (pinfunction "PB3_JTDO_TRACESWO_55") (pintype "bidirectional"))
    )
    (net (code "190") (name "unconnected-(U0101-PB4_NJTRST-Pad56)") (class "Default")
      (node (ref "U0101") (pin "56") (pinfunction "PB4_NJTRST_56") (pintype "bidirectional"))
    )
    (net (code "191") (name "unconnected-(U0101-PB5-Pad57)") (class "Default")
      (node (ref "U0101") (pin "57") (pinfunction "PB5_57") (pintype "bidirectional"))
    )
    (net (code "192") (name "unconnected-(U0101-PB8-Pad61)") (class "Default")
      (node (ref "U0101") (pin "61") (pinfunction "PB8_61") (pintype "bidirectional"))
    )
    (net (code "193") (name "unconnected-(U0101-PB14-Pad35)") (class "Default")
      (node (ref "U0101") (pin "35") (pinfunction "PB14_35") (pintype "bidirectional"))
    )
    (net (code "194") (name "unconnected-(U0101-PB15-Pad36)") (class "Default")
      (node (ref "U0101") (pin "36") (pinfunction "PB15_36") (pintype "bidirectional"))
    )
    (net (code "195") (name "unconnected-(U0101-PC5_WKUP-Pad25)") (class "Default")
      (node (ref "U0101") (pin "25") (pinfunction "PC5_WKUP_25") (pintype "bidirectional"))
    )
    (net (code "196") (name "unconnected-(U0101-PC6-Pad37)") (class "Default")
      (node (ref "U0101") (pin "37") (pinfunction "PC6_37") (pintype "bidirectional"))
    )
    (net (code "197") (name "unconnected-(U0101-PC7-Pad38)") (class "Default")
      (node (ref "U0101") (pin "38") (pinfunction "PC7_38") (pintype "bidirectional"))
    )
    (net (code "198") (name "unconnected-(U0101-PC8-Pad39)") (class "Default")
      (node (ref "U0101") (pin "39") (pinfunction "PC8_39") (pintype "bidirectional"))
    )
    (net (code "199") (name "unconnected-(U0101-PC9-Pad40)") (class "Default")
      (node (ref "U0101") (pin "40") (pinfunction "PC9_40") (pintype "bidirectional"))
    )
    (net (code "200") (name "unconnected-(U0101-PC10-Pad51)") (class "Default")
      (node (ref "U0101") (pin "51") (pinfunction "PC10_51") (pintype "bidirectional"))
    )
    (net (code "201") (name "unconnected-(U0101-PC11-Pad52)") (class "Default")
      (node (ref "U0101") (pin "52") (pinfunction "PC11_52") (pintype "bidirectional"))
    )
    (net (code "202") (name "unconnected-(U0101-PC12-Pad53)") (class "Default")
      (node (ref "U0101") (pin "53") (pinfunction "PC12_53") (pintype "bidirectional"))
    )
    (net (code "203") (name "unconnected-(U0101-PC13_WKUP-Pad2)") (class "Default")
      (node (ref "U0101") (pin "2") (pinfunction "PC13_WKUP_2") (pintype "bidirectional"))
    )
    (net (code "204") (name "unconnected-(U0101-PD2-Pad54)") (class "Default")
      (node (ref "U0101") (pin "54") (pinfunction "PD2_54") (pintype "bidirectional"))
    )
    (net (code "205") (name "unconnected-(U1201-NC-Pad14)") (class "Default")
      (node (ref "U1201") (pin "14") (pinfunction "NC_14") (pintype "no_connect"))
    )
    (net (code "206") (name "unconnected-(U1201-~{RESET}-Pad8)") (class "Default")
      (node (ref "U1201") (pin "8") (pinfunction "~{RESET}_8") (pintype "output"))
    )
    (net (code "207") (name "unconnected-(X0201-Pad6)") (class "Default")
      (node (ref "X0201") (pin "6") (pinfunction "6_6") (pintype "passive"))
    )
    (net (code "208") (name "unconnected-(X0201-Pad7)") (class "Default")
      (node (ref "X0201") (pin "7") (pinfunction "7_7") (pintype "passive"))
    )
    (net (code "209") (name "unconnected-(X0201-Pad8)") (class "Default")
      (node (ref "X0201") (pin "8") (pinfunction "8_8") (pintype "passive"))
    )
  )
)
